# bitfury_h-card-v1_2.net
KiCad netlist of a schematic drawn in EAGLE
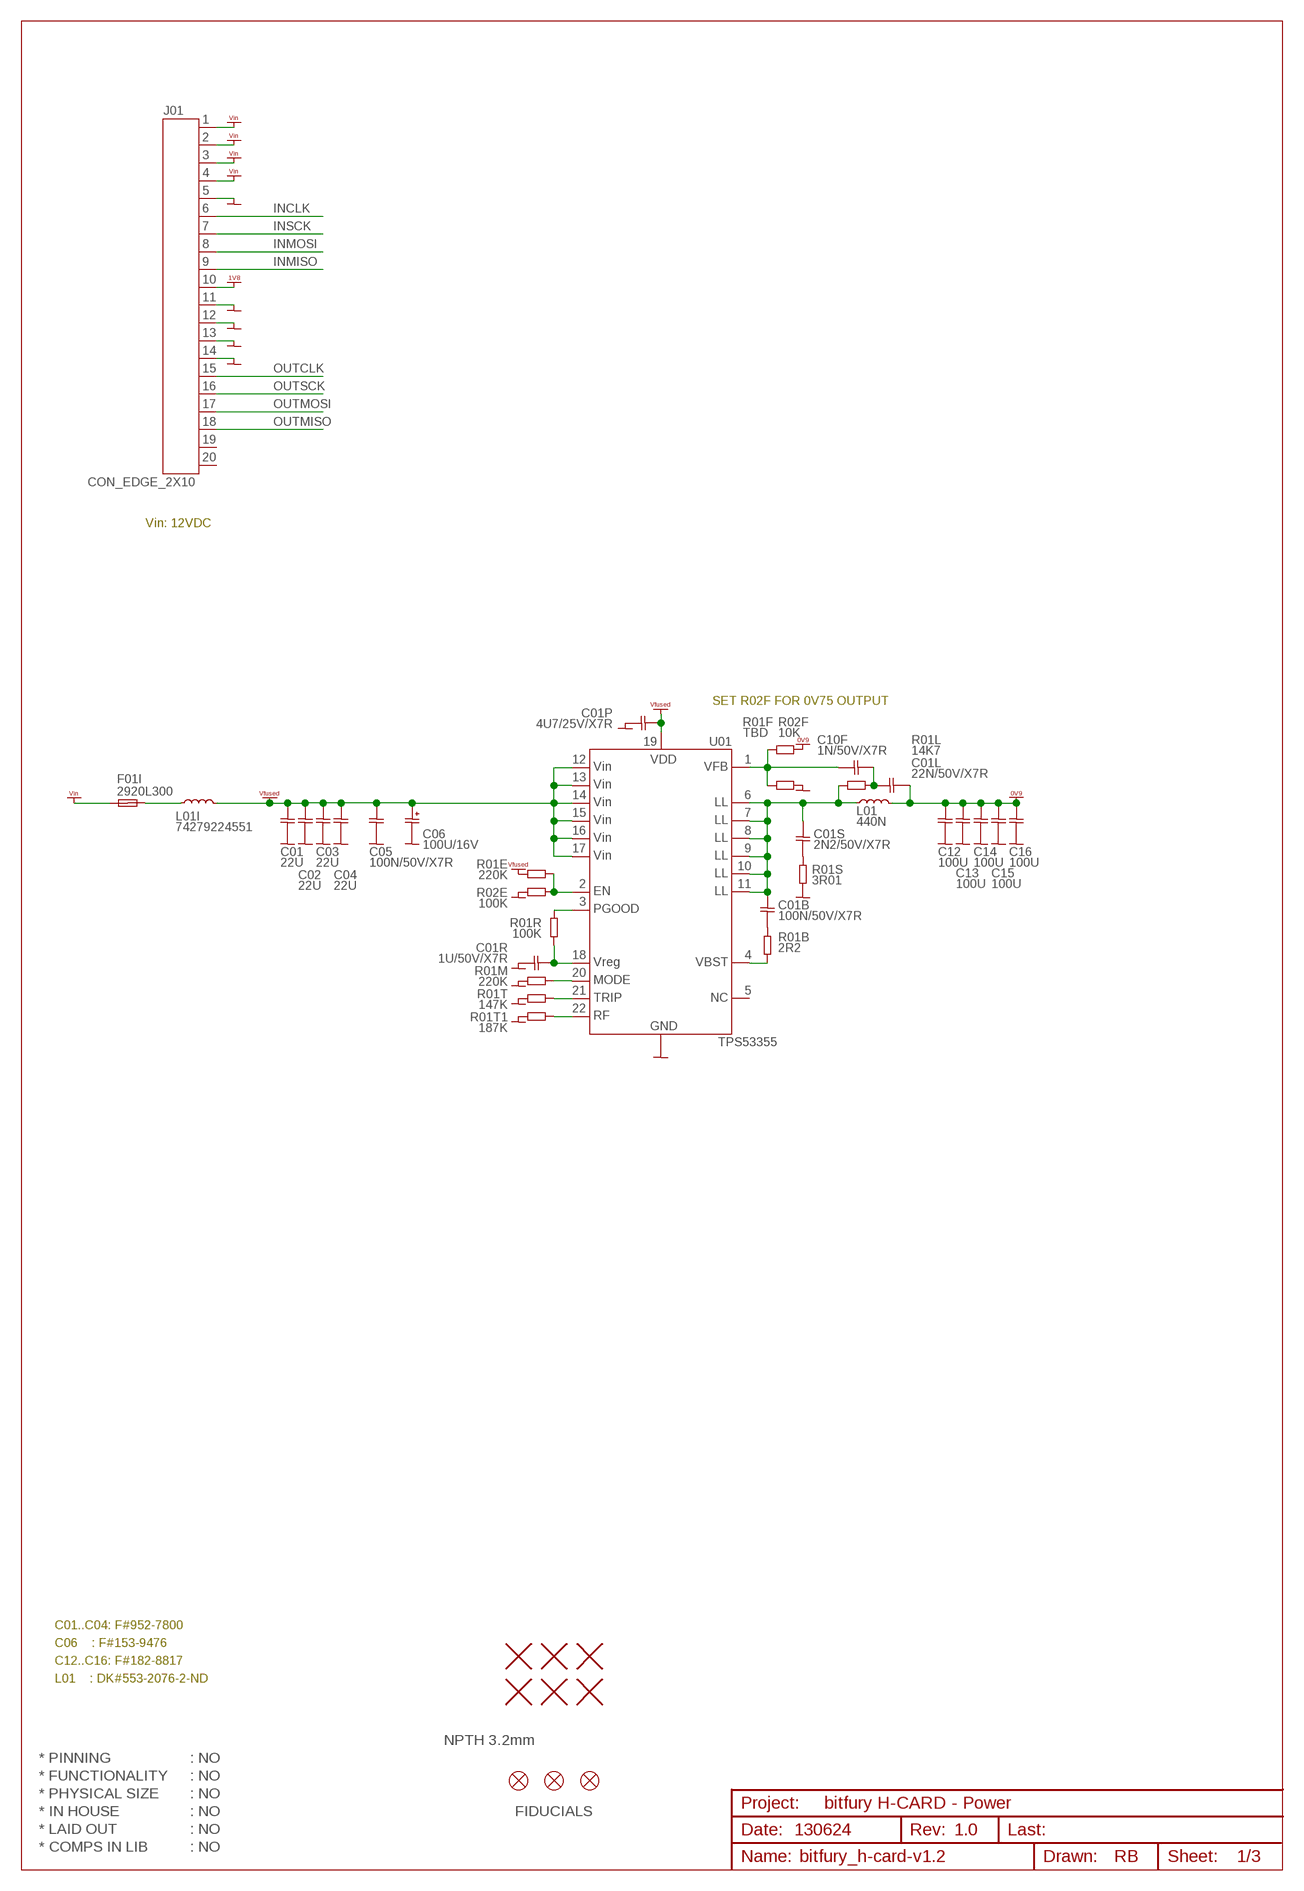
[diagram p0: schematic, sheet 1]
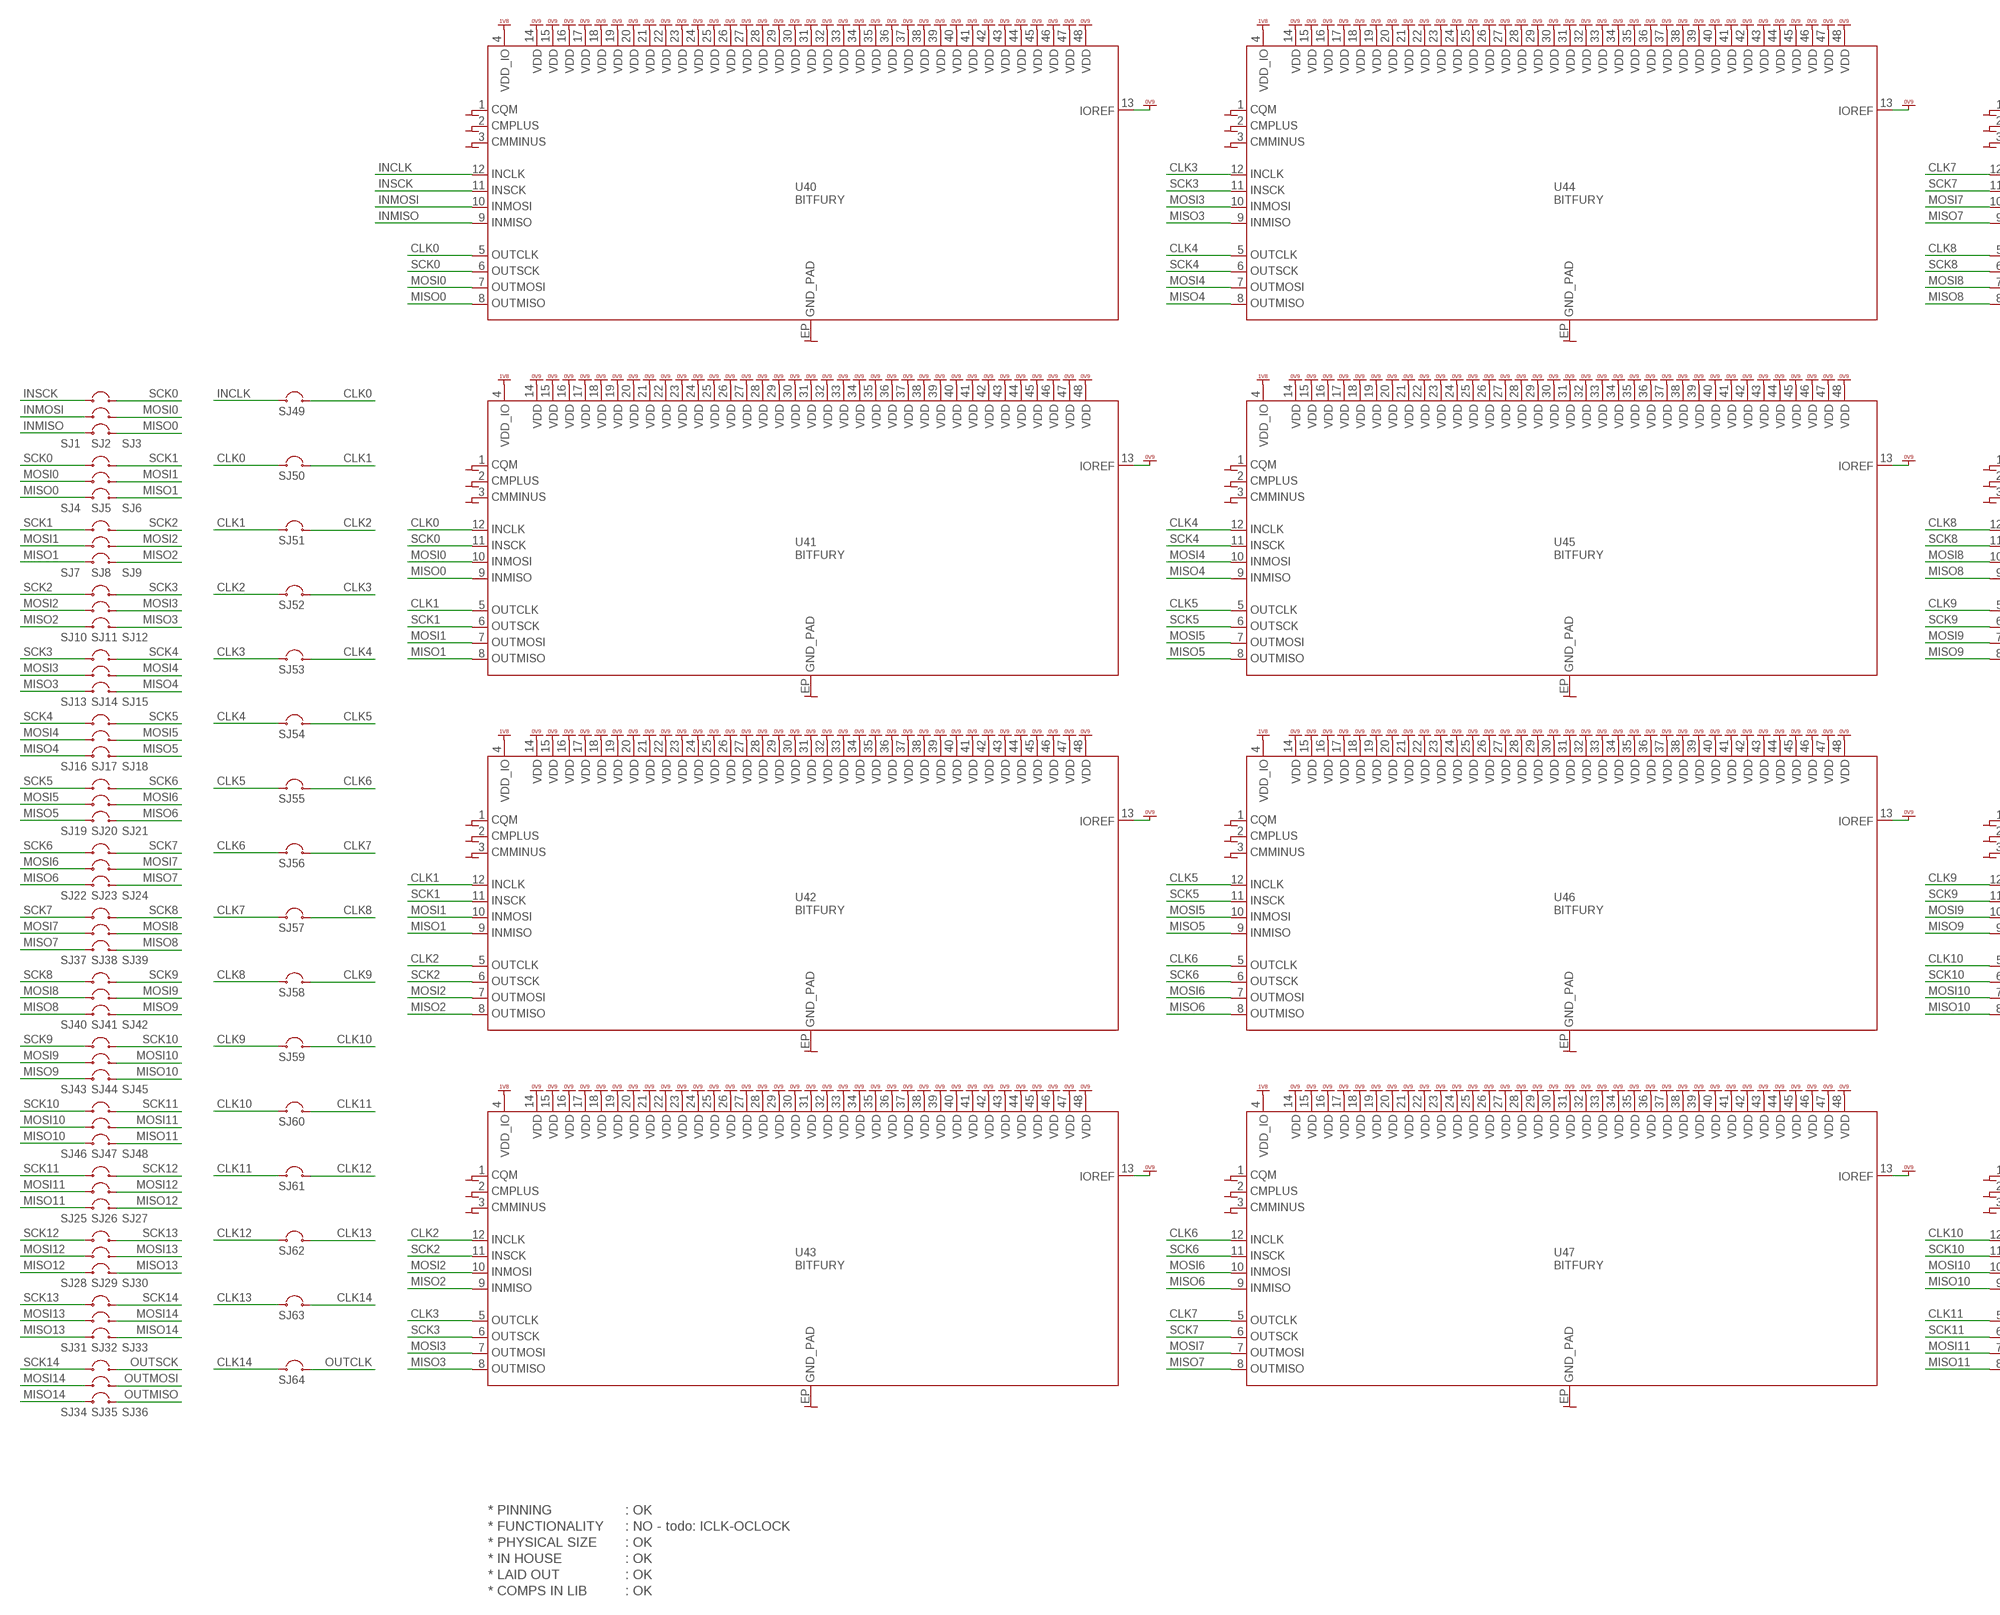
[diagram p1: schematic, sheet 2, part 1 of 2]
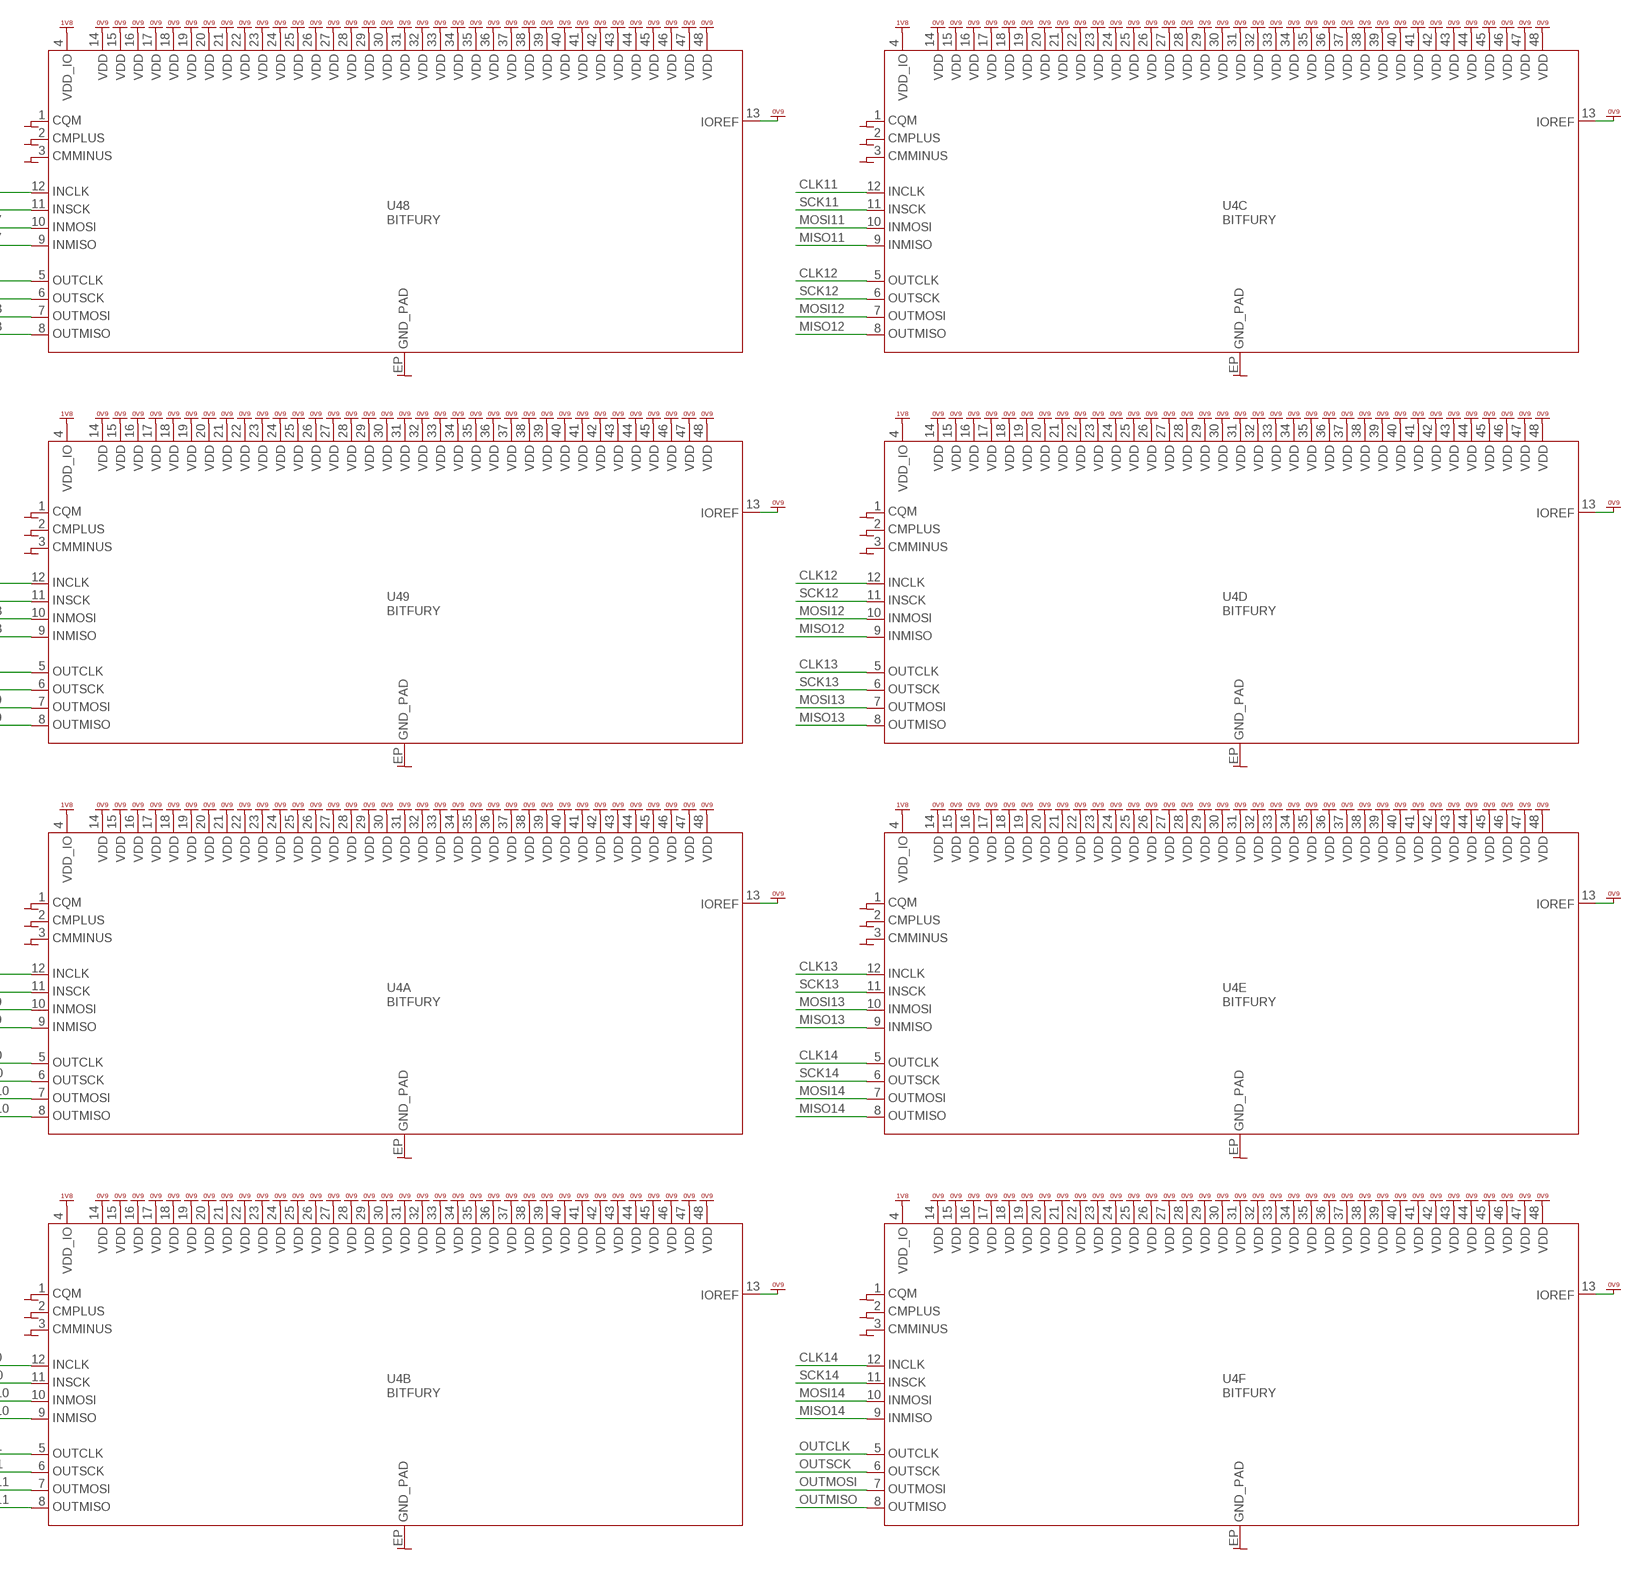
[diagram p2: schematic, sheet 2, part 2 of 2]
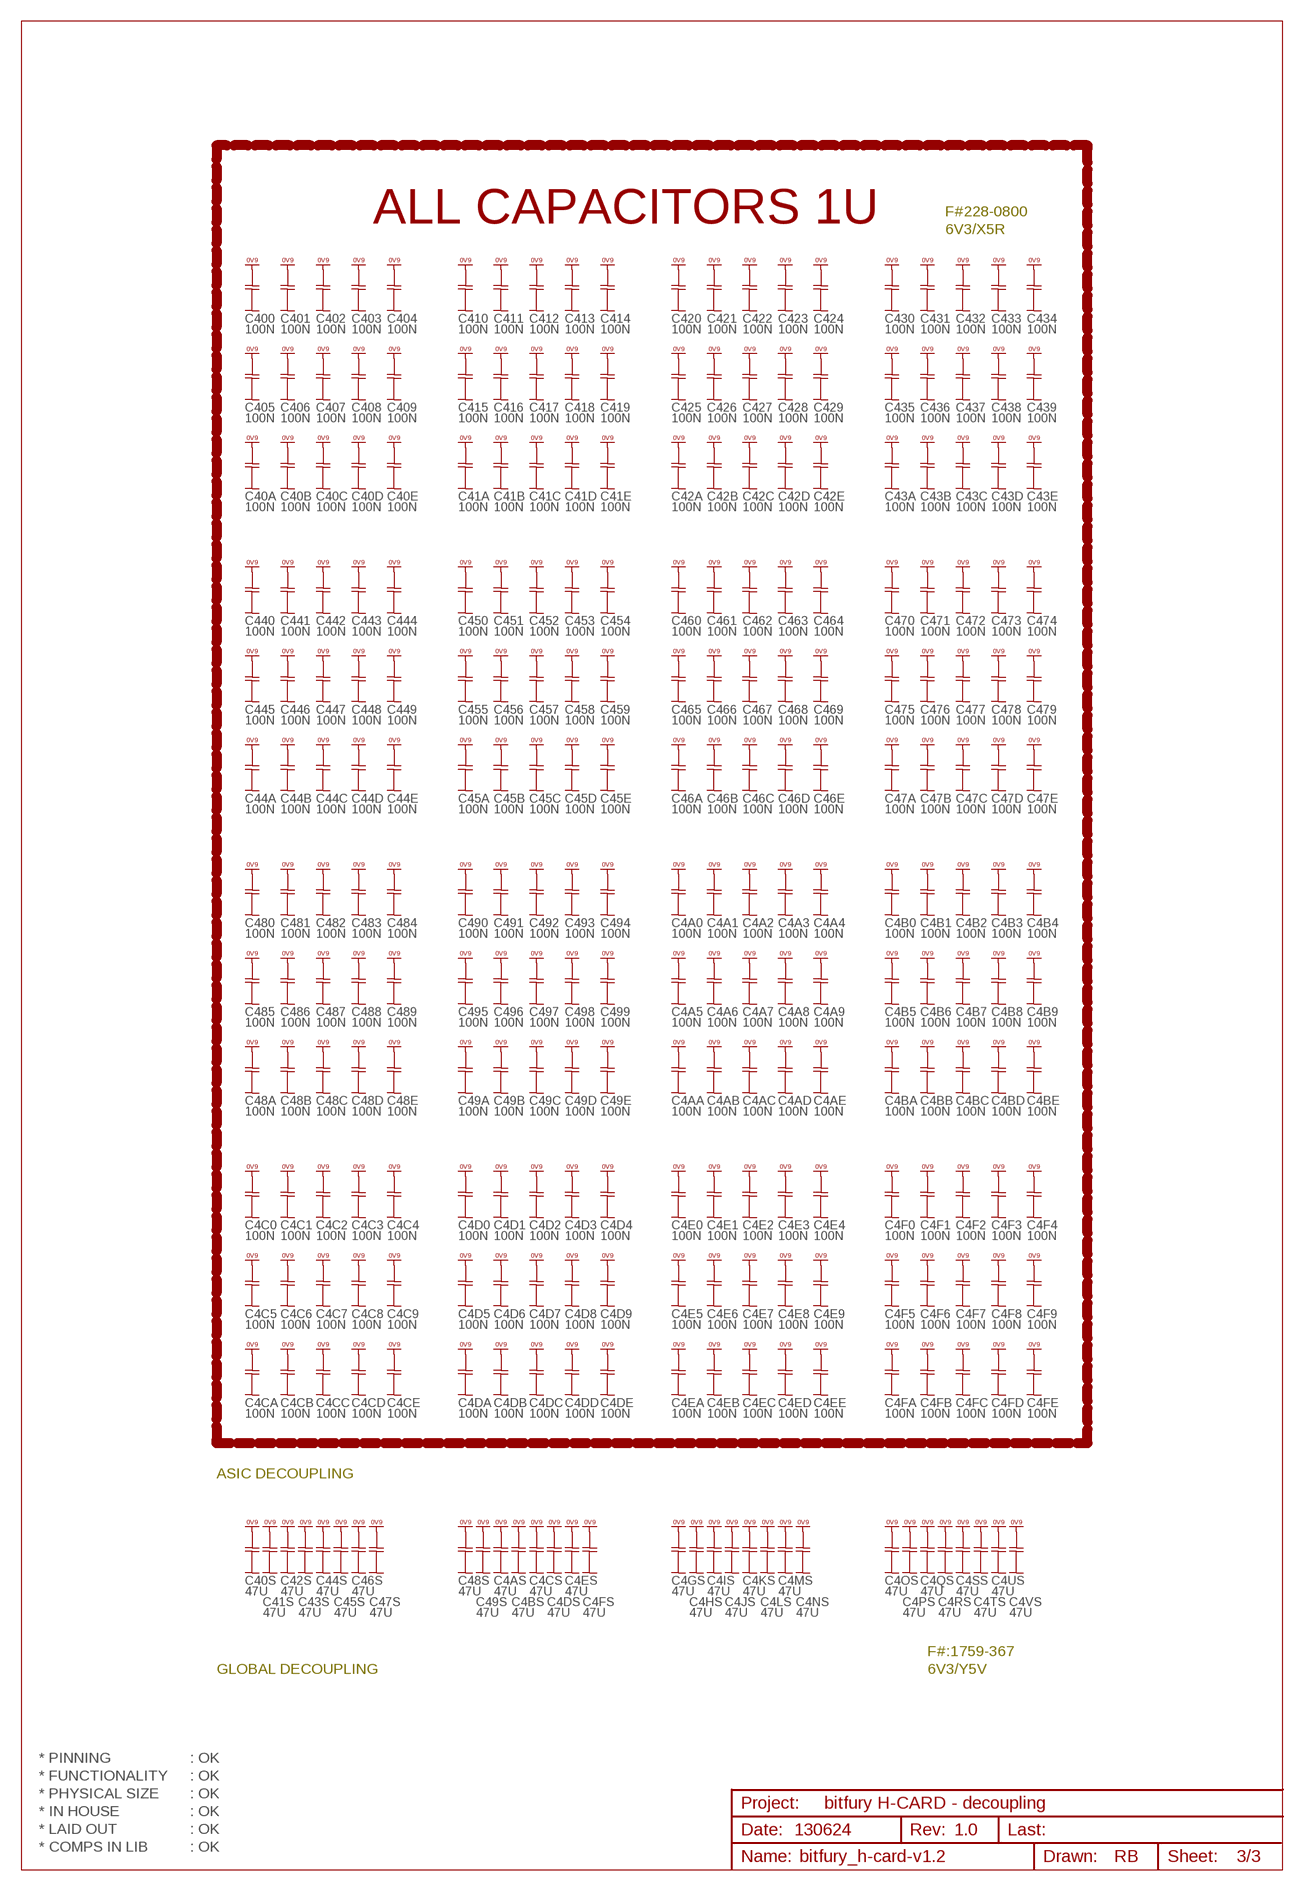
[diagram p3: schematic, sheet 3]

(export (version "E")
  (design (tool "Eeschema 10.0.6"))
  (components
    (comp (ref "C01")
      (value "22U")
      (footprint "eagle-import:CAP1210")
      (libsource (lib "eagle-import") (part "CAP1210"))
    )
    (comp (ref "C01B")
      (value "100N/50V/X7R")
      (footprint "eagle-import:CAP0603")
      (libsource (lib "eagle-import") (part "CAP0603"))
    )
    (comp (ref "C01L")
      (value "22N/50V/X7R")
      (footprint "eagle-import:CAP0603")
      (libsource (lib "eagle-import") (part "CAP0603"))
    )
    (comp (ref "C01P")
      (value "4U7/25V/X7R")
      (footprint "eagle-import:CAP0805")
      (libsource (lib "eagle-import") (part "CAP0805"))
    )
    (comp (ref "C01R")
      (value "1U/50V/X7R")
      (footprint "eagle-import:CAP0603")
      (libsource (lib "eagle-import") (part "CAP0603"))
    )
    (comp (ref "C01S")
      (value "2N2/50V/X7R")
      (footprint "eagle-import:CAP0603")
      (libsource (lib "eagle-import") (part "CAP0603"))
    )
    (comp (ref "C02")
      (value "22U")
      (footprint "eagle-import:CAP1210")
      (libsource (lib "eagle-import") (part "CAP1210"))
    )
    (comp (ref "C03")
      (value "22U")
      (footprint "eagle-import:CAP1210")
      (libsource (lib "eagle-import") (part "CAP1210"))
    )
    (comp (ref "C04")
      (value "22U")
      (footprint "eagle-import:CAP1210")
      (libsource (lib "eagle-import") (part "CAP1210"))
    )
    (comp (ref "C05")
      (value "100N/50V/X7R")
      (footprint "eagle-import:CAP0603")
      (libsource (lib "eagle-import") (part "CAP0603"))
    )
    (comp (ref "C06")
      (value "100U/16V")
      (footprint "eagle-import:ECAP_CASED")
      (libsource (lib "eagle-import") (part "ECAP_CASED"))
    )
    (comp (ref "C10F")
      (value "1N/50V/X7R")
      (footprint "eagle-import:CAP0603")
      (libsource (lib "eagle-import") (part "CAP0603"))
    )
    (comp (ref "C12")
      (value "100U")
      (footprint "eagle-import:CAP1210")
      (libsource (lib "eagle-import") (part "CAP1210"))
    )
    (comp (ref "C13")
      (value "100U")
      (footprint "eagle-import:CAP1210")
      (libsource (lib "eagle-import") (part "CAP1210"))
    )
    (comp (ref "C14")
      (value "100U")
      (footprint "eagle-import:CAP1210")
      (libsource (lib "eagle-import") (part "CAP1210"))
    )
    (comp (ref "C15")
      (value "100U")
      (footprint "eagle-import:CAP1210")
      (libsource (lib "eagle-import") (part "CAP1210"))
    )
    (comp (ref "C16")
      (value "100U")
      (footprint "eagle-import:CAP1210")
      (libsource (lib "eagle-import") (part "CAP1210"))
    )
    (comp (ref "F01I")
      (value "2920L300")
      (footprint "eagle-import:POLYFUSE2920")
      (libsource (lib "eagle-import") (part "POLYFUSE2920"))
    )
    (comp (ref "FI1")
      (value "FIDUCIAL1.5X3")
      (footprint "eagle-import:FIDUCIAL-1.5X3")
      (libsource (lib "eagle-import") (part "FIDUCIAL1.5X3"))
    )
    (comp (ref "FI2")
      (value "FIDUCIAL1.5X3")
      (footprint "eagle-import:FIDUCIAL-1.5X3")
      (libsource (lib "eagle-import") (part "FIDUCIAL1.5X3"))
    )
    (comp (ref "FI3")
      (value "FIDUCIAL1.5X3")
      (footprint "eagle-import:FIDUCIAL-1.5X3")
      (libsource (lib "eagle-import") (part "FIDUCIAL1.5X3"))
    )
    (comp (ref "H1")
      (value "HOLE_NPTH_3.2MM")
      (footprint "eagle-import:HOLE_NPTH_3.2MM")
      (libsource (lib "eagle-import") (part "HOLE_NPTH_3.2MM"))
    )
    (comp (ref "H2")
      (value "HOLE_NPTH_3.2MM")
      (footprint "eagle-import:HOLE_NPTH_3.2MM")
      (libsource (lib "eagle-import") (part "HOLE_NPTH_3.2MM"))
    )
    (comp (ref "H3")
      (value "HOLE_NPTH_3.2MM")
      (footprint "eagle-import:HOLE_NPTH_3.2MM")
      (libsource (lib "eagle-import") (part "HOLE_NPTH_3.2MM"))
    )
    (comp (ref "H4")
      (value "HOLE_NPTH_3.2MM")
      (footprint "eagle-import:HOLE_NPTH_3.2MM")
      (libsource (lib "eagle-import") (part "HOLE_NPTH_3.2MM"))
    )
    (comp (ref "H5")
      (value "HOLE_NPTH_3.2MM")
      (footprint "eagle-import:HOLE_NPTH_3.2MM")
      (libsource (lib "eagle-import") (part "HOLE_NPTH_3.2MM"))
    )
    (comp (ref "H6")
      (value "HOLE_NPTH_3.2MM")
      (footprint "eagle-import:HOLE_NPTH_3.2MM")
      (libsource (lib "eagle-import") (part "HOLE_NPTH_3.2MM"))
    )
    (comp (ref "J01")
      (value "CON_EDGE_2X10")
      (footprint "eagle-import:CON_EDGE_2X10")
      (libsource (lib "eagle-import") (part "CON_EDGE_2X10"))
    )
    (comp (ref "L01")
      (value "440N")
      (footprint "eagle-import:PA0513.441NLT")
      (libsource (lib "eagle-import") (part "PA0513.441NLT"))
    )
    (comp (ref "L01I")
      (value "74279224551")
      (footprint "eagle-import:L2220")
      (libsource (lib "eagle-import") (part "L2220"))
    )
    (comp (ref "R01B")
      (value "2R2")
      (footprint "eagle-import:RES0603")
      (libsource (lib "eagle-import") (part "RES0603"))
    )
    (comp (ref "R01E")
      (value "220K")
      (footprint "eagle-import:RES0603")
      (libsource (lib "eagle-import") (part "RES0603"))
    )
    (comp (ref "R01F")
      (value "TBD")
      (footprint "eagle-import:RES0603")
      (libsource (lib "eagle-import") (part "RES0603"))
    )
    (comp (ref "R01L")
      (value "14K7")
      (footprint "eagle-import:RES0603")
      (libsource (lib "eagle-import") (part "RES0603"))
    )
    (comp (ref "R01M")
      (value "220K")
      (footprint "eagle-import:RES0603")
      (libsource (lib "eagle-import") (part "RES0603"))
    )
    (comp (ref "R01R")
      (value "100K")
      (footprint "eagle-import:RES0603")
      (libsource (lib "eagle-import") (part "RES0603"))
    )
    (comp (ref "R01S")
      (value "3R01")
      (footprint "eagle-import:RES0805")
      (libsource (lib "eagle-import") (part "RES0805"))
    )
    (comp (ref "R01T")
      (value "147K")
      (footprint "eagle-import:RES0603")
      (libsource (lib "eagle-import") (part "RES0603"))
    )
    (comp (ref "R01T1")
      (value "187K")
      (footprint "eagle-import:RES0603")
      (libsource (lib "eagle-import") (part "RES0603"))
    )
    (comp (ref "R02E")
      (value "100K")
      (footprint "eagle-import:RES0603")
      (libsource (lib "eagle-import") (part "RES0603"))
    )
    (comp (ref "R02F")
      (value "10K")
      (footprint "eagle-import:RES0603")
      (libsource (lib "eagle-import") (part "RES0603"))
    )
    (comp (ref "U01")
      (value "TPS53355")
      (footprint "eagle-import:DQP22")
      (libsource (lib "eagle-import") (part "TPS53355"))
    )
    (comp (ref "C4A0")
      (value "100N")
      (footprint "eagle-import:CAP0402")
      (libsource (lib "eagle-import") (part "CAP0402"))
    )
    (comp (ref "C4A1")
      (value "100N")
      (footprint "eagle-import:CAP0402")
      (libsource (lib "eagle-import") (part "CAP0402"))
    )
    (comp (ref "C4A2")
      (value "100N")
      (footprint "eagle-import:CAP0402")
      (libsource (lib "eagle-import") (part "CAP0402"))
    )
    (comp (ref "C4A3")
      (value "100N")
      (footprint "eagle-import:CAP0402")
      (libsource (lib "eagle-import") (part "CAP0402"))
    )
    (comp (ref "C4A4")
      (value "100N")
      (footprint "eagle-import:CAP0402")
      (libsource (lib "eagle-import") (part "CAP0402"))
    )
    (comp (ref "C4A5")
      (value "100N")
      (footprint "eagle-import:CAP0402")
      (libsource (lib "eagle-import") (part "CAP0402"))
    )
    (comp (ref "C4A6")
      (value "100N")
      (footprint "eagle-import:CAP0402")
      (libsource (lib "eagle-import") (part "CAP0402"))
    )
    (comp (ref "C4A7")
      (value "100N")
      (footprint "eagle-import:CAP0402")
      (libsource (lib "eagle-import") (part "CAP0402"))
    )
    (comp (ref "C4A8")
      (value "100N")
      (footprint "eagle-import:CAP0402")
      (libsource (lib "eagle-import") (part "CAP0402"))
    )
    (comp (ref "C4A9")
      (value "100N")
      (footprint "eagle-import:CAP0402")
      (libsource (lib "eagle-import") (part "CAP0402"))
    )
    (comp (ref "C4AA")
      (value "100N")
      (footprint "eagle-import:CAP0402")
      (libsource (lib "eagle-import") (part "CAP0402"))
    )
    (comp (ref "C4AB")
      (value "100N")
      (footprint "eagle-import:CAP0402")
      (libsource (lib "eagle-import") (part "CAP0402"))
    )
    (comp (ref "C4AC")
      (value "100N")
      (footprint "eagle-import:CAP0402")
      (libsource (lib "eagle-import") (part "CAP0402"))
    )
    (comp (ref "C4AD")
      (value "100N")
      (footprint "eagle-import:CAP0402")
      (libsource (lib "eagle-import") (part "CAP0402"))
    )
    (comp (ref "C4AE")
      (value "100N")
      (footprint "eagle-import:CAP0402")
      (libsource (lib "eagle-import") (part "CAP0402"))
    )
    (comp (ref "C4AS")
      (value "47U")
      (footprint "eagle-import:CAP1210")
      (libsource (lib "eagle-import") (part "CAP1210"))
    )
    (comp (ref "C4B0")
      (value "100N")
      (footprint "eagle-import:CAP0402")
      (libsource (lib "eagle-import") (part "CAP0402"))
    )
    (comp (ref "C4B1")
      (value "100N")
      (footprint "eagle-import:CAP0402")
      (libsource (lib "eagle-import") (part "CAP0402"))
    )
    (comp (ref "C4B2")
      (value "100N")
      (footprint "eagle-import:CAP0402")
      (libsource (lib "eagle-import") (part "CAP0402"))
    )
    (comp (ref "C4B3")
      (value "100N")
      (footprint "eagle-import:CAP0402")
      (libsource (lib "eagle-import") (part "CAP0402"))
    )
    (comp (ref "C4B4")
      (value "100N")
      (footprint "eagle-import:CAP0402")
      (libsource (lib "eagle-import") (part "CAP0402"))
    )
    (comp (ref "C4B5")
      (value "100N")
      (footprint "eagle-import:CAP0402")
      (libsource (lib "eagle-import") (part "CAP0402"))
    )
    (comp (ref "C4B6")
      (value "100N")
      (footprint "eagle-import:CAP0402")
      (libsource (lib "eagle-import") (part "CAP0402"))
    )
    (comp (ref "C4B7")
      (value "100N")
      (footprint "eagle-import:CAP0402")
      (libsource (lib "eagle-import") (part "CAP0402"))
    )
    (comp (ref "C4B8")
      (value "100N")
      (footprint "eagle-import:CAP0402")
      (libsource (lib "eagle-import") (part "CAP0402"))
    )
    (comp (ref "C4B9")
      (value "100N")
      (footprint "eagle-import:CAP0402")
      (libsource (lib "eagle-import") (part "CAP0402"))
    )
    (comp (ref "C4BA")
      (value "100N")
      (footprint "eagle-import:CAP0402")
      (libsource (lib "eagle-import") (part "CAP0402"))
    )
    (comp (ref "C4BB")
      (value "100N")
      (footprint "eagle-import:CAP0402")
      (libsource (lib "eagle-import") (part "CAP0402"))
    )
    (comp (ref "C4BC")
      (value "100N")
      (footprint "eagle-import:CAP0402")
      (libsource (lib "eagle-import") (part "CAP0402"))
    )
    (comp (ref "C4BD")
      (value "100N")
      (footprint "eagle-import:CAP0402")
      (libsource (lib "eagle-import") (part "CAP0402"))
    )
    (comp (ref "C4BE")
      (value "100N")
      (footprint "eagle-import:CAP0402")
      (libsource (lib "eagle-import") (part "CAP0402"))
    )
    (comp (ref "C4BS")
      (value "47U")
      (footprint "eagle-import:CAP1210")
      (libsource (lib "eagle-import") (part "CAP1210"))
    )
    (comp (ref "C4C0")
      (value "100N")
      (footprint "eagle-import:CAP0402")
      (libsource (lib "eagle-import") (part "CAP0402"))
    )
    (comp (ref "C4C1")
      (value "100N")
      (footprint "eagle-import:CAP0402")
      (libsource (lib "eagle-import") (part "CAP0402"))
    )
    (comp (ref "C4C2")
      (value "100N")
      (footprint "eagle-import:CAP0402")
      (libsource (lib "eagle-import") (part "CAP0402"))
    )
    (comp (ref "C4C3")
      (value "100N")
      (footprint "eagle-import:CAP0402")
      (libsource (lib "eagle-import") (part "CAP0402"))
    )
    (comp (ref "C4C4")
      (value "100N")
      (footprint "eagle-import:CAP0402")
      (libsource (lib "eagle-import") (part "CAP0402"))
    )
    (comp (ref "C4C5")
      (value "100N")
      (footprint "eagle-import:CAP0402")
      (libsource (lib "eagle-import") (part "CAP0402"))
    )
    (comp (ref "C4C6")
      (value "100N")
      (footprint "eagle-import:CAP0402")
      (libsource (lib "eagle-import") (part "CAP0402"))
    )
    (comp (ref "C4C7")
      (value "100N")
      (footprint "eagle-import:CAP0402")
      (libsource (lib "eagle-import") (part "CAP0402"))
    )
    (comp (ref "C4C8")
      (value "100N")
      (footprint "eagle-import:CAP0402")
      (libsource (lib "eagle-import") (part "CAP0402"))
    )
    (comp (ref "C4C9")
      (value "100N")
      (footprint "eagle-import:CAP0402")
      (libsource (lib "eagle-import") (part "CAP0402"))
    )
    (comp (ref "C4CA")
      (value "100N")
      (footprint "eagle-import:CAP0402")
      (libsource (lib "eagle-import") (part "CAP0402"))
    )
    (comp (ref "C4CB")
      (value "100N")
      (footprint "eagle-import:CAP0402")
      (libsource (lib "eagle-import") (part "CAP0402"))
    )
    (comp (ref "C4CC")
      (value "100N")
      (footprint "eagle-import:CAP0402")
      (libsource (lib "eagle-import") (part "CAP0402"))
    )
    (comp (ref "C4CD")
      (value "100N")
      (footprint "eagle-import:CAP0402")
      (libsource (lib "eagle-import") (part "CAP0402"))
    )
    (comp (ref "C4CE")
      (value "100N")
      (footprint "eagle-import:CAP0402")
      (libsource (lib "eagle-import") (part "CAP0402"))
    )
    (comp (ref "C4CS")
      (value "47U")
      (footprint "eagle-import:CAP1210")
      (libsource (lib "eagle-import") (part "CAP1210"))
    )
    (comp (ref "C4D0")
      (value "100N")
      (footprint "eagle-import:CAP0402")
      (libsource (lib "eagle-import") (part "CAP0402"))
    )
    (comp (ref "C4D1")
      (value "100N")
      (footprint "eagle-import:CAP0402")
      (libsource (lib "eagle-import") (part "CAP0402"))
    )
    (comp (ref "C4D2")
      (value "100N")
      (footprint "eagle-import:CAP0402")
      (libsource (lib "eagle-import") (part "CAP0402"))
    )
    (comp (ref "C4D3")
      (value "100N")
      (footprint "eagle-import:CAP0402")
      (libsource (lib "eagle-import") (part "CAP0402"))
    )
    (comp (ref "C4D4")
      (value "100N")
      (footprint "eagle-import:CAP0402")
      (libsource (lib "eagle-import") (part "CAP0402"))
    )
    (comp (ref "C4D5")
      (value "100N")
      (footprint "eagle-import:CAP0402")
      (libsource (lib "eagle-import") (part "CAP0402"))
    )
    (comp (ref "C4D6")
      (value "100N")
      (footprint "eagle-import:CAP0402")
      (libsource (lib "eagle-import") (part "CAP0402"))
    )
    (comp (ref "C4D7")
      (value "100N")
      (footprint "eagle-import:CAP0402")
      (libsource (lib "eagle-import") (part "CAP0402"))
    )
    (comp (ref "C4D8")
      (value "100N")
      (footprint "eagle-import:CAP0402")
      (libsource (lib "eagle-import") (part "CAP0402"))
    )
    (comp (ref "C4D9")
      (value "100N")
      (footprint "eagle-import:CAP0402")
      (libsource (lib "eagle-import") (part "CAP0402"))
    )
    (comp (ref "C4DA")
      (value "100N")
      (footprint "eagle-import:CAP0402")
      (libsource (lib "eagle-import") (part "CAP0402"))
    )
    (comp (ref "C4DB")
      (value "100N")
      (footprint "eagle-import:CAP0402")
      (libsource (lib "eagle-import") (part "CAP0402"))
    )
    (comp (ref "C4DC")
      (value "100N")
      (footprint "eagle-import:CAP0402")
      (libsource (lib "eagle-import") (part "CAP0402"))
    )
    (comp (ref "C4DD")
      (value "100N")
      (footprint "eagle-import:CAP0402")
      (libsource (lib "eagle-import") (part "CAP0402"))
    )
    (comp (ref "C4DE")
      (value "100N")
      (footprint "eagle-import:CAP0402")
      (libsource (lib "eagle-import") (part "CAP0402"))
    )
    (comp (ref "C4DS")
      (value "47U")
      (footprint "eagle-import:CAP1210")
      (libsource (lib "eagle-import") (part "CAP1210"))
    )
    (comp (ref "C4E0")
      (value "100N")
      (footprint "eagle-import:CAP0402")
      (libsource (lib "eagle-import") (part "CAP0402"))
    )
    (comp (ref "C4E1")
      (value "100N")
      (footprint "eagle-import:CAP0402")
      (libsource (lib "eagle-import") (part "CAP0402"))
    )
    (comp (ref "C4E2")
      (value "100N")
      (footprint "eagle-import:CAP0402")
      (libsource (lib "eagle-import") (part "CAP0402"))
    )
    (comp (ref "C4E3")
      (value "100N")
      (footprint "eagle-import:CAP0402")
      (libsource (lib "eagle-import") (part "CAP0402"))
    )
    (comp (ref "C4E4")
      (value "100N")
      (footprint "eagle-import:CAP0402")
      (libsource (lib "eagle-import") (part "CAP0402"))
    )
    (comp (ref "C4E5")
      (value "100N")
      (footprint "eagle-import:CAP0402")
      (libsource (lib "eagle-import") (part "CAP0402"))
    )
    (comp (ref "C4E6")
      (value "100N")
      (footprint "eagle-import:CAP0402")
      (libsource (lib "eagle-import") (part "CAP0402"))
    )
    (comp (ref "C4E7")
      (value "100N")
      (footprint "eagle-import:CAP0402")
      (libsource (lib "eagle-import") (part "CAP0402"))
    )
    (comp (ref "C4E8")
      (value "100N")
      (footprint "eagle-import:CAP0402")
      (libsource (lib "eagle-import") (part "CAP0402"))
    )
    (comp (ref "C4E9")
      (value "100N")
      (footprint "eagle-import:CAP0402")
      (libsource (lib "eagle-import") (part "CAP0402"))
    )
    (comp (ref "C4EA")
      (value "100N")
      (footprint "eagle-import:CAP0402")
      (libsource (lib "eagle-import") (part "CAP0402"))
    )
    (comp (ref "C4EB")
      (value "100N")
      (footprint "eagle-import:CAP0402")
      (libsource (lib "eagle-import") (part "CAP0402"))
    )
    (comp (ref "C4EC")
      (value "100N")
      (footprint "eagle-import:CAP0402")
      (libsource (lib "eagle-import") (part "CAP0402"))
    )
    (comp (ref "C4ED")
      (value "100N")
      (footprint "eagle-import:CAP0402")
      (libsource (lib "eagle-import") (part "CAP0402"))
    )
    (comp (ref "C4EE")
      (value "100N")
      (footprint "eagle-import:CAP0402")
      (libsource (lib "eagle-import") (part "CAP0402"))
    )
    (comp (ref "C4ES")
      (value "47U")
      (footprint "eagle-import:CAP1210")
      (libsource (lib "eagle-import") (part "CAP1210"))
    )
    (comp (ref "C4F0")
      (value "100N")
      (footprint "eagle-import:CAP0402")
      (libsource (lib "eagle-import") (part "CAP0402"))
    )
    (comp (ref "C4F1")
      (value "100N")
      (footprint "eagle-import:CAP0402")
      (libsource (lib "eagle-import") (part "CAP0402"))
    )
    (comp (ref "C4F2")
      (value "100N")
      (footprint "eagle-import:CAP0402")
      (libsource (lib "eagle-import") (part "CAP0402"))
    )
    (comp (ref "C4F3")
      (value "100N")
      (footprint "eagle-import:CAP0402")
      (libsource (lib "eagle-import") (part "CAP0402"))
    )
    (comp (ref "C4F4")
      (value "100N")
      (footprint "eagle-import:CAP0402")
      (libsource (lib "eagle-import") (part "CAP0402"))
    )
    (comp (ref "C4F5")
      (value "100N")
      (footprint "eagle-import:CAP0402")
      (libsource (lib "eagle-import") (part "CAP0402"))
    )
    (comp (ref "C4F6")
      (value "100N")
      (footprint "eagle-import:CAP0402")
      (libsource (lib "eagle-import") (part "CAP0402"))
    )
    (comp (ref "C4F7")
      (value "100N")
      (footprint "eagle-import:CAP0402")
      (libsource (lib "eagle-import") (part "CAP0402"))
    )
    (comp (ref "C4F8")
      (value "100N")
      (footprint "eagle-import:CAP0402")
      (libsource (lib "eagle-import") (part "CAP0402"))
    )
    (comp (ref "C4F9")
      (value "100N")
      (footprint "eagle-import:CAP0402")
      (libsource (lib "eagle-import") (part "CAP0402"))
    )
    (comp (ref "C4FA")
      (value "100N")
      (footprint "eagle-import:CAP0402")
      (libsource (lib "eagle-import") (part "CAP0402"))
    )
    (comp (ref "C4FB")
      (value "100N")
      (footprint "eagle-import:CAP0402")
      (libsource (lib "eagle-import") (part "CAP0402"))
    )
    (comp (ref "C4FC")
      (value "100N")
      (footprint "eagle-import:CAP0402")
      (libsource (lib "eagle-import") (part "CAP0402"))
    )
    (comp (ref "C4FD")
      (value "100N")
      (footprint "eagle-import:CAP0402")
      (libsource (lib "eagle-import") (part "CAP0402"))
    )
    (comp (ref "C4FE")
      (value "100N")
      (footprint "eagle-import:CAP0402")
      (libsource (lib "eagle-import") (part "CAP0402"))
    )
    (comp (ref "C4FS")
      (value "47U")
      (footprint "eagle-import:CAP1210")
      (libsource (lib "eagle-import") (part "CAP1210"))
    )
    (comp (ref "C4GS")
      (value "47U")
      (footprint "eagle-import:CAP1210")
      (libsource (lib "eagle-import") (part "CAP1210"))
    )
    (comp (ref "C4HS")
      (value "47U")
      (footprint "eagle-import:CAP1210")
      (libsource (lib "eagle-import") (part "CAP1210"))
    )
    (comp (ref "C4IS")
      (value "47U")
      (footprint "eagle-import:CAP1210")
      (libsource (lib "eagle-import") (part "CAP1210"))
    )
    (comp (ref "C4JS")
      (value "47U")
      (footprint "eagle-import:CAP1210")
      (libsource (lib "eagle-import") (part "CAP1210"))
    )
    (comp (ref "C4KS")
      (value "47U")
      (footprint "eagle-import:CAP1210")
      (libsource (lib "eagle-import") (part "CAP1210"))
    )
    (comp (ref "C4LS")
      (value "47U")
      (footprint "eagle-import:CAP1210")
      (libsource (lib "eagle-import") (part "CAP1210"))
    )
    (comp (ref "C4MS")
      (value "47U")
      (footprint "eagle-import:CAP1210")
      (libsource (lib "eagle-import") (part "CAP1210"))
    )
    (comp (ref "C4NS")
      (value "47U")
      (footprint "eagle-import:CAP1210")
      (libsource (lib "eagle-import") (part "CAP1210"))
    )
    (comp (ref "C4OS")
      (value "47U")
      (footprint "eagle-import:CAP1210")
      (libsource (lib "eagle-import") (part "CAP1210"))
    )
    (comp (ref "C4PS")
      (value "47U")
      (footprint "eagle-import:CAP1210")
      (libsource (lib "eagle-import") (part "CAP1210"))
    )
    (comp (ref "C4QS")
      (value "47U")
      (footprint "eagle-import:CAP1210")
      (libsource (lib "eagle-import") (part "CAP1210"))
    )
    (comp (ref "C4RS")
      (value "47U")
      (footprint "eagle-import:CAP1210")
      (libsource (lib "eagle-import") (part "CAP1210"))
    )
    (comp (ref "C4SS")
      (value "47U")
      (footprint "eagle-import:CAP1210")
      (libsource (lib "eagle-import") (part "CAP1210"))
    )
    (comp (ref "C4TS")
      (value "47U")
      (footprint "eagle-import:CAP1210")
      (libsource (lib "eagle-import") (part "CAP1210"))
    )
    (comp (ref "C4US")
      (value "47U")
      (footprint "eagle-import:CAP1210")
      (libsource (lib "eagle-import") (part "CAP1210"))
    )
    (comp (ref "C4VS")
      (value "47U")
      (footprint "eagle-import:CAP1210")
      (libsource (lib "eagle-import") (part "CAP1210"))
    )
    (comp (ref "C40A")
      (value "100N")
      (footprint "eagle-import:CAP0402")
      (libsource (lib "eagle-import") (part "CAP0402"))
    )
    (comp (ref "C40B")
      (value "100N")
      (footprint "eagle-import:CAP0402")
      (libsource (lib "eagle-import") (part "CAP0402"))
    )
    (comp (ref "C40C")
      (value "100N")
      (footprint "eagle-import:CAP0402")
      (libsource (lib "eagle-import") (part "CAP0402"))
    )
    (comp (ref "C40D")
      (value "100N")
      (footprint "eagle-import:CAP0402")
      (libsource (lib "eagle-import") (part "CAP0402"))
    )
    (comp (ref "C40E")
      (value "100N")
      (footprint "eagle-import:CAP0402")
      (libsource (lib "eagle-import") (part "CAP0402"))
    )
    (comp (ref "C40S")
      (value "47U")
      (footprint "eagle-import:CAP1210")
      (libsource (lib "eagle-import") (part "CAP1210"))
    )
    (comp (ref "C41A")
      (value "100N")
      (footprint "eagle-import:CAP0402")
      (libsource (lib "eagle-import") (part "CAP0402"))
    )
    (comp (ref "C41B")
      (value "100N")
      (footprint "eagle-import:CAP0402")
      (libsource (lib "eagle-import") (part "CAP0402"))
    )
    (comp (ref "C41C")
      (value "100N")
      (footprint "eagle-import:CAP0402")
      (libsource (lib "eagle-import") (part "CAP0402"))
    )
    (comp (ref "C41D")
      (value "100N")
      (footprint "eagle-import:CAP0402")
      (libsource (lib "eagle-import") (part "CAP0402"))
    )
    (comp (ref "C41E")
      (value "100N")
      (footprint "eagle-import:CAP0402")
      (libsource (lib "eagle-import") (part "CAP0402"))
    )
    (comp (ref "C41S")
      (value "47U")
      (footprint "eagle-import:CAP1210")
      (libsource (lib "eagle-import") (part "CAP1210"))
    )
    (comp (ref "C42A")
      (value "100N")
      (footprint "eagle-import:CAP0402")
      (libsource (lib "eagle-import") (part "CAP0402"))
    )
    (comp (ref "C42B")
      (value "100N")
      (footprint "eagle-import:CAP0402")
      (libsource (lib "eagle-import") (part "CAP0402"))
    )
    (comp (ref "C42C")
      (value "100N")
      (footprint "eagle-import:CAP0402")
      (libsource (lib "eagle-import") (part "CAP0402"))
    )
    (comp (ref "C42D")
      (value "100N")
      (footprint "eagle-import:CAP0402")
      (libsource (lib "eagle-import") (part "CAP0402"))
    )
    (comp (ref "C42E")
      (value "100N")
      (footprint "eagle-import:CAP0402")
      (libsource (lib "eagle-import") (part "CAP0402"))
    )
    (comp (ref "C42S")
      (value "47U")
      (footprint "eagle-import:CAP1210")
      (libsource (lib "eagle-import") (part "CAP1210"))
    )
    (comp (ref "C43A")
      (value "100N")
      (footprint "eagle-import:CAP0402")
      (libsource (lib "eagle-import") (part "CAP0402"))
    )
    (comp (ref "C43B")
      (value "100N")
      (footprint "eagle-import:CAP0402")
      (libsource (lib "eagle-import") (part "CAP0402"))
    )
    (comp (ref "C43C")
      (value "100N")
      (footprint "eagle-import:CAP0402")
      (libsource (lib "eagle-import") (part "CAP0402"))
    )
    (comp (ref "C43D")
      (value "100N")
      (footprint "eagle-import:CAP0402")
      (libsource (lib "eagle-import") (part "CAP0402"))
    )
    (comp (ref "C43E")
      (value "100N")
      (footprint "eagle-import:CAP0402")
      (libsource (lib "eagle-import") (part "CAP0402"))
    )
    (comp (ref "C43S")
      (value "47U")
      (footprint "eagle-import:CAP1210")
      (libsource (lib "eagle-import") (part "CAP1210"))
    )
    (comp (ref "C44A")
      (value "100N")
      (footprint "eagle-import:CAP0402")
      (libsource (lib "eagle-import") (part "CAP0402"))
    )
    (comp (ref "C44B")
      (value "100N")
      (footprint "eagle-import:CAP0402")
      (libsource (lib "eagle-import") (part "CAP0402"))
    )
    (comp (ref "C44C")
      (value "100N")
      (footprint "eagle-import:CAP0402")
      (libsource (lib "eagle-import") (part "CAP0402"))
    )
    (comp (ref "C44D")
      (value "100N")
      (footprint "eagle-import:CAP0402")
      (libsource (lib "eagle-import") (part "CAP0402"))
    )
    (comp (ref "C44E")
      (value "100N")
      (footprint "eagle-import:CAP0402")
      (libsource (lib "eagle-import") (part "CAP0402"))
    )
    (comp (ref "C44S")
      (value "47U")
      (footprint "eagle-import:CAP1210")
      (libsource (lib "eagle-import") (part "CAP1210"))
    )
    (comp (ref "C45A")
      (value "100N")
      (footprint "eagle-import:CAP0402")
      (libsource (lib "eagle-import") (part "CAP0402"))
    )
    (comp (ref "C45B")
      (value "100N")
      (footprint "eagle-import:CAP0402")
      (libsource (lib "eagle-import") (part "CAP0402"))
    )
    (comp (ref "C45C")
      (value "100N")
      (footprint "eagle-import:CAP0402")
      (libsource (lib "eagle-import") (part "CAP0402"))
    )
    (comp (ref "C45D")
      (value "100N")
      (footprint "eagle-import:CAP0402")
      (libsource (lib "eagle-import") (part "CAP0402"))
    )
    (comp (ref "C45E")
      (value "100N")
      (footprint "eagle-import:CAP0402")
      (libsource (lib "eagle-import") (part "CAP0402"))
    )
    (comp (ref "C45S")
      (value "47U")
      (footprint "eagle-import:CAP1210")
      (libsource (lib "eagle-import") (part "CAP1210"))
    )
    (comp (ref "C46A")
      (value "100N")
      (footprint "eagle-import:CAP0402")
      (libsource (lib "eagle-import") (part "CAP0402"))
    )
    (comp (ref "C46B")
      (value "100N")
      (footprint "eagle-import:CAP0402")
      (libsource (lib "eagle-import") (part "CAP0402"))
    )
    (comp (ref "C46C")
      (value "100N")
      (footprint "eagle-import:CAP0402")
      (libsource (lib "eagle-import") (part "CAP0402"))
    )
    (comp (ref "C46D")
      (value "100N")
      (footprint "eagle-import:CAP0402")
      (libsource (lib "eagle-import") (part "CAP0402"))
    )
    (comp (ref "C46E")
      (value "100N")
      (footprint "eagle-import:CAP0402")
      (libsource (lib "eagle-import") (part "CAP0402"))
    )
    (comp (ref "C46S")
      (value "47U")
      (footprint "eagle-import:CAP1210")
      (libsource (lib "eagle-import") (part "CAP1210"))
    )
    (comp (ref "C47A")
      (value "100N")
      (footprint "eagle-import:CAP0402")
      (libsource (lib "eagle-import") (part "CAP0402"))
    )
    (comp (ref "C47B")
      (value "100N")
      (footprint "eagle-import:CAP0402")
      (libsource (lib "eagle-import") (part "CAP0402"))
    )
    (comp (ref "C47C")
      (value "100N")
      (footprint "eagle-import:CAP0402")
      (libsource (lib "eagle-import") (part "CAP0402"))
    )
    (comp (ref "C47D")
      (value "100N")
      (footprint "eagle-import:CAP0402")
      (libsource (lib "eagle-import") (part "CAP0402"))
    )
    (comp (ref "C47E")
      (value "100N")
      (footprint "eagle-import:CAP0402")
      (libsource (lib "eagle-import") (part "CAP0402"))
    )
    (comp (ref "C47S")
      (value "47U")
      (footprint "eagle-import:CAP1210")
      (libsource (lib "eagle-import") (part "CAP1210"))
    )
    (comp (ref "C48A")
      (value "100N")
      (footprint "eagle-import:CAP0402")
      (libsource (lib "eagle-import") (part "CAP0402"))
    )
    (comp (ref "C48B")
      (value "100N")
      (footprint "eagle-import:CAP0402")
      (libsource (lib "eagle-import") (part "CAP0402"))
    )
    (comp (ref "C48C")
      (value "100N")
      (footprint "eagle-import:CAP0402")
      (libsource (lib "eagle-import") (part "CAP0402"))
    )
    (comp (ref "C48D")
      (value "100N")
      (footprint "eagle-import:CAP0402")
      (libsource (lib "eagle-import") (part "CAP0402"))
    )
    (comp (ref "C48E")
      (value "100N")
      (footprint "eagle-import:CAP0402")
      (libsource (lib "eagle-import") (part "CAP0402"))
    )
    (comp (ref "C48S")
      (value "47U")
      (footprint "eagle-import:CAP1210")
      (libsource (lib "eagle-import") (part "CAP1210"))
    )
    (comp (ref "C49A")
      (value "100N")
      (footprint "eagle-import:CAP0402")
      (libsource (lib "eagle-import") (part "CAP0402"))
    )
    (comp (ref "C49B")
      (value "100N")
      (footprint "eagle-import:CAP0402")
      (libsource (lib "eagle-import") (part "CAP0402"))
    )
    (comp (ref "C49C")
      (value "100N")
      (footprint "eagle-import:CAP0402")
      (libsource (lib "eagle-import") (part "CAP0402"))
    )
    (comp (ref "C49D")
      (value "100N")
      (footprint "eagle-import:CAP0402")
      (libsource (lib "eagle-import") (part "CAP0402"))
    )
    (comp (ref "C49E")
      (value "100N")
      (footprint "eagle-import:CAP0402")
      (libsource (lib "eagle-import") (part "CAP0402"))
    )
    (comp (ref "C49S")
      (value "47U")
      (footprint "eagle-import:CAP1210")
      (libsource (lib "eagle-import") (part "CAP1210"))
    )
    (comp (ref "C400")
      (value "100N")
      (footprint "eagle-import:CAP0402")
      (libsource (lib "eagle-import") (part "CAP0402"))
    )
    (comp (ref "C401")
      (value "100N")
      (footprint "eagle-import:CAP0402")
      (libsource (lib "eagle-import") (part "CAP0402"))
    )
    (comp (ref "C402")
      (value "100N")
      (footprint "eagle-import:CAP0402")
      (libsource (lib "eagle-import") (part "CAP0402"))
    )
    (comp (ref "C403")
      (value "100N")
      (footprint "eagle-import:CAP0402")
      (libsource (lib "eagle-import") (part "CAP0402"))
    )
    (comp (ref "C404")
      (value "100N")
      (footprint "eagle-import:CAP0402")
      (libsource (lib "eagle-import") (part "CAP0402"))
    )
    (comp (ref "C405")
      (value "100N")
      (footprint "eagle-import:CAP0402")
      (libsource (lib "eagle-import") (part "CAP0402"))
    )
    (comp (ref "C406")
      (value "100N")
      (footprint "eagle-import:CAP0402")
      (libsource (lib "eagle-import") (part "CAP0402"))
    )
    (comp (ref "C407")
      (value "100N")
      (footprint "eagle-import:CAP0402")
      (libsource (lib "eagle-import") (part "CAP0402"))
    )
    (comp (ref "C408")
      (value "100N")
      (footprint "eagle-import:CAP0402")
      (libsource (lib "eagle-import") (part "CAP0402"))
    )
    (comp (ref "C409")
      (value "100N")
      (footprint "eagle-import:CAP0402")
      (libsource (lib "eagle-import") (part "CAP0402"))
    )
    (comp (ref "C410")
      (value "100N")
      (footprint "eagle-import:CAP0402")
      (libsource (lib "eagle-import") (part "CAP0402"))
    )
    (comp (ref "C411")
      (value "100N")
      (footprint "eagle-import:CAP0402")
      (libsource (lib "eagle-import") (part "CAP0402"))
    )
    (comp (ref "C412")
      (value "100N")
      (footprint "eagle-import:CAP0402")
      (libsource (lib "eagle-import") (part "CAP0402"))
    )
    (comp (ref "C413")
      (value "100N")
      (footprint "eagle-import:CAP0402")
      (libsource (lib "eagle-import") (part "CAP0402"))
    )
    (comp (ref "C414")
      (value "100N")
      (footprint "eagle-import:CAP0402")
      (libsource (lib "eagle-import") (part "CAP0402"))
    )
    (comp (ref "C415")
      (value "100N")
      (footprint "eagle-import:CAP0402")
      (libsource (lib "eagle-import") (part "CAP0402"))
    )
    (comp (ref "C416")
      (value "100N")
      (footprint "eagle-import:CAP0402")
      (libsource (lib "eagle-import") (part "CAP0402"))
    )
    (comp (ref "C417")
      (value "100N")
      (footprint "eagle-import:CAP0402")
      (libsource (lib "eagle-import") (part "CAP0402"))
    )
    (comp (ref "C418")
      (value "100N")
      (footprint "eagle-import:CAP0402")
      (libsource (lib "eagle-import") (part "CAP0402"))
    )
    (comp (ref "C419")
      (value "100N")
      (footprint "eagle-import:CAP0402")
      (libsource (lib "eagle-import") (part "CAP0402"))
    )
    (comp (ref "C420")
      (value "100N")
      (footprint "eagle-import:CAP0402")
      (libsource (lib "eagle-import") (part "CAP0402"))
    )
    (comp (ref "C421")
      (value "100N")
      (footprint "eagle-import:CAP0402")
      (libsource (lib "eagle-import") (part "CAP0402"))
    )
    (comp (ref "C422")
      (value "100N")
      (footprint "eagle-import:CAP0402")
      (libsource (lib "eagle-import") (part "CAP0402"))
    )
    (comp (ref "C423")
      (value "100N")
      (footprint "eagle-import:CAP0402")
      (libsource (lib "eagle-import") (part "CAP0402"))
    )
    (comp (ref "C424")
      (value "100N")
      (footprint "eagle-import:CAP0402")
      (libsource (lib "eagle-import") (part "CAP0402"))
    )
    (comp (ref "C425")
      (value "100N")
      (footprint "eagle-import:CAP0402")
      (libsource (lib "eagle-import") (part "CAP0402"))
    )
    (comp (ref "C426")
      (value "100N")
      (footprint "eagle-import:CAP0402")
      (libsource (lib "eagle-import") (part "CAP0402"))
    )
    (comp (ref "C427")
      (value "100N")
      (footprint "eagle-import:CAP0402")
      (libsource (lib "eagle-import") (part "CAP0402"))
    )
    (comp (ref "C428")
      (value "100N")
      (footprint "eagle-import:CAP0402")
      (libsource (lib "eagle-import") (part "CAP0402"))
    )
    (comp (ref "C429")
      (value "100N")
      (footprint "eagle-import:CAP0402")
      (libsource (lib "eagle-import") (part "CAP0402"))
    )
    (comp (ref "C430")
      (value "100N")
      (footprint "eagle-import:CAP0402")
      (libsource (lib "eagle-import") (part "CAP0402"))
    )
    (comp (ref "C431")
      (value "100N")
      (footprint "eagle-import:CAP0402")
      (libsource (lib "eagle-import") (part "CAP0402"))
    )
    (comp (ref "C432")
      (value "100N")
      (footprint "eagle-import:CAP0402")
      (libsource (lib "eagle-import") (part "CAP0402"))
    )
    (comp (ref "C433")
      (value "100N")
      (footprint "eagle-import:CAP0402")
      (libsource (lib "eagle-import") (part "CAP0402"))
    )
    (comp (ref "C434")
      (value "100N")
      (footprint "eagle-import:CAP0402")
      (libsource (lib "eagle-import") (part "CAP0402"))
    )
    (comp (ref "C435")
      (value "100N")
      (footprint "eagle-import:CAP0402")
      (libsource (lib "eagle-import") (part "CAP0402"))
    )
    (comp (ref "C436")
      (value "100N")
      (footprint "eagle-import:CAP0402")
      (libsource (lib "eagle-import") (part "CAP0402"))
    )
    (comp (ref "C437")
      (value "100N")
      (footprint "eagle-import:CAP0402")
      (libsource (lib "eagle-import") (part "CAP0402"))
    )
    (comp (ref "C438")
      (value "100N")
      (footprint "eagle-import:CAP0402")
      (libsource (lib "eagle-import") (part "CAP0402"))
    )
    (comp (ref "C439")
      (value "100N")
      (footprint "eagle-import:CAP0402")
      (libsource (lib "eagle-import") (part "CAP0402"))
    )
    (comp (ref "C440")
      (value "100N")
      (footprint "eagle-import:CAP0402")
      (libsource (lib "eagle-import") (part "CAP0402"))
    )
    (comp (ref "C441")
      (value "100N")
      (footprint "eagle-import:CAP0402")
      (libsource (lib "eagle-import") (part "CAP0402"))
    )
    (comp (ref "C442")
      (value "100N")
      (footprint "eagle-import:CAP0402")
      (libsource (lib "eagle-import") (part "CAP0402"))
    )
    (comp (ref "C443")
      (value "100N")
      (footprint "eagle-import:CAP0402")
      (libsource (lib "eagle-import") (part "CAP0402"))
    )
    (comp (ref "C444")
      (value "100N")
      (footprint "eagle-import:CAP0402")
      (libsource (lib "eagle-import") (part "CAP0402"))
    )
    (comp (ref "C445")
      (value "100N")
      (footprint "eagle-import:CAP0402")
      (libsource (lib "eagle-import") (part "CAP0402"))
    )
    (comp (ref "C446")
      (value "100N")
      (footprint "eagle-import:CAP0402")
      (libsource (lib "eagle-import") (part "CAP0402"))
    )
    (comp (ref "C447")
      (value "100N")
      (footprint "eagle-import:CAP0402")
      (libsource (lib "eagle-import") (part "CAP0402"))
    )
    (comp (ref "C448")
      (value "100N")
      (footprint "eagle-import:CAP0402")
      (libsource (lib "eagle-import") (part "CAP0402"))
    )
    (comp (ref "C449")
      (value "100N")
      (footprint "eagle-import:CAP0402")
      (libsource (lib "eagle-import") (part "CAP0402"))
    )
    (comp (ref "C450")
      (value "100N")
      (footprint "eagle-import:CAP0402")
      (libsource (lib "eagle-import") (part "CAP0402"))
    )
    (comp (ref "C451")
      (value "100N")
      (footprint "eagle-import:CAP0402")
      (libsource (lib "eagle-import") (part "CAP0402"))
    )
    (comp (ref "C452")
      (value "100N")
      (footprint "eagle-import:CAP0402")
      (libsource (lib "eagle-import") (part "CAP0402"))
    )
    (comp (ref "C453")
      (value "100N")
      (footprint "eagle-import:CAP0402")
      (libsource (lib "eagle-import") (part "CAP0402"))
    )
    (comp (ref "C454")
      (value "100N")
      (footprint "eagle-import:CAP0402")
      (libsource (lib "eagle-import") (part "CAP0402"))
    )
    (comp (ref "C455")
      (value "100N")
      (footprint "eagle-import:CAP0402")
      (libsource (lib "eagle-import") (part "CAP0402"))
    )
    (comp (ref "C456")
      (value "100N")
      (footprint "eagle-import:CAP0402")
      (libsource (lib "eagle-import") (part "CAP0402"))
    )
    (comp (ref "C457")
      (value "100N")
      (footprint "eagle-import:CAP0402")
      (libsource (lib "eagle-import") (part "CAP0402"))
    )
    (comp (ref "C458")
      (value "100N")
      (footprint "eagle-import:CAP0402")
      (libsource (lib "eagle-import") (part "CAP0402"))
    )
    (comp (ref "C459")
      (value "100N")
      (footprint "eagle-import:CAP0402")
      (libsource (lib "eagle-import") (part "CAP0402"))
    )
    (comp (ref "C460")
      (value "100N")
      (footprint "eagle-import:CAP0402")
      (libsource (lib "eagle-import") (part "CAP0402"))
    )
    (comp (ref "C461")
      (value "100N")
      (footprint "eagle-import:CAP0402")
      (libsource (lib "eagle-import") (part "CAP0402"))
    )
    (comp (ref "C462")
      (value "100N")
      (footprint "eagle-import:CAP0402")
      (libsource (lib "eagle-import") (part "CAP0402"))
    )
    (comp (ref "C463")
      (value "100N")
      (footprint "eagle-import:CAP0402")
      (libsource (lib "eagle-import") (part "CAP0402"))
    )
    (comp (ref "C464")
      (value "100N")
      (footprint "eagle-import:CAP0402")
      (libsource (lib "eagle-import") (part "CAP0402"))
    )
    (comp (ref "C465")
      (value "100N")
      (footprint "eagle-import:CAP0402")
      (libsource (lib "eagle-import") (part "CAP0402"))
    )
    (comp (ref "C466")
      (value "100N")
      (footprint "eagle-import:CAP0402")
      (libsource (lib "eagle-import") (part "CAP0402"))
    )
    (comp (ref "C467")
      (value "100N")
      (footprint "eagle-import:CAP0402")
      (libsource (lib "eagle-import") (part "CAP0402"))
    )
    (comp (ref "C468")
      (value "100N")
      (footprint "eagle-import:CAP0402")
      (libsource (lib "eagle-import") (part "CAP0402"))
    )
    (comp (ref "C469")
      (value "100N")
      (footprint "eagle-import:CAP0402")
      (libsource (lib "eagle-import") (part "CAP0402"))
    )
    (comp (ref "C470")
      (value "100N")
      (footprint "eagle-import:CAP0402")
      (libsource (lib "eagle-import") (part "CAP0402"))
    )
    (comp (ref "C471")
      (value "100N")
      (footprint "eagle-import:CAP0402")
      (libsource (lib "eagle-import") (part "CAP0402"))
    )
    (comp (ref "C472")
      (value "100N")
      (footprint "eagle-import:CAP0402")
      (libsource (lib "eagle-import") (part "CAP0402"))
    )
    (comp (ref "C473")
      (value "100N")
      (footprint "eagle-import:CAP0402")
      (libsource (lib "eagle-import") (part "CAP0402"))
    )
    (comp (ref "C474")
      (value "100N")
      (footprint "eagle-import:CAP0402")
      (libsource (lib "eagle-import") (part "CAP0402"))
    )
    (comp (ref "C475")
      (value "100N")
      (footprint "eagle-import:CAP0402")
      (libsource (lib "eagle-import") (part "CAP0402"))
    )
    (comp (ref "C476")
      (value "100N")
      (footprint "eagle-import:CAP0402")
      (libsource (lib "eagle-import") (part "CAP0402"))
    )
    (comp (ref "C477")
      (value "100N")
      (footprint "eagle-import:CAP0402")
      (libsource (lib "eagle-import") (part "CAP0402"))
    )
    (comp (ref "C478")
      (value "100N")
      (footprint "eagle-import:CAP0402")
      (libsource (lib "eagle-import") (part "CAP0402"))
    )
    (comp (ref "C479")
      (value "100N")
      (footprint "eagle-import:CAP0402")
      (libsource (lib "eagle-import") (part "CAP0402"))
    )
    (comp (ref "C480")
      (value "100N")
      (footprint "eagle-import:CAP0402")
      (libsource (lib "eagle-import") (part "CAP0402"))
    )
    (comp (ref "C481")
      (value "100N")
      (footprint "eagle-import:CAP0402")
      (libsource (lib "eagle-import") (part "CAP0402"))
    )
    (comp (ref "C482")
      (value "100N")
      (footprint "eagle-import:CAP0402")
      (libsource (lib "eagle-import") (part "CAP0402"))
    )
    (comp (ref "C483")
      (value "100N")
      (footprint "eagle-import:CAP0402")
      (libsource (lib "eagle-import") (part "CAP0402"))
    )
    (comp (ref "C484")
      (value "100N")
      (footprint "eagle-import:CAP0402")
      (libsource (lib "eagle-import") (part "CAP0402"))
    )
    (comp (ref "C485")
      (value "100N")
      (footprint "eagle-import:CAP0402")
      (libsource (lib "eagle-import") (part "CAP0402"))
    )
    (comp (ref "C486")
      (value "100N")
      (footprint "eagle-import:CAP0402")
      (libsource (lib "eagle-import") (part "CAP0402"))
    )
    (comp (ref "C487")
      (value "100N")
      (footprint "eagle-import:CAP0402")
      (libsource (lib "eagle-import") (part "CAP0402"))
    )
    (comp (ref "C488")
      (value "100N")
      (footprint "eagle-import:CAP0402")
      (libsource (lib "eagle-import") (part "CAP0402"))
    )
    (comp (ref "C489")
      (value "100N")
      (footprint "eagle-import:CAP0402")
      (libsource (lib "eagle-import") (part "CAP0402"))
    )
    (comp (ref "C490")
      (value "100N")
      (footprint "eagle-import:CAP0402")
      (libsource (lib "eagle-import") (part "CAP0402"))
    )
    (comp (ref "C491")
      (value "100N")
      (footprint "eagle-import:CAP0402")
      (libsource (lib "eagle-import") (part "CAP0402"))
    )
    (comp (ref "C492")
      (value "100N")
      (footprint "eagle-import:CAP0402")
      (libsource (lib "eagle-import") (part "CAP0402"))
    )
    (comp (ref "C493")
      (value "100N")
      (footprint "eagle-import:CAP0402")
      (libsource (lib "eagle-import") (part "CAP0402"))
    )
    (comp (ref "C494")
      (value "100N")
      (footprint "eagle-import:CAP0402")
      (libsource (lib "eagle-import") (part "CAP0402"))
    )
    (comp (ref "C495")
      (value "100N")
      (footprint "eagle-import:CAP0402")
      (libsource (lib "eagle-import") (part "CAP0402"))
    )
    (comp (ref "C496")
      (value "100N")
      (footprint "eagle-import:CAP0402")
      (libsource (lib "eagle-import") (part "CAP0402"))
    )
    (comp (ref "C497")
      (value "100N")
      (footprint "eagle-import:CAP0402")
      (libsource (lib "eagle-import") (part "CAP0402"))
    )
    (comp (ref "C498")
      (value "100N")
      (footprint "eagle-import:CAP0402")
      (libsource (lib "eagle-import") (part "CAP0402"))
    )
    (comp (ref "C499")
      (value "100N")
      (footprint "eagle-import:CAP0402")
      (libsource (lib "eagle-import") (part "CAP0402"))
    )
    (comp (ref "SJ1")
      (value "SJ2SJ2-S")
      (footprint "eagle-import:SJ2-S")
      (libsource (lib "eagle-import") (part "SJ2SJ2-S"))
    )
    (comp (ref "SJ2")
      (value "SJ2SJ2-S")
      (footprint "eagle-import:SJ2-S")
      (libsource (lib "eagle-import") (part "SJ2SJ2-S"))
    )
    (comp (ref "SJ3")
      (value "SJ2SJ2-S")
      (footprint "eagle-import:SJ2-S")
      (libsource (lib "eagle-import") (part "SJ2SJ2-S"))
    )
    (comp (ref "SJ4")
      (value "SJ2SJ2-S")
      (footprint "eagle-import:SJ2-S")
      (libsource (lib "eagle-import") (part "SJ2SJ2-S"))
    )
    (comp (ref "SJ5")
      (value "SJ2SJ2-S")
      (footprint "eagle-import:SJ2-S")
      (libsource (lib "eagle-import") (part "SJ2SJ2-S"))
    )
    (comp (ref "SJ6")
      (value "SJ2SJ2-S")
      (footprint "eagle-import:SJ2-S")
      (libsource (lib "eagle-import") (part "SJ2SJ2-S"))
    )
    (comp (ref "SJ7")
      (value "SJ2SJ2-S")
      (footprint "eagle-import:SJ2-S")
      (libsource (lib "eagle-import") (part "SJ2SJ2-S"))
    )
    (comp (ref "SJ8")
      (value "SJ2SJ2-S")
      (footprint "eagle-import:SJ2-S")
      (libsource (lib "eagle-import") (part "SJ2SJ2-S"))
    )
    (comp (ref "SJ9")
      (value "SJ2SJ2-S")
      (footprint "eagle-import:SJ2-S")
      (libsource (lib "eagle-import") (part "SJ2SJ2-S"))
    )
    (comp (ref "SJ10")
      (value "SJ2SJ2-S")
      (footprint "eagle-import:SJ2-S")
      (libsource (lib "eagle-import") (part "SJ2SJ2-S"))
    )
    (comp (ref "SJ11")
      (value "SJ2SJ2-S")
      (footprint "eagle-import:SJ2-S")
      (libsource (lib "eagle-import") (part "SJ2SJ2-S"))
    )
    (comp (ref "SJ12")
      (value "SJ2SJ2-S")
      (footprint "eagle-import:SJ2-S")
      (libsource (lib "eagle-import") (part "SJ2SJ2-S"))
    )
    (comp (ref "SJ13")
      (value "SJ2SJ2-S")
      (footprint "eagle-import:SJ2-S")
      (libsource (lib "eagle-import") (part "SJ2SJ2-S"))
    )
    (comp (ref "SJ14")
      (value "SJ2SJ2-S")
      (footprint "eagle-import:SJ2-S")
      (libsource (lib "eagle-import") (part "SJ2SJ2-S"))
    )
    (comp (ref "SJ15")
      (value "SJ2SJ2-S")
      (footprint "eagle-import:SJ2-S")
      (libsource (lib "eagle-import") (part "SJ2SJ2-S"))
    )
    (comp (ref "SJ16")
      (value "SJ2SJ2-S")
      (footprint "eagle-import:SJ2-S")
      (libsource (lib "eagle-import") (part "SJ2SJ2-S"))
    )
    (comp (ref "SJ17")
      (value "SJ2SJ2-S")
      (footprint "eagle-import:SJ2-S")
      (libsource (lib "eagle-import") (part "SJ2SJ2-S"))
    )
    (comp (ref "SJ18")
      (value "SJ2SJ2-S")
      (footprint "eagle-import:SJ2-S")
      (libsource (lib "eagle-import") (part "SJ2SJ2-S"))
    )
    (comp (ref "SJ19")
      (value "SJ2SJ2-S")
      (footprint "eagle-import:SJ2-S")
      (libsource (lib "eagle-import") (part "SJ2SJ2-S"))
    )
    (comp (ref "SJ20")
      (value "SJ2SJ2-S")
      (footprint "eagle-import:SJ2-S")
      (libsource (lib "eagle-import") (part "SJ2SJ2-S"))
    )
    (comp (ref "SJ21")
      (value "SJ2SJ2-S")
      (footprint "eagle-import:SJ2-S")
      (libsource (lib "eagle-import") (part "SJ2SJ2-S"))
    )
    (comp (ref "SJ22")
      (value "SJ2SJ2-S")
      (footprint "eagle-import:SJ2-S")
      (libsource (lib "eagle-import") (part "SJ2SJ2-S"))
    )
    (comp (ref "SJ23")
      (value "SJ2SJ2-S")
      (footprint "eagle-import:SJ2-S")
      (libsource (lib "eagle-import") (part "SJ2SJ2-S"))
    )
    (comp (ref "SJ24")
      (value "SJ2SJ2-S")
      (footprint "eagle-import:SJ2-S")
      (libsource (lib "eagle-import") (part "SJ2SJ2-S"))
    )
    (comp (ref "SJ25")
      (value "SJ2SJ2-S")
      (footprint "eagle-import:SJ2-S")
      (libsource (lib "eagle-import") (part "SJ2SJ2-S"))
    )
    (comp (ref "SJ26")
      (value "SJ2SJ2-S")
      (footprint "eagle-import:SJ2-S")
      (libsource (lib "eagle-import") (part "SJ2SJ2-S"))
    )
    (comp (ref "SJ27")
      (value "SJ2SJ2-S")
      (footprint "eagle-import:SJ2-S")
      (libsource (lib "eagle-import") (part "SJ2SJ2-S"))
    )
    (comp (ref "SJ28")
      (value "SJ2SJ2-S")
      (footprint "eagle-import:SJ2-S")
      (libsource (lib "eagle-import") (part "SJ2SJ2-S"))
    )
    (comp (ref "SJ29")
      (value "SJ2SJ2-S")
      (footprint "eagle-import:SJ2-S")
      (libsource (lib "eagle-import") (part "SJ2SJ2-S"))
    )
    (comp (ref "SJ30")
      (value "SJ2SJ2-S")
      (footprint "eagle-import:SJ2-S")
      (libsource (lib "eagle-import") (part "SJ2SJ2-S"))
    )
    (comp (ref "SJ31")
      (value "SJ2SJ2-S")
      (footprint "eagle-import:SJ2-S")
      (libsource (lib "eagle-import") (part "SJ2SJ2-S"))
    )
    (comp (ref "SJ32")
      (value "SJ2SJ2-S")
      (footprint "eagle-import:SJ2-S")
      (libsource (lib "eagle-import") (part "SJ2SJ2-S"))
    )
    (comp (ref "SJ33")
      (value "SJ2SJ2-S")
      (footprint "eagle-import:SJ2-S")
      (libsource (lib "eagle-import") (part "SJ2SJ2-S"))
    )
    (comp (ref "SJ34")
      (value "SJ2SJ2-S")
      (footprint "eagle-import:SJ2-S")
      (libsource (lib "eagle-import") (part "SJ2SJ2-S"))
    )
    (comp (ref "SJ35")
      (value "SJ2SJ2-S")
      (footprint "eagle-import:SJ2-S")
      (libsource (lib "eagle-import") (part "SJ2SJ2-S"))
    )
    (comp (ref "SJ36")
      (value "SJ2SJ2-S")
      (footprint "eagle-import:SJ2-S")
      (libsource (lib "eagle-import") (part "SJ2SJ2-S"))
    )
    (comp (ref "SJ37")
      (value "SJ2SJ2-S")
      (footprint "eagle-import:SJ2-S")
      (libsource (lib "eagle-import") (part "SJ2SJ2-S"))
    )
    (comp (ref "SJ38")
      (value "SJ2SJ2-S")
      (footprint "eagle-import:SJ2-S")
      (libsource (lib "eagle-import") (part "SJ2SJ2-S"))
    )
    (comp (ref "SJ39")
      (value "SJ2SJ2-S")
      (footprint "eagle-import:SJ2-S")
      (libsource (lib "eagle-import") (part "SJ2SJ2-S"))
    )
    (comp (ref "SJ40")
      (value "SJ2SJ2-S")
      (footprint "eagle-import:SJ2-S")
      (libsource (lib "eagle-import") (part "SJ2SJ2-S"))
    )
    (comp (ref "SJ41")
      (value "SJ2SJ2-S")
      (footprint "eagle-import:SJ2-S")
      (libsource (lib "eagle-import") (part "SJ2SJ2-S"))
    )
    (comp (ref "SJ42")
      (value "SJ2SJ2-S")
      (footprint "eagle-import:SJ2-S")
      (libsource (lib "eagle-import") (part "SJ2SJ2-S"))
    )
    (comp (ref "SJ43")
      (value "SJ2SJ2-S")
      (footprint "eagle-import:SJ2-S")
      (libsource (lib "eagle-import") (part "SJ2SJ2-S"))
    )
    (comp (ref "SJ44")
      (value "SJ2SJ2-S")
      (footprint "eagle-import:SJ2-S")
      (libsource (lib "eagle-import") (part "SJ2SJ2-S"))
    )
    (comp (ref "SJ45")
      (value "SJ2SJ2-S")
      (footprint "eagle-import:SJ2-S")
      (libsource (lib "eagle-import") (part "SJ2SJ2-S"))
    )
    (comp (ref "SJ46")
      (value "SJ2SJ2-S")
      (footprint "eagle-import:SJ2-S")
      (libsource (lib "eagle-import") (part "SJ2SJ2-S"))
    )
    (comp (ref "SJ47")
      (value "SJ2SJ2-S")
      (footprint "eagle-import:SJ2-S")
      (libsource (lib "eagle-import") (part "SJ2SJ2-S"))
    )
    (comp (ref "SJ48")
      (value "SJ2SJ2-S")
      (footprint "eagle-import:SJ2-S")
      (libsource (lib "eagle-import") (part "SJ2SJ2-S"))
    )
    (comp (ref "SJ49")
      (value "SJ2SJ2-S")
      (footprint "eagle-import:SJ2-S")
      (libsource (lib "eagle-import") (part "SJ2SJ2-S"))
    )
    (comp (ref "SJ50")
      (value "SJ2SJ2-S")
      (footprint "eagle-import:SJ2-S")
      (libsource (lib "eagle-import") (part "SJ2SJ2-S"))
    )
    (comp (ref "SJ51")
      (value "SJ2SJ2-S")
      (footprint "eagle-import:SJ2-S")
      (libsource (lib "eagle-import") (part "SJ2SJ2-S"))
    )
    (comp (ref "SJ52")
      (value "SJ2SJ2-S")
      (footprint "eagle-import:SJ2-S")
      (libsource (lib "eagle-import") (part "SJ2SJ2-S"))
    )
    (comp (ref "SJ53")
      (value "SJ2SJ2-S")
      (footprint "eagle-import:SJ2-S")
      (libsource (lib "eagle-import") (part "SJ2SJ2-S"))
    )
    (comp (ref "SJ54")
      (value "SJ2SJ2-S")
      (footprint "eagle-import:SJ2-S")
      (libsource (lib "eagle-import") (part "SJ2SJ2-S"))
    )
    (comp (ref "SJ55")
      (value "SJ2SJ2-S")
      (footprint "eagle-import:SJ2-S")
      (libsource (lib "eagle-import") (part "SJ2SJ2-S"))
    )
    (comp (ref "SJ56")
      (value "SJ2SJ2-S")
      (footprint "eagle-import:SJ2-S")
      (libsource (lib "eagle-import") (part "SJ2SJ2-S"))
    )
    (comp (ref "SJ57")
      (value "SJ2SJ2-S")
      (footprint "eagle-import:SJ2-S")
      (libsource (lib "eagle-import") (part "SJ2SJ2-S"))
    )
    (comp (ref "SJ58")
      (value "SJ2SJ2-S")
      (footprint "eagle-import:SJ2-S")
      (libsource (lib "eagle-import") (part "SJ2SJ2-S"))
    )
    (comp (ref "SJ59")
      (value "SJ2SJ2-S")
      (footprint "eagle-import:SJ2-S")
      (libsource (lib "eagle-import") (part "SJ2SJ2-S"))
    )
    (comp (ref "SJ60")
      (value "SJ2SJ2-S")
      (footprint "eagle-import:SJ2-S")
      (libsource (lib "eagle-import") (part "SJ2SJ2-S"))
    )
    (comp (ref "SJ61")
      (value "SJ2SJ2-S")
      (footprint "eagle-import:SJ2-S")
      (libsource (lib "eagle-import") (part "SJ2SJ2-S"))
    )
    (comp (ref "SJ62")
      (value "SJ2SJ2-S")
      (footprint "eagle-import:SJ2-S")
      (libsource (lib "eagle-import") (part "SJ2SJ2-S"))
    )
    (comp (ref "SJ63")
      (value "SJ2SJ2-S")
      (footprint "eagle-import:SJ2-S")
      (libsource (lib "eagle-import") (part "SJ2SJ2-S"))
    )
    (comp (ref "SJ64")
      (value "SJ2SJ2-S")
      (footprint "eagle-import:SJ2-S")
      (libsource (lib "eagle-import") (part "SJ2SJ2-S"))
    )
    (comp (ref "U4A")
      (value "BITFURY")
      (footprint "eagle-import:QNF48")
      (libsource (lib "eagle-import") (part "BITFURY"))
    )
    (comp (ref "U4B")
      (value "BITFURY")
      (footprint "eagle-import:QNF48")
      (libsource (lib "eagle-import") (part "BITFURY"))
    )
    (comp (ref "U4C")
      (value "BITFURY")
      (footprint "eagle-import:QNF48")
      (libsource (lib "eagle-import") (part "BITFURY"))
    )
    (comp (ref "U4D")
      (value "BITFURY")
      (footprint "eagle-import:QNF48")
      (libsource (lib "eagle-import") (part "BITFURY"))
    )
    (comp (ref "U4E")
      (value "BITFURY")
      (footprint "eagle-import:QNF48")
      (libsource (lib "eagle-import") (part "BITFURY"))
    )
    (comp (ref "U4F")
      (value "BITFURY")
      (footprint "eagle-import:QNF48")
      (libsource (lib "eagle-import") (part "BITFURY"))
    )
    (comp (ref "U40")
      (value "BITFURY")
      (footprint "eagle-import:QNF48")
      (libsource (lib "eagle-import") (part "BITFURY"))
    )
    (comp (ref "U41")
      (value "BITFURY")
      (footprint "eagle-import:QNF48")
      (libsource (lib "eagle-import") (part "BITFURY"))
    )
    (comp (ref "U42")
      (value "BITFURY")
      (footprint "eagle-import:QNF48")
      (libsource (lib "eagle-import") (part "BITFURY"))
    )
    (comp (ref "U43")
      (value "BITFURY")
      (footprint "eagle-import:QNF48")
      (libsource (lib "eagle-import") (part "BITFURY"))
    )
    (comp (ref "U44")
      (value "BITFURY")
      (footprint "eagle-import:QNF48")
      (libsource (lib "eagle-import") (part "BITFURY"))
    )
    (comp (ref "U45")
      (value "BITFURY")
      (footprint "eagle-import:QNF48")
      (libsource (lib "eagle-import") (part "BITFURY"))
    )
    (comp (ref "U46")
      (value "BITFURY")
      (footprint "eagle-import:QNF48")
      (libsource (lib "eagle-import") (part "BITFURY"))
    )
    (comp (ref "U47")
      (value "BITFURY")
      (footprint "eagle-import:QNF48")
      (libsource (lib "eagle-import") (part "BITFURY"))
    )
    (comp (ref "U48")
      (value "BITFURY")
      (footprint "eagle-import:QNF48")
      (libsource (lib "eagle-import") (part "BITFURY"))
    )
    (comp (ref "U49")
      (value "BITFURY")
      (footprint "eagle-import:QNF48")
      (libsource (lib "eagle-import") (part "BITFURY"))
    )
  )
  (nets
    (net (code "1") (name "CLK0") (class "Default")
      (node (ref "SJ49") (pin "2") (pinfunction "P$2_2") (pintype "passive"))
      (node (ref "SJ50") (pin "1") (pinfunction "P$1_1") (pintype "passive"))
      (node (ref "U40") (pin "5") (pinfunction "5.OUTCLK_5") (pintype "passive"))
      (node (ref "U41") (pin "12") (pinfunction "12.INCLK_12") (pintype "passive"))
    )
    (net (code "2") (name "CLK1") (class "Default")
      (node (ref "SJ50") (pin "2") (pinfunction "P$2_2") (pintype "passive"))
      (node (ref "SJ51") (pin "1") (pinfunction "P$1_1") (pintype "passive"))
      (node (ref "U41") (pin "5") (pinfunction "5.OUTCLK_5") (pintype "passive"))
      (node (ref "U42") (pin "12") (pinfunction "12.INCLK_12") (pintype "passive"))
    )
    (net (code "3") (name "CLK2") (class "Default")
      (node (ref "SJ51") (pin "2") (pinfunction "P$2_2") (pintype "passive"))
      (node (ref "SJ52") (pin "1") (pinfunction "P$1_1") (pintype "passive"))
      (node (ref "U42") (pin "5") (pinfunction "5.OUTCLK_5") (pintype "passive"))
      (node (ref "U43") (pin "12") (pinfunction "12.INCLK_12") (pintype "passive"))
    )
    (net (code "4") (name "CLK3") (class "Default")
      (node (ref "SJ52") (pin "2") (pinfunction "P$2_2") (pintype "passive"))
      (node (ref "SJ53") (pin "1") (pinfunction "P$1_1") (pintype "passive"))
      (node (ref "U43") (pin "5") (pinfunction "5.OUTCLK_5") (pintype "passive"))
      (node (ref "U44") (pin "12") (pinfunction "12.INCLK_12") (pintype "passive"))
    )
    (net (code "5") (name "CLK4") (class "Default")
      (node (ref "SJ53") (pin "2") (pinfunction "P$2_2") (pintype "passive"))
      (node (ref "SJ54") (pin "1") (pinfunction "P$1_1") (pintype "passive"))
      (node (ref "U44") (pin "5") (pinfunction "5.OUTCLK_5") (pintype "passive"))
      (node (ref "U45") (pin "12") (pinfunction "12.INCLK_12") (pintype "passive"))
    )
    (net (code "6") (name "CLK5") (class "Default")
      (node (ref "SJ54") (pin "2") (pinfunction "P$2_2") (pintype "passive"))
      (node (ref "SJ55") (pin "1") (pinfunction "P$1_1") (pintype "passive"))
      (node (ref "U45") (pin "5") (pinfunction "5.OUTCLK_5") (pintype "passive"))
      (node (ref "U46") (pin "12") (pinfunction "12.INCLK_12") (pintype "passive"))
    )
    (net (code "7") (name "CLK6") (class "Default")
      (node (ref "SJ55") (pin "2") (pinfunction "P$2_2") (pintype "passive"))
      (node (ref "SJ56") (pin "1") (pinfunction "P$1_1") (pintype "passive"))
      (node (ref "U46") (pin "5") (pinfunction "5.OUTCLK_5") (pintype "passive"))
      (node (ref "U47") (pin "12") (pinfunction "12.INCLK_12") (pintype "passive"))
    )
    (net (code "8") (name "CLK7") (class "Default")
      (node (ref "SJ56") (pin "2") (pinfunction "P$2_2") (pintype "passive"))
      (node (ref "SJ57") (pin "1") (pinfunction "P$1_1") (pintype "passive"))
      (node (ref "U47") (pin "5") (pinfunction "5.OUTCLK_5") (pintype "passive"))
      (node (ref "U48") (pin "12") (pinfunction "12.INCLK_12") (pintype "passive"))
    )
    (net (code "9") (name "CLK8") (class "Default")
      (node (ref "SJ57") (pin "2") (pinfunction "P$2_2") (pintype "passive"))
      (node (ref "SJ58") (pin "1") (pinfunction "P$1_1") (pintype "passive"))
      (node (ref "U48") (pin "5") (pinfunction "5.OUTCLK_5") (pintype "passive"))
      (node (ref "U49") (pin "12") (pinfunction "12.INCLK_12") (pintype "passive"))
    )
    (net (code "10") (name "CLK9") (class "Default")
      (node (ref "SJ58") (pin "2") (pinfunction "P$2_2") (pintype "passive"))
      (node (ref "SJ59") (pin "1") (pinfunction "P$1_1") (pintype "passive"))
      (node (ref "U49") (pin "5") (pinfunction "5.OUTCLK_5") (pintype "passive"))
      (node (ref "U4A") (pin "12") (pinfunction "12.INCLK_12") (pintype "passive"))
    )
    (net (code "11") (name "CLK10") (class "Default")
      (node (ref "SJ59") (pin "2") (pinfunction "P$2_2") (pintype "passive"))
      (node (ref "SJ60") (pin "1") (pinfunction "P$1_1") (pintype "passive"))
      (node (ref "U4A") (pin "5") (pinfunction "5.OUTCLK_5") (pintype "passive"))
      (node (ref "U4B") (pin "12") (pinfunction "12.INCLK_12") (pintype "passive"))
    )
    (net (code "12") (name "CLK11") (class "Default")
      (node (ref "SJ60") (pin "2") (pinfunction "P$2_2") (pintype "passive"))
      (node (ref "SJ61") (pin "1") (pinfunction "P$1_1") (pintype "passive"))
      (node (ref "U4B") (pin "5") (pinfunction "5.OUTCLK_5") (pintype "passive"))
      (node (ref "U4C") (pin "12") (pinfunction "12.INCLK_12") (pintype "passive"))
    )
    (net (code "13") (name "CLK12") (class "Default")
      (node (ref "SJ61") (pin "2") (pinfunction "P$2_2") (pintype "passive"))
      (node (ref "SJ62") (pin "1") (pinfunction "P$1_1") (pintype "passive"))
      (node (ref "U4C") (pin "5") (pinfunction "5.OUTCLK_5") (pintype "passive"))
      (node (ref "U4D") (pin "12") (pinfunction "12.INCLK_12") (pintype "passive"))
    )
    (net (code "14") (name "CLK13") (class "Default")
      (node (ref "SJ62") (pin "2") (pinfunction "P$2_2") (pintype "passive"))
      (node (ref "SJ63") (pin "1") (pinfunction "P$1_1") (pintype "passive"))
      (node (ref "U4D") (pin "5") (pinfunction "5.OUTCLK_5") (pintype "passive"))
      (node (ref "U4E") (pin "12") (pinfunction "12.INCLK_12") (pintype "passive"))
    )
    (net (code "15") (name "CLK14") (class "Default")
      (node (ref "SJ63") (pin "2") (pinfunction "P$2_2") (pintype "passive"))
      (node (ref "SJ64") (pin "1") (pinfunction "P$1_1") (pintype "passive"))
      (node (ref "U4E") (pin "5") (pinfunction "5.OUTCLK_5") (pintype "passive"))
      (node (ref "U4F") (pin "12") (pinfunction "12.INCLK_12") (pintype "passive"))
    )
    (net (code "16") (name "GND") (class "Default")
      (node (ref "C01") (pin "2") (pinfunction "2_2") (pintype "passive"))
      (node (ref "C01P") (pin "2") (pinfunction "2_2") (pintype "passive"))
      (node (ref "C01R") (pin "2") (pinfunction "2_2") (pintype "passive"))
      (node (ref "C02") (pin "2") (pinfunction "2_2") (pintype "passive"))
      (node (ref "C03") (pin "2") (pinfunction "2_2") (pintype "passive"))
      (node (ref "C04") (pin "2") (pinfunction "2_2") (pintype "passive"))
      (node (ref "C05") (pin "2") (pinfunction "2_2") (pintype "passive"))
      (node (ref "C06") (pin "-") (pinfunction "-_-") (pintype "passive"))
      (node (ref "C12") (pin "2") (pinfunction "2_2") (pintype "passive"))
      (node (ref "C13") (pin "2") (pinfunction "2_2") (pintype "passive"))
      (node (ref "C14") (pin "2") (pinfunction "2_2") (pintype "passive"))
      (node (ref "C15") (pin "2") (pinfunction "2_2") (pintype "passive"))
      (node (ref "C16") (pin "2") (pinfunction "2_2") (pintype "passive"))
      (node (ref "C400") (pin "2") (pinfunction "2_2") (pintype "passive"))
      (node (ref "C401") (pin "2") (pinfunction "2_2") (pintype "passive"))
      (node (ref "C402") (pin "2") (pinfunction "2_2") (pintype "passive"))
      (node (ref "C403") (pin "2") (pinfunction "2_2") (pintype "passive"))
      (node (ref "C404") (pin "2") (pinfunction "2_2") (pintype "passive"))
      (node (ref "C405") (pin "2") (pinfunction "2_2") (pintype "passive"))
      (node (ref "C406") (pin "2") (pinfunction "2_2") (pintype "passive"))
      (node (ref "C407") (pin "2") (pinfunction "2_2") (pintype "passive"))
      (node (ref "C408") (pin "2") (pinfunction "2_2") (pintype "passive"))
      (node (ref "C409") (pin "2") (pinfunction "2_2") (pintype "passive"))
      (node (ref "C40A") (pin "2") (pinfunction "2_2") (pintype "passive"))
      (node (ref "C40B") (pin "2") (pinfunction "2_2") (pintype "passive"))
      (node (ref "C40C") (pin "2") (pinfunction "2_2") (pintype "passive"))
      (node (ref "C40D") (pin "2") (pinfunction "2_2") (pintype "passive"))
      (node (ref "C40E") (pin "2") (pinfunction "2_2") (pintype "passive"))
      (node (ref "C40S") (pin "2") (pinfunction "2_2") (pintype "passive"))
      (node (ref "C410") (pin "2") (pinfunction "2_2") (pintype "passive"))
      (node (ref "C411") (pin "2") (pinfunction "2_2") (pintype "passive"))
      (node (ref "C412") (pin "2") (pinfunction "2_2") (pintype "passive"))
      (node (ref "C413") (pin "2") (pinfunction "2_2") (pintype "passive"))
      (node (ref "C414") (pin "2") (pinfunction "2_2") (pintype "passive"))
      (node (ref "C415") (pin "2") (pinfunction "2_2") (pintype "passive"))
      (node (ref "C416") (pin "2") (pinfunction "2_2") (pintype "passive"))
      (node (ref "C417") (pin "2") (pinfunction "2_2") (pintype "passive"))
      (node (ref "C418") (pin "2") (pinfunction "2_2") (pintype "passive"))
      (node (ref "C419") (pin "2") (pinfunction "2_2") (pintype "passive"))
      (node (ref "C41A") (pin "2") (pinfunction "2_2") (pintype "passive"))
      (node (ref "C41B") (pin "2") (pinfunction "2_2") (pintype "passive"))
      (node (ref "C41C") (pin "2") (pinfunction "2_2") (pintype "passive"))
      (node (ref "C41D") (pin "2") (pinfunction "2_2") (pintype "passive"))
      (node (ref "C41E") (pin "2") (pinfunction "2_2") (pintype "passive"))
      (node (ref "C41S") (pin "2") (pinfunction "2_2") (pintype "passive"))
      (node (ref "C420") (pin "2") (pinfunction "2_2") (pintype "passive"))
      (node (ref "C421") (pin "2") (pinfunction "2_2") (pintype "passive"))
      (node (ref "C422") (pin "2") (pinfunction "2_2") (pintype "passive"))
      (node (ref "C423") (pin "2") (pinfunction "2_2") (pintype "passive"))
      (node (ref "C424") (pin "2") (pinfunction "2_2") (pintype "passive"))
      (node (ref "C425") (pin "2") (pinfunction "2_2") (pintype "passive"))
      (node (ref "C426") (pin "2") (pinfunction "2_2") (pintype "passive"))
      (node (ref "C427") (pin "2") (pinfunction "2_2") (pintype "passive"))
      (node (ref "C428") (pin "2") (pinfunction "2_2") (pintype "passive"))
      (node (ref "C429") (pin "2") (pinfunction "2_2") (pintype "passive"))
      (node (ref "C42A") (pin "2") (pinfunction "2_2") (pintype "passive"))
      (node (ref "C42B") (pin "2") (pinfunction "2_2") (pintype "passive"))
      (node (ref "C42C") (pin "2") (pinfunction "2_2") (pintype "passive"))
      (node (ref "C42D") (pin "2") (pinfunction "2_2") (pintype "passive"))
      (node (ref "C42E") (pin "2") (pinfunction "2_2") (pintype "passive"))
      (node (ref "C42S") (pin "2") (pinfunction "2_2") (pintype "passive"))
      (node (ref "C430") (pin "2") (pinfunction "2_2") (pintype "passive"))
      (node (ref "C431") (pin "2") (pinfunction "2_2") (pintype "passive"))
      (node (ref "C432") (pin "2") (pinfunction "2_2") (pintype "passive"))
      (node (ref "C433") (pin "2") (pinfunction "2_2") (pintype "passive"))
      (node (ref "C434") (pin "2") (pinfunction "2_2") (pintype "passive"))
      (node (ref "C435") (pin "2") (pinfunction "2_2") (pintype "passive"))
      (node (ref "C436") (pin "2") (pinfunction "2_2") (pintype "passive"))
      (node (ref "C437") (pin "2") (pinfunction "2_2") (pintype "passive"))
      (node (ref "C438") (pin "2") (pinfunction "2_2") (pintype "passive"))
      (node (ref "C439") (pin "2") (pinfunction "2_2") (pintype "passive"))
      (node (ref "C43A") (pin "2") (pinfunction "2_2") (pintype "passive"))
      (node (ref "C43B") (pin "2") (pinfunction "2_2") (pintype "passive"))
      (node (ref "C43C") (pin "2") (pinfunction "2_2") (pintype "passive"))
      (node (ref "C43D") (pin "2") (pinfunction "2_2") (pintype "passive"))
      (node (ref "C43E") (pin "2") (pinfunction "2_2") (pintype "passive"))
      (node (ref "C43S") (pin "2") (pinfunction "2_2") (pintype "passive"))
      (node (ref "C440") (pin "2") (pinfunction "2_2") (pintype "passive"))
      (node (ref "C441") (pin "2") (pinfunction "2_2") (pintype "passive"))
      (node (ref "C442") (pin "2") (pinfunction "2_2") (pintype "passive"))
      (node (ref "C443") (pin "2") (pinfunction "2_2") (pintype "passive"))
      (node (ref "C444") (pin "2") (pinfunction "2_2") (pintype "passive"))
      (node (ref "C445") (pin "2") (pinfunction "2_2") (pintype "passive"))
      (node (ref "C446") (pin "2") (pinfunction "2_2") (pintype "passive"))
      (node (ref "C447") (pin "2") (pinfunction "2_2") (pintype "passive"))
      (node (ref "C448") (pin "2") (pinfunction "2_2") (pintype "passive"))
      (node (ref "C449") (pin "2") (pinfunction "2_2") (pintype "passive"))
      (node (ref "C44A") (pin "2") (pinfunction "2_2") (pintype "passive"))
      (node (ref "C44B") (pin "2") (pinfunction "2_2") (pintype "passive"))
      (node (ref "C44C") (pin "2") (pinfunction "2_2") (pintype "passive"))
      (node (ref "C44D") (pin "2") (pinfunction "2_2") (pintype "passive"))
      (node (ref "C44E") (pin "2") (pinfunction "2_2") (pintype "passive"))
      (node (ref "C44S") (pin "2") (pinfunction "2_2") (pintype "passive"))
      (node (ref "C450") (pin "2") (pinfunction "2_2") (pintype "passive"))
      (node (ref "C451") (pin "2") (pinfunction "2_2") (pintype "passive"))
      (node (ref "C452") (pin "2") (pinfunction "2_2") (pintype "passive"))
      (node (ref "C453") (pin "2") (pinfunction "2_2") (pintype "passive"))
      (node (ref "C454") (pin "2") (pinfunction "2_2") (pintype "passive"))
      (node (ref "C455") (pin "2") (pinfunction "2_2") (pintype "passive"))
      (node (ref "C456") (pin "2") (pinfunction "2_2") (pintype "passive"))
      (node (ref "C457") (pin "2") (pinfunction "2_2") (pintype "passive"))
      (node (ref "C458") (pin "2") (pinfunction "2_2") (pintype "passive"))
      (node (ref "C459") (pin "2") (pinfunction "2_2") (pintype "passive"))
      (node (ref "C45A") (pin "2") (pinfunction "2_2") (pintype "passive"))
      (node (ref "C45B") (pin "2") (pinfunction "2_2") (pintype "passive"))
      (node (ref "C45C") (pin "2") (pinfunction "2_2") (pintype "passive"))
      (node (ref "C45D") (pin "2") (pinfunction "2_2") (pintype "passive"))
      (node (ref "C45E") (pin "2") (pinfunction "2_2") (pintype "passive"))
      (node (ref "C45S") (pin "2") (pinfunction "2_2") (pintype "passive"))
      (node (ref "C460") (pin "2") (pinfunction "2_2") (pintype "passive"))
      (node (ref "C461") (pin "2") (pinfunction "2_2") (pintype "passive"))
      (node (ref "C462") (pin "2") (pinfunction "2_2") (pintype "passive"))
      (node (ref "C463") (pin "2") (pinfunction "2_2") (pintype "passive"))
      (node (ref "C464") (pin "2") (pinfunction "2_2") (pintype "passive"))
      (node (ref "C465") (pin "2") (pinfunction "2_2") (pintype "passive"))
      (node (ref "C466") (pin "2") (pinfunction "2_2") (pintype "passive"))
      (node (ref "C467") (pin "2") (pinfunction "2_2") (pintype "passive"))
      (node (ref "C468") (pin "2") (pinfunction "2_2") (pintype "passive"))
      (node (ref "C469") (pin "2") (pinfunction "2_2") (pintype "passive"))
      (node (ref "C46A") (pin "2") (pinfunction "2_2") (pintype "passive"))
      (node (ref "C46B") (pin "2") (pinfunction "2_2") (pintype "passive"))
      (node (ref "C46C") (pin "2") (pinfunction "2_2") (pintype "passive"))
      (node (ref "C46D") (pin "2") (pinfunction "2_2") (pintype "passive"))
      (node (ref "C46E") (pin "2") (pinfunction "2_2") (pintype "passive"))
      (node (ref "C46S") (pin "2") (pinfunction "2_2") (pintype "passive"))
      (node (ref "C470") (pin "2") (pinfunction "2_2") (pintype "passive"))
      (node (ref "C471") (pin "2") (pinfunction "2_2") (pintype "passive"))
      (node (ref "C472") (pin "2") (pinfunction "2_2") (pintype "passive"))
      (node (ref "C473") (pin "2") (pinfunction "2_2") (pintype "passive"))
      (node (ref "C474") (pin "2") (pinfunction "2_2") (pintype "passive"))
      (node (ref "C475") (pin "2") (pinfunction "2_2") (pintype "passive"))
      (node (ref "C476") (pin "2") (pinfunction "2_2") (pintype "passive"))
      (node (ref "C477") (pin "2") (pinfunction "2_2") (pintype "passive"))
      (node (ref "C478") (pin "2") (pinfunction "2_2") (pintype "passive"))
      (node (ref "C479") (pin "2") (pinfunction "2_2") (pintype "passive"))
      (node (ref "C47A") (pin "2") (pinfunction "2_2") (pintype "passive"))
      (node (ref "C47B") (pin "2") (pinfunction "2_2") (pintype "passive"))
      (node (ref "C47C") (pin "2") (pinfunction "2_2") (pintype "passive"))
      (node (ref "C47D") (pin "2") (pinfunction "2_2") (pintype "passive"))
      (node (ref "C47E") (pin "2") (pinfunction "2_2") (pintype "passive"))
      (node (ref "C47S") (pin "2") (pinfunction "2_2") (pintype "passive"))
      (node (ref "C480") (pin "2") (pinfunction "2_2") (pintype "passive"))
      (node (ref "C481") (pin "2") (pinfunction "2_2") (pintype "passive"))
      (node (ref "C482") (pin "2") (pinfunction "2_2") (pintype "passive"))
      (node (ref "C483") (pin "2") (pinfunction "2_2") (pintype "passive"))
      (node (ref "C484") (pin "2") (pinfunction "2_2") (pintype "passive"))
      (node (ref "C485") (pin "2") (pinfunction "2_2") (pintype "passive"))
      (node (ref "C486") (pin "2") (pinfunction "2_2") (pintype "passive"))
      (node (ref "C487") (pin "2") (pinfunction "2_2") (pintype "passive"))
      (node (ref "C488") (pin "2") (pinfunction "2_2") (pintype "passive"))
      (node (ref "C489") (pin "2") (pinfunction "2_2") (pintype "passive"))
      (node (ref "C48A") (pin "2") (pinfunction "2_2") (pintype "passive"))
      (node (ref "C48B") (pin "2") (pinfunction "2_2") (pintype "passive"))
      (node (ref "C48C") (pin "2") (pinfunction "2_2") (pintype "passive"))
      (node (ref "C48D") (pin "2") (pinfunction "2_2") (pintype "passive"))
      (node (ref "C48E") (pin "2") (pinfunction "2_2") (pintype "passive"))
      (node (ref "C48S") (pin "2") (pinfunction "2_2") (pintype "passive"))
      (node (ref "C490") (pin "2") (pinfunction "2_2") (pintype "passive"))
      (node (ref "C491") (pin "2") (pinfunction "2_2") (pintype "passive"))
      (node (ref "C492") (pin "2") (pinfunction "2_2") (pintype "passive"))
      (node (ref "C493") (pin "2") (pinfunction "2_2") (pintype "passive"))
      (node (ref "C494") (pin "2") (pinfunction "2_2") (pintype "passive"))
      (node (ref "C495") (pin "2") (pinfunction "2_2") (pintype "passive"))
      (node (ref "C496") (pin "2") (pinfunction "2_2") (pintype "passive"))
      (node (ref "C497") (pin "2") (pinfunction "2_2") (pintype "passive"))
      (node (ref "C498") (pin "2") (pinfunction "2_2") (pintype "passive"))
      (node (ref "C499") (pin "2") (pinfunction "2_2") (pintype "passive"))
      (node (ref "C49A") (pin "2") (pinfunction "2_2") (pintype "passive"))
      (node (ref "C49B") (pin "2") (pinfunction "2_2") (pintype "passive"))
      (node (ref "C49C") (pin "2") (pinfunction "2_2") (pintype "passive"))
      (node (ref "C49D") (pin "2") (pinfunction "2_2") (pintype "passive"))
      (node (ref "C49E") (pin "2") (pinfunction "2_2") (pintype "passive"))
      (node (ref "C49S") (pin "2") (pinfunction "2_2") (pintype "passive"))
      (node (ref "C4A0") (pin "2") (pinfunction "2_2") (pintype "passive"))
      (node (ref "C4A1") (pin "2") (pinfunction "2_2") (pintype "passive"))
      (node (ref "C4A2") (pin "2") (pinfunction "2_2") (pintype "passive"))
      (node (ref "C4A3") (pin "2") (pinfunction "2_2") (pintype "passive"))
      (node (ref "C4A4") (pin "2") (pinfunction "2_2") (pintype "passive"))
      (node (ref "C4A5") (pin "2") (pinfunction "2_2") (pintype "passive"))
      (node (ref "C4A6") (pin "2") (pinfunction "2_2") (pintype "passive"))
      (node (ref "C4A7") (pin "2") (pinfunction "2_2") (pintype "passive"))
      (node (ref "C4A8") (pin "2") (pinfunction "2_2") (pintype "passive"))
      (node (ref "C4A9") (pin "2") (pinfunction "2_2") (pintype "passive"))
      (node (ref "C4AA") (pin "2") (pinfunction "2_2") (pintype "passive"))
      (node (ref "C4AB") (pin "2") (pinfunction "2_2") (pintype "passive"))
      (node (ref "C4AC") (pin "2") (pinfunction "2_2") (pintype "passive"))
      (node (ref "C4AD") (pin "2") (pinfunction "2_2") (pintype "passive"))
      (node (ref "C4AE") (pin "2") (pinfunction "2_2") (pintype "passive"))
      (node (ref "C4AS") (pin "2") (pinfunction "2_2") (pintype "passive"))
      (node (ref "C4B0") (pin "2") (pinfunction "2_2") (pintype "passive"))
      (node (ref "C4B1") (pin "2") (pinfunction "2_2") (pintype "passive"))
      (node (ref "C4B2") (pin "2") (pinfunction "2_2") (pintype "passive"))
      (node (ref "C4B3") (pin "2") (pinfunction "2_2") (pintype "passive"))
      (node (ref "C4B4") (pin "2") (pinfunction "2_2") (pintype "passive"))
      (node (ref "C4B5") (pin "2") (pinfunction "2_2") (pintype "passive"))
      (node (ref "C4B6") (pin "2") (pinfunction "2_2") (pintype "passive"))
      (node (ref "C4B7") (pin "2") (pinfunction "2_2") (pintype "passive"))
      (node (ref "C4B8") (pin "2") (pinfunction "2_2") (pintype "passive"))
      (node (ref "C4B9") (pin "2") (pinfunction "2_2") (pintype "passive"))
      (node (ref "C4BA") (pin "2") (pinfunction "2_2") (pintype "passive"))
      (node (ref "C4BB") (pin "2") (pinfunction "2_2") (pintype "passive"))
      (node (ref "C4BC") (pin "2") (pinfunction "2_2") (pintype "passive"))
      (node (ref "C4BD") (pin "2") (pinfunction "2_2") (pintype "passive"))
      (node (ref "C4BE") (pin "2") (pinfunction "2_2") (pintype "passive"))
      (node (ref "C4BS") (pin "2") (pinfunction "2_2") (pintype "passive"))
      (node (ref "C4C0") (pin "2") (pinfunction "2_2") (pintype "passive"))
      (node (ref "C4C1") (pin "2") (pinfunction "2_2") (pintype "passive"))
      (node (ref "C4C2") (pin "2") (pinfunction "2_2") (pintype "passive"))
      (node (ref "C4C3") (pin "2") (pinfunction "2_2") (pintype "passive"))
      (node (ref "C4C4") (pin "2") (pinfunction "2_2") (pintype "passive"))
      (node (ref "C4C5") (pin "2") (pinfunction "2_2") (pintype "passive"))
      (node (ref "C4C6") (pin "2") (pinfunction "2_2") (pintype "passive"))
      (node (ref "C4C7") (pin "2") (pinfunction "2_2") (pintype "passive"))
      (node (ref "C4C8") (pin "2") (pinfunction "2_2") (pintype "passive"))
      (node (ref "C4C9") (pin "2") (pinfunction "2_2") (pintype "passive"))
      (node (ref "C4CA") (pin "2") (pinfunction "2_2") (pintype "passive"))
      (node (ref "C4CB") (pin "2") (pinfunction "2_2") (pintype "passive"))
      (node (ref "C4CC") (pin "2") (pinfunction "2_2") (pintype "passive"))
      (node (ref "C4CD") (pin "2") (pinfunction "2_2") (pintype "passive"))
      (node (ref "C4CE") (pin "2") (pinfunction "2_2") (pintype "passive"))
      (node (ref "C4CS") (pin "2") (pinfunction "2_2") (pintype "passive"))
      (node (ref "C4D0") (pin "2") (pinfunction "2_2") (pintype "passive"))
      (node (ref "C4D1") (pin "2") (pinfunction "2_2") (pintype "passive"))
      (node (ref "C4D2") (pin "2") (pinfunction "2_2") (pintype "passive"))
      (node (ref "C4D3") (pin "2") (pinfunction "2_2") (pintype "passive"))
      (node (ref "C4D4") (pin "2") (pinfunction "2_2") (pintype "passive"))
      (node (ref "C4D5") (pin "2") (pinfunction "2_2") (pintype "passive"))
      (node (ref "C4D6") (pin "2") (pinfunction "2_2") (pintype "passive"))
      (node (ref "C4D7") (pin "2") (pinfunction "2_2") (pintype "passive"))
      (node (ref "C4D8") (pin "2") (pinfunction "2_2") (pintype "passive"))
      (node (ref "C4D9") (pin "2") (pinfunction "2_2") (pintype "passive"))
      (node (ref "C4DA") (pin "2") (pinfunction "2_2") (pintype "passive"))
      (node (ref "C4DB") (pin "2") (pinfunction "2_2") (pintype "passive"))
      (node (ref "C4DC") (pin "2") (pinfunction "2_2") (pintype "passive"))
      (node (ref "C4DD") (pin "2") (pinfunction "2_2") (pintype "passive"))
      (node (ref "C4DE") (pin "2") (pinfunction "2_2") (pintype "passive"))
      (node (ref "C4DS") (pin "2") (pinfunction "2_2") (pintype "passive"))
      (node (ref "C4E0") (pin "2") (pinfunction "2_2") (pintype "passive"))
      (node (ref "C4E1") (pin "2") (pinfunction "2_2") (pintype "passive"))
      (node (ref "C4E2") (pin "2") (pinfunction "2_2") (pintype "passive"))
      (node (ref "C4E3") (pin "2") (pinfunction "2_2") (pintype "passive"))
      (node (ref "C4E4") (pin "2") (pinfunction "2_2") (pintype "passive"))
      (node (ref "C4E5") (pin "2") (pinfunction "2_2") (pintype "passive"))
      (node (ref "C4E6") (pin "2") (pinfunction "2_2") (pintype "passive"))
      (node (ref "C4E7") (pin "2") (pinfunction "2_2") (pintype "passive"))
      (node (ref "C4E8") (pin "2") (pinfunction "2_2") (pintype "passive"))
      (node (ref "C4E9") (pin "2") (pinfunction "2_2") (pintype "passive"))
      (node (ref "C4EA") (pin "2") (pinfunction "2_2") (pintype "passive"))
      (node (ref "C4EB") (pin "2") (pinfunction "2_2") (pintype "passive"))
      (node (ref "C4EC") (pin "2") (pinfunction "2_2") (pintype "passive"))
      (node (ref "C4ED") (pin "2") (pinfunction "2_2") (pintype "passive"))
      (node (ref "C4EE") (pin "2") (pinfunction "2_2") (pintype "passive"))
      (node (ref "C4ES") (pin "2") (pinfunction "2_2") (pintype "passive"))
      (node (ref "C4F0") (pin "2") (pinfunction "2_2") (pintype "passive"))
      (node (ref "C4F1") (pin "2") (pinfunction "2_2") (pintype "passive"))
      (node (ref "C4F2") (pin "2") (pinfunction "2_2") (pintype "passive"))
      (node (ref "C4F3") (pin "2") (pinfunction "2_2") (pintype "passive"))
      (node (ref "C4F4") (pin "2") (pinfunction "2_2") (pintype "passive"))
      (node (ref "C4F5") (pin "2") (pinfunction "2_2") (pintype "passive"))
      (node (ref "C4F6") (pin "2") (pinfunction "2_2") (pintype "passive"))
      (node (ref "C4F7") (pin "2") (pinfunction "2_2") (pintype "passive"))
      (node (ref "C4F8") (pin "2") (pinfunction "2_2") (pintype "passive"))
      (node (ref "C4F9") (pin "2") (pinfunction "2_2") (pintype "passive"))
      (node (ref "C4FA") (pin "2") (pinfunction "2_2") (pintype "passive"))
      (node (ref "C4FB") (pin "2") (pinfunction "2_2") (pintype "passive"))
      (node (ref "C4FC") (pin "2") (pinfunction "2_2") (pintype "passive"))
      (node (ref "C4FD") (pin "2") (pinfunction "2_2") (pintype "passive"))
      (node (ref "C4FE") (pin "2") (pinfunction "2_2") (pintype "passive"))
      (node (ref "C4FS") (pin "2") (pinfunction "2_2") (pintype "passive"))
      (node (ref "C4GS") (pin "2") (pinfunction "2_2") (pintype "passive"))
      (node (ref "C4HS") (pin "2") (pinfunction "2_2") (pintype "passive"))
      (node (ref "C4IS") (pin "2") (pinfunction "2_2") (pintype "passive"))
      (node (ref "C4JS") (pin "2") (pinfunction "2_2") (pintype "passive"))
      (node (ref "C4KS") (pin "2") (pinfunction "2_2") (pintype "passive"))
      (node (ref "C4LS") (pin "2") (pinfunction "2_2") (pintype "passive"))
      (node (ref "C4MS") (pin "2") (pinfunction "2_2") (pintype "passive"))
      (node (ref "C4NS") (pin "2") (pinfunction "2_2") (pintype "passive"))
      (node (ref "C4OS") (pin "2") (pinfunction "2_2") (pintype "passive"))
      (node (ref "C4PS") (pin "2") (pinfunction "2_2") (pintype "passive"))
      (node (ref "C4QS") (pin "2") (pinfunction "2_2") (pintype "passive"))
      (node (ref "C4RS") (pin "2") (pinfunction "2_2") (pintype "passive"))
      (node (ref "C4SS") (pin "2") (pinfunction "2_2") (pintype "passive"))
      (node (ref "C4TS") (pin "2") (pinfunction "2_2") (pintype "passive"))
      (node (ref "C4US") (pin "2") (pinfunction "2_2") (pintype "passive"))
      (node (ref "C4VS") (pin "2") (pinfunction "2_2") (pintype "passive"))
      (node (ref "J01") (pin "A5") (pinfunction "5_A5") (pintype "passive"))
      (node (ref "J01") (pin "B1") (pinfunction "11_B1") (pintype "passive"))
      (node (ref "J01") (pin "B2") (pinfunction "12_B2") (pintype "passive"))
      (node (ref "J01") (pin "B3") (pinfunction "13_B3") (pintype "passive"))
      (node (ref "J01") (pin "B4") (pinfunction "14_B4") (pintype "passive"))
      (node (ref "R01M") (pin "2") (pinfunction "2_2") (pintype "passive"))
      (node (ref "R01S") (pin "2") (pinfunction "2_2") (pintype "passive"))
      (node (ref "R01T") (pin "2") (pinfunction "2_2") (pintype "passive"))
      (node (ref "R01T1") (pin "2") (pinfunction "2_2") (pintype "passive"))
      (node (ref "R02E") (pin "2") (pinfunction "2_2") (pintype "passive"))
      (node (ref "R02F") (pin "2") (pinfunction "2_2") (pintype "passive"))
      (node (ref "U01") (pin "HS") (pinfunction "PP.GND_HS") (pintype "passive"))
      (node (ref "U01") (pin "V1") (pinfunction "PP.GND_V1") (pintype "passive"))
      (node (ref "U01") (pin "V10") (pinfunction "PP.GND_V10") (pintype "passive"))
      (node (ref "U01") (pin "V11") (pinfunction "PP.GND_V11") (pintype "passive"))
      (node (ref "U01") (pin "V13") (pinfunction "PP.GND_V13") (pintype "passive"))
      (node (ref "U01") (pin "V15") (pinfunction "PP.GND_V15") (pintype "passive"))
      (node (ref "U01") (pin "V16") (pinfunction "PP.GND_V16") (pintype "passive"))
      (node (ref "U01") (pin "V17") (pinfunction "PP.GND_V17") (pintype "passive"))
      (node (ref "U01") (pin "V18") (pinfunction "PP.GND_V18") (pintype "passive"))
      (node (ref "U01") (pin "V19") (pinfunction "PP.GND_V19") (pintype "passive"))
      (node (ref "U01") (pin "V2") (pinfunction "PP.GND_V2") (pintype "passive"))
      (node (ref "U01") (pin "V20") (pinfunction "PP.GND_V20") (pintype "passive"))
      (node (ref "U01") (pin "V23") (pinfunction "PP.GND_V23") (pintype "passive"))
      (node (ref "U01") (pin "V24") (pinfunction "PP.GND_V24") (pintype "passive"))
      (node (ref "U01") (pin "V25") (pinfunction "PP.GND_V25") (pintype "passive"))
      (node (ref "U01") (pin "V26") (pinfunction "PP.GND_V26") (pintype "passive"))
      (node (ref "U01") (pin "V27") (pinfunction "PP.GND_V27") (pintype "passive"))
      (node (ref "U01") (pin "V4") (pinfunction "PP.GND_V4") (pintype "passive"))
      (node (ref "U01") (pin "V6") (pinfunction "PP.GND_V6") (pintype "passive"))
      (node (ref "U01") (pin "V7") (pinfunction "PP.GND_V7") (pintype "passive"))
      (node (ref "U01") (pin "V8") (pinfunction "PP.GND_V8") (pintype "passive"))
      (node (ref "U01") (pin "V9") (pinfunction "PP.GND_V9") (pintype "passive"))
      (node (ref "U40") (pin "1") (pinfunction "1.QCM_1") (pintype "passive"))
      (node (ref "U40") (pin "2") (pinfunction "2.CMPLUS_2") (pintype "passive"))
      (node (ref "U40") (pin "3") (pinfunction "3.CMMINUS_3") (pintype "passive"))
      (node (ref "U40") (pin "EP") (pinfunction "EP.VSS_EP_EP") (pintype "passive"))
      (node (ref "U40") (pin "V1") (pinfunction "EP.VSS_EP_V1") (pintype "passive"))
      (node (ref "U40") (pin "V10") (pinfunction "EP.VSS_EP_V10") (pintype "passive"))
      (node (ref "U40") (pin "V11") (pinfunction "EP.VSS_EP_V11") (pintype "passive"))
      (node (ref "U40") (pin "V12") (pinfunction "EP.VSS_EP_V12") (pintype "passive"))
      (node (ref "U40") (pin "V13") (pinfunction "EP.VSS_EP_V13") (pintype "passive"))
      (node (ref "U40") (pin "V14") (pinfunction "EP.VSS_EP_V14") (pintype "passive"))
      (node (ref "U40") (pin "V15") (pinfunction "EP.VSS_EP_V15") (pintype "passive"))
      (node (ref "U40") (pin "V16") (pinfunction "EP.VSS_EP_V16") (pintype "passive"))
      (node (ref "U40") (pin "V17") (pinfunction "EP.VSS_EP_V17") (pintype "passive"))
      (node (ref "U40") (pin "V18") (pinfunction "EP.VSS_EP_V18") (pintype "passive"))
      (node (ref "U40") (pin "V19") (pinfunction "EP.VSS_EP_V19") (pintype "passive"))
      (node (ref "U40") (pin "V2") (pinfunction "EP.VSS_EP_V2") (pintype "passive"))
      (node (ref "U40") (pin "V20") (pinfunction "EP.VSS_EP_V20") (pintype "passive"))
      (node (ref "U40") (pin "V21") (pinfunction "EP.VSS_EP_V21") (pintype "passive"))
      (node (ref "U40") (pin "V22") (pinfunction "EP.VSS_EP_V22") (pintype "passive"))
      (node (ref "U40") (pin "V23") (pinfunction "EP.VSS_EP_V23") (pintype "passive"))
      (node (ref "U40") (pin "V24") (pinfunction "EP.VSS_EP_V24") (pintype "passive"))
      (node (ref "U40") (pin "V25") (pinfunction "EP.VSS_EP_V25") (pintype "passive"))
      (node (ref "U40") (pin "V3") (pinfunction "EP.VSS_EP_V3") (pintype "passive"))
      (node (ref "U40") (pin "V4") (pinfunction "EP.VSS_EP_V4") (pintype "passive"))
      (node (ref "U40") (pin "V5") (pinfunction "EP.VSS_EP_V5") (pintype "passive"))
      (node (ref "U40") (pin "V6") (pinfunction "EP.VSS_EP_V6") (pintype "passive"))
      (node (ref "U40") (pin "V7") (pinfunction "EP.VSS_EP_V7") (pintype "passive"))
      (node (ref "U40") (pin "V8") (pinfunction "EP.VSS_EP_V8") (pintype "passive"))
      (node (ref "U40") (pin "V9") (pinfunction "EP.VSS_EP_V9") (pintype "passive"))
      (node (ref "U41") (pin "1") (pinfunction "1.QCM_1") (pintype "passive"))
      (node (ref "U41") (pin "2") (pinfunction "2.CMPLUS_2") (pintype "passive"))
      (node (ref "U41") (pin "3") (pinfunction "3.CMMINUS_3") (pintype "passive"))
      (node (ref "U41") (pin "EP") (pinfunction "EP.VSS_EP_EP") (pintype "passive"))
      (node (ref "U41") (pin "V1") (pinfunction "EP.VSS_EP_V1") (pintype "passive"))
      (node (ref "U41") (pin "V10") (pinfunction "EP.VSS_EP_V10") (pintype "passive"))
      (node (ref "U41") (pin "V11") (pinfunction "EP.VSS_EP_V11") (pintype "passive"))
      (node (ref "U41") (pin "V12") (pinfunction "EP.VSS_EP_V12") (pintype "passive"))
      (node (ref "U41") (pin "V13") (pinfunction "EP.VSS_EP_V13") (pintype "passive"))
      (node (ref "U41") (pin "V14") (pinfunction "EP.VSS_EP_V14") (pintype "passive"))
      (node (ref "U41") (pin "V15") (pinfunction "EP.VSS_EP_V15") (pintype "passive"))
      (node (ref "U41") (pin "V16") (pinfunction "EP.VSS_EP_V16") (pintype "passive"))
      (node (ref "U41") (pin "V17") (pinfunction "EP.VSS_EP_V17") (pintype "passive"))
      (node (ref "U41") (pin "V18") (pinfunction "EP.VSS_EP_V18") (pintype "passive"))
      (node (ref "U41") (pin "V19") (pinfunction "EP.VSS_EP_V19") (pintype "passive"))
      (node (ref "U41") (pin "V2") (pinfunction "EP.VSS_EP_V2") (pintype "passive"))
      (node (ref "U41") (pin "V20") (pinfunction "EP.VSS_EP_V20") (pintype "passive"))
      (node (ref "U41") (pin "V21") (pinfunction "EP.VSS_EP_V21") (pintype "passive"))
      (node (ref "U41") (pin "V22") (pinfunction "EP.VSS_EP_V22") (pintype "passive"))
      (node (ref "U41") (pin "V23") (pinfunction "EP.VSS_EP_V23") (pintype "passive"))
      (node (ref "U41") (pin "V24") (pinfunction "EP.VSS_EP_V24") (pintype "passive"))
      (node (ref "U41") (pin "V25") (pinfunction "EP.VSS_EP_V25") (pintype "passive"))
      (node (ref "U41") (pin "V3") (pinfunction "EP.VSS_EP_V3") (pintype "passive"))
      (node (ref "U41") (pin "V4") (pinfunction "EP.VSS_EP_V4") (pintype "passive"))
      (node (ref "U41") (pin "V5") (pinfunction "EP.VSS_EP_V5") (pintype "passive"))
      (node (ref "U41") (pin "V6") (pinfunction "EP.VSS_EP_V6") (pintype "passive"))
      (node (ref "U41") (pin "V7") (pinfunction "EP.VSS_EP_V7") (pintype "passive"))
      (node (ref "U41") (pin "V8") (pinfunction "EP.VSS_EP_V8") (pintype "passive"))
      (node (ref "U41") (pin "V9") (pinfunction "EP.VSS_EP_V9") (pintype "passive"))
      (node (ref "U42") (pin "1") (pinfunction "1.QCM_1") (pintype "passive"))
      (node (ref "U42") (pin "2") (pinfunction "2.CMPLUS_2") (pintype "passive"))
      (node (ref "U42") (pin "3") (pinfunction "3.CMMINUS_3") (pintype "passive"))
      (node (ref "U42") (pin "EP") (pinfunction "EP.VSS_EP_EP") (pintype "passive"))
      (node (ref "U42") (pin "V1") (pinfunction "EP.VSS_EP_V1") (pintype "passive"))
      (node (ref "U42") (pin "V10") (pinfunction "EP.VSS_EP_V10") (pintype "passive"))
      (node (ref "U42") (pin "V11") (pinfunction "EP.VSS_EP_V11") (pintype "passive"))
      (node (ref "U42") (pin "V12") (pinfunction "EP.VSS_EP_V12") (pintype "passive"))
      (node (ref "U42") (pin "V13") (pinfunction "EP.VSS_EP_V13") (pintype "passive"))
      (node (ref "U42") (pin "V14") (pinfunction "EP.VSS_EP_V14") (pintype "passive"))
      (node (ref "U42") (pin "V15") (pinfunction "EP.VSS_EP_V15") (pintype "passive"))
      (node (ref "U42") (pin "V16") (pinfunction "EP.VSS_EP_V16") (pintype "passive"))
      (node (ref "U42") (pin "V17") (pinfunction "EP.VSS_EP_V17") (pintype "passive"))
      (node (ref "U42") (pin "V18") (pinfunction "EP.VSS_EP_V18") (pintype "passive"))
      (node (ref "U42") (pin "V19") (pinfunction "EP.VSS_EP_V19") (pintype "passive"))
      (node (ref "U42") (pin "V2") (pinfunction "EP.VSS_EP_V2") (pintype "passive"))
      (node (ref "U42") (pin "V20") (pinfunction "EP.VSS_EP_V20") (pintype "passive"))
      (node (ref "U42") (pin "V21") (pinfunction "EP.VSS_EP_V21") (pintype "passive"))
      (node (ref "U42") (pin "V22") (pinfunction "EP.VSS_EP_V22") (pintype "passive"))
      (node (ref "U42") (pin "V23") (pinfunction "EP.VSS_EP_V23") (pintype "passive"))
      (node (ref "U42") (pin "V24") (pinfunction "EP.VSS_EP_V24") (pintype "passive"))
      (node (ref "U42") (pin "V25") (pinfunction "EP.VSS_EP_V25") (pintype "passive"))
      (node (ref "U42") (pin "V3") (pinfunction "EP.VSS_EP_V3") (pintype "passive"))
      (node (ref "U42") (pin "V4") (pinfunction "EP.VSS_EP_V4") (pintype "passive"))
      (node (ref "U42") (pin "V5") (pinfunction "EP.VSS_EP_V5") (pintype "passive"))
      (node (ref "U42") (pin "V6") (pinfunction "EP.VSS_EP_V6") (pintype "passive"))
      (node (ref "U42") (pin "V7") (pinfunction "EP.VSS_EP_V7") (pintype "passive"))
      (node (ref "U42") (pin "V8") (pinfunction "EP.VSS_EP_V8") (pintype "passive"))
      (node (ref "U42") (pin "V9") (pinfunction "EP.VSS_EP_V9") (pintype "passive"))
      (node (ref "U43") (pin "1") (pinfunction "1.QCM_1") (pintype "passive"))
      (node (ref "U43") (pin "2") (pinfunction "2.CMPLUS_2") (pintype "passive"))
      (node (ref "U43") (pin "3") (pinfunction "3.CMMINUS_3") (pintype "passive"))
      (node (ref "U43") (pin "EP") (pinfunction "EP.VSS_EP_EP") (pintype "passive"))
      (node (ref "U43") (pin "V1") (pinfunction "EP.VSS_EP_V1") (pintype "passive"))
      (node (ref "U43") (pin "V10") (pinfunction "EP.VSS_EP_V10") (pintype "passive"))
      (node (ref "U43") (pin "V11") (pinfunction "EP.VSS_EP_V11") (pintype "passive"))
      (node (ref "U43") (pin "V12") (pinfunction "EP.VSS_EP_V12") (pintype "passive"))
      (node (ref "U43") (pin "V13") (pinfunction "EP.VSS_EP_V13") (pintype "passive"))
      (node (ref "U43") (pin "V14") (pinfunction "EP.VSS_EP_V14") (pintype "passive"))
      (node (ref "U43") (pin "V15") (pinfunction "EP.VSS_EP_V15") (pintype "passive"))
      (node (ref "U43") (pin "V16") (pinfunction "EP.VSS_EP_V16") (pintype "passive"))
      (node (ref "U43") (pin "V17") (pinfunction "EP.VSS_EP_V17") (pintype "passive"))
      (node (ref "U43") (pin "V18") (pinfunction "EP.VSS_EP_V18") (pintype "passive"))
      (node (ref "U43") (pin "V19") (pinfunction "EP.VSS_EP_V19") (pintype "passive"))
      (node (ref "U43") (pin "V2") (pinfunction "EP.VSS_EP_V2") (pintype "passive"))
      (node (ref "U43") (pin "V20") (pinfunction "EP.VSS_EP_V20") (pintype "passive"))
      (node (ref "U43") (pin "V21") (pinfunction "EP.VSS_EP_V21") (pintype "passive"))
      (node (ref "U43") (pin "V22") (pinfunction "EP.VSS_EP_V22") (pintype "passive"))
      (node (ref "U43") (pin "V23") (pinfunction "EP.VSS_EP_V23") (pintype "passive"))
      (node (ref "U43") (pin "V24") (pinfunction "EP.VSS_EP_V24") (pintype "passive"))
      (node (ref "U43") (pin "V25") (pinfunction "EP.VSS_EP_V25") (pintype "passive"))
      (node (ref "U43") (pin "V3") (pinfunction "EP.VSS_EP_V3") (pintype "passive"))
      (node (ref "U43") (pin "V4") (pinfunction "EP.VSS_EP_V4") (pintype "passive"))
      (node (ref "U43") (pin "V5") (pinfunction "EP.VSS_EP_V5") (pintype "passive"))
      (node (ref "U43") (pin "V6") (pinfunction "EP.VSS_EP_V6") (pintype "passive"))
      (node (ref "U43") (pin "V7") (pinfunction "EP.VSS_EP_V7") (pintype "passive"))
      (node (ref "U43") (pin "V8") (pinfunction "EP.VSS_EP_V8") (pintype "passive"))
      (node (ref "U43") (pin "V9") (pinfunction "EP.VSS_EP_V9") (pintype "passive"))
      (node (ref "U44") (pin "1") (pinfunction "1.QCM_1") (pintype "passive"))
      (node (ref "U44") (pin "2") (pinfunction "2.CMPLUS_2") (pintype "passive"))
      (node (ref "U44") (pin "3") (pinfunction "3.CMMINUS_3") (pintype "passive"))
      (node (ref "U44") (pin "EP") (pinfunction "EP.VSS_EP_EP") (pintype "passive"))
      (node (ref "U44") (pin "V1") (pinfunction "EP.VSS_EP_V1") (pintype "passive"))
      (node (ref "U44") (pin "V10") (pinfunction "EP.VSS_EP_V10") (pintype "passive"))
      (node (ref "U44") (pin "V11") (pinfunction "EP.VSS_EP_V11") (pintype "passive"))
      (node (ref "U44") (pin "V12") (pinfunction "EP.VSS_EP_V12") (pintype "passive"))
      (node (ref "U44") (pin "V13") (pinfunction "EP.VSS_EP_V13") (pintype "passive"))
      (node (ref "U44") (pin "V14") (pinfunction "EP.VSS_EP_V14") (pintype "passive"))
      (node (ref "U44") (pin "V15") (pinfunction "EP.VSS_EP_V15") (pintype "passive"))
      (node (ref "U44") (pin "V16") (pinfunction "EP.VSS_EP_V16") (pintype "passive"))
      (node (ref "U44") (pin "V17") (pinfunction "EP.VSS_EP_V17") (pintype "passive"))
      (node (ref "U44") (pin "V18") (pinfunction "EP.VSS_EP_V18") (pintype "passive"))
      (node (ref "U44") (pin "V19") (pinfunction "EP.VSS_EP_V19") (pintype "passive"))
      (node (ref "U44") (pin "V2") (pinfunction "EP.VSS_EP_V2") (pintype "passive"))
      (node (ref "U44") (pin "V20") (pinfunction "EP.VSS_EP_V20") (pintype "passive"))
      (node (ref "U44") (pin "V21") (pinfunction "EP.VSS_EP_V21") (pintype "passive"))
      (node (ref "U44") (pin "V22") (pinfunction "EP.VSS_EP_V22") (pintype "passive"))
      (node (ref "U44") (pin "V23") (pinfunction "EP.VSS_EP_V23") (pintype "passive"))
      (node (ref "U44") (pin "V24") (pinfunction "EP.VSS_EP_V24") (pintype "passive"))
      (node (ref "U44") (pin "V25") (pinfunction "EP.VSS_EP_V25") (pintype "passive"))
      (node (ref "U44") (pin "V3") (pinfunction "EP.VSS_EP_V3") (pintype "passive"))
      (node (ref "U44") (pin "V4") (pinfunction "EP.VSS_EP_V4") (pintype "passive"))
      (node (ref "U44") (pin "V5") (pinfunction "EP.VSS_EP_V5") (pintype "passive"))
      (node (ref "U44") (pin "V6") (pinfunction "EP.VSS_EP_V6") (pintype "passive"))
      (node (ref "U44") (pin "V7") (pinfunction "EP.VSS_EP_V7") (pintype "passive"))
      (node (ref "U44") (pin "V8") (pinfunction "EP.VSS_EP_V8") (pintype "passive"))
      (node (ref "U44") (pin "V9") (pinfunction "EP.VSS_EP_V9") (pintype "passive"))
      (node (ref "U45") (pin "1") (pinfunction "1.QCM_1") (pintype "passive"))
      (node (ref "U45") (pin "2") (pinfunction "2.CMPLUS_2") (pintype "passive"))
      (node (ref "U45") (pin "3") (pinfunction "3.CMMINUS_3") (pintype "passive"))
      (node (ref "U45") (pin "EP") (pinfunction "EP.VSS_EP_EP") (pintype "passive"))
      (node (ref "U45") (pin "V1") (pinfunction "EP.VSS_EP_V1") (pintype "passive"))
      (node (ref "U45") (pin "V10") (pinfunction "EP.VSS_EP_V10") (pintype "passive"))
      (node (ref "U45") (pin "V11") (pinfunction "EP.VSS_EP_V11") (pintype "passive"))
      (node (ref "U45") (pin "V12") (pinfunction "EP.VSS_EP_V12") (pintype "passive"))
      (node (ref "U45") (pin "V13") (pinfunction "EP.VSS_EP_V13") (pintype "passive"))
      (node (ref "U45") (pin "V14") (pinfunction "EP.VSS_EP_V14") (pintype "passive"))
      (node (ref "U45") (pin "V15") (pinfunction "EP.VSS_EP_V15") (pintype "passive"))
      (node (ref "U45") (pin "V16") (pinfunction "EP.VSS_EP_V16") (pintype "passive"))
      (node (ref "U45") (pin "V17") (pinfunction "EP.VSS_EP_V17") (pintype "passive"))
      (node (ref "U45") (pin "V18") (pinfunction "EP.VSS_EP_V18") (pintype "passive"))
      (node (ref "U45") (pin "V19") (pinfunction "EP.VSS_EP_V19") (pintype "passive"))
      (node (ref "U45") (pin "V2") (pinfunction "EP.VSS_EP_V2") (pintype "passive"))
      (node (ref "U45") (pin "V20") (pinfunction "EP.VSS_EP_V20") (pintype "passive"))
      (node (ref "U45") (pin "V21") (pinfunction "EP.VSS_EP_V21") (pintype "passive"))
      (node (ref "U45") (pin "V22") (pinfunction "EP.VSS_EP_V22") (pintype "passive"))
      (node (ref "U45") (pin "V23") (pinfunction "EP.VSS_EP_V23") (pintype "passive"))
      (node (ref "U45") (pin "V24") (pinfunction "EP.VSS_EP_V24") (pintype "passive"))
      (node (ref "U45") (pin "V25") (pinfunction "EP.VSS_EP_V25") (pintype "passive"))
      (node (ref "U45") (pin "V3") (pinfunction "EP.VSS_EP_V3") (pintype "passive"))
      (node (ref "U45") (pin "V4") (pinfunction "EP.VSS_EP_V4") (pintype "passive"))
      (node (ref "U45") (pin "V5") (pinfunction "EP.VSS_EP_V5") (pintype "passive"))
      (node (ref "U45") (pin "V6") (pinfunction "EP.VSS_EP_V6") (pintype "passive"))
      (node (ref "U45") (pin "V7") (pinfunction "EP.VSS_EP_V7") (pintype "passive"))
      (node (ref "U45") (pin "V8") (pinfunction "EP.VSS_EP_V8") (pintype "passive"))
      (node (ref "U45") (pin "V9") (pinfunction "EP.VSS_EP_V9") (pintype "passive"))
      (node (ref "U46") (pin "1") (pinfunction "1.QCM_1") (pintype "passive"))
      (node (ref "U46") (pin "2") (pinfunction "2.CMPLUS_2") (pintype "passive"))
      (node (ref "U46") (pin "3") (pinfunction "3.CMMINUS_3") (pintype "passive"))
      (node (ref "U46") (pin "EP") (pinfunction "EP.VSS_EP_EP") (pintype "passive"))
      (node (ref "U46") (pin "V1") (pinfunction "EP.VSS_EP_V1") (pintype "passive"))
      (node (ref "U46") (pin "V10") (pinfunction "EP.VSS_EP_V10") (pintype "passive"))
      (node (ref "U46") (pin "V11") (pinfunction "EP.VSS_EP_V11") (pintype "passive"))
      (node (ref "U46") (pin "V12") (pinfunction "EP.VSS_EP_V12") (pintype "passive"))
      (node (ref "U46") (pin "V13") (pinfunction "EP.VSS_EP_V13") (pintype "passive"))
      (node (ref "U46") (pin "V14") (pinfunction "EP.VSS_EP_V14") (pintype "passive"))
      (node (ref "U46") (pin "V15") (pinfunction "EP.VSS_EP_V15") (pintype "passive"))
      (node (ref "U46") (pin "V16") (pinfunction "EP.VSS_EP_V16") (pintype "passive"))
      (node (ref "U46") (pin "V17") (pinfunction "EP.VSS_EP_V17") (pintype "passive"))
      (node (ref "U46") (pin "V18") (pinfunction "EP.VSS_EP_V18") (pintype "passive"))
      (node (ref "U46") (pin "V19") (pinfunction "EP.VSS_EP_V19") (pintype "passive"))
      (node (ref "U46") (pin "V2") (pinfunction "EP.VSS_EP_V2") (pintype "passive"))
      (node (ref "U46") (pin "V20") (pinfunction "EP.VSS_EP_V20") (pintype "passive"))
      (node (ref "U46") (pin "V21") (pinfunction "EP.VSS_EP_V21") (pintype "passive"))
      (node (ref "U46") (pin "V22") (pinfunction "EP.VSS_EP_V22") (pintype "passive"))
      (node (ref "U46") (pin "V23") (pinfunction "EP.VSS_EP_V23") (pintype "passive"))
      (node (ref "U46") (pin "V24") (pinfunction "EP.VSS_EP_V24") (pintype "passive"))
      (node (ref "U46") (pin "V25") (pinfunction "EP.VSS_EP_V25") (pintype "passive"))
      (node (ref "U46") (pin "V3") (pinfunction "EP.VSS_EP_V3") (pintype "passive"))
      (node (ref "U46") (pin "V4") (pinfunction "EP.VSS_EP_V4") (pintype "passive"))
      (node (ref "U46") (pin "V5") (pinfunction "EP.VSS_EP_V5") (pintype "passive"))
      (node (ref "U46") (pin "V6") (pinfunction "EP.VSS_EP_V6") (pintype "passive"))
      (node (ref "U46") (pin "V7") (pinfunction "EP.VSS_EP_V7") (pintype "passive"))
      (node (ref "U46") (pin "V8") (pinfunction "EP.VSS_EP_V8") (pintype "passive"))
      (node (ref "U46") (pin "V9") (pinfunction "EP.VSS_EP_V9") (pintype "passive"))
      (node (ref "U47") (pin "1") (pinfunction "1.QCM_1") (pintype "passive"))
      (node (ref "U47") (pin "2") (pinfunction "2.CMPLUS_2") (pintype "passive"))
      (node (ref "U47") (pin "3") (pinfunction "3.CMMINUS_3") (pintype "passive"))
      (node (ref "U47") (pin "EP") (pinfunction "EP.VSS_EP_EP") (pintype "passive"))
      (node (ref "U47") (pin "V1") (pinfunction "EP.VSS_EP_V1") (pintype "passive"))
      (node (ref "U47") (pin "V10") (pinfunction "EP.VSS_EP_V10") (pintype "passive"))
      (node (ref "U47") (pin "V11") (pinfunction "EP.VSS_EP_V11") (pintype "passive"))
      (node (ref "U47") (pin "V12") (pinfunction "EP.VSS_EP_V12") (pintype "passive"))
      (node (ref "U47") (pin "V13") (pinfunction "EP.VSS_EP_V13") (pintype "passive"))
      (node (ref "U47") (pin "V14") (pinfunction "EP.VSS_EP_V14") (pintype "passive"))
      (node (ref "U47") (pin "V15") (pinfunction "EP.VSS_EP_V15") (pintype "passive"))
      (node (ref "U47") (pin "V16") (pinfunction "EP.VSS_EP_V16") (pintype "passive"))
      (node (ref "U47") (pin "V17") (pinfunction "EP.VSS_EP_V17") (pintype "passive"))
      (node (ref "U47") (pin "V18") (pinfunction "EP.VSS_EP_V18") (pintype "passive"))
      (node (ref "U47") (pin "V19") (pinfunction "EP.VSS_EP_V19") (pintype "passive"))
      (node (ref "U47") (pin "V2") (pinfunction "EP.VSS_EP_V2") (pintype "passive"))
      (node (ref "U47") (pin "V20") (pinfunction "EP.VSS_EP_V20") (pintype "passive"))
      (node (ref "U47") (pin "V21") (pinfunction "EP.VSS_EP_V21") (pintype "passive"))
      (node (ref "U47") (pin "V22") (pinfunction "EP.VSS_EP_V22") (pintype "passive"))
      (node (ref "U47") (pin "V23") (pinfunction "EP.VSS_EP_V23") (pintype "passive"))
      (node (ref "U47") (pin "V24") (pinfunction "EP.VSS_EP_V24") (pintype "passive"))
      (node (ref "U47") (pin "V25") (pinfunction "EP.VSS_EP_V25") (pintype "passive"))
      (node (ref "U47") (pin "V3") (pinfunction "EP.VSS_EP_V3") (pintype "passive"))
      (node (ref "U47") (pin "V4") (pinfunction "EP.VSS_EP_V4") (pintype "passive"))
      (node (ref "U47") (pin "V5") (pinfunction "EP.VSS_EP_V5") (pintype "passive"))
      (node (ref "U47") (pin "V6") (pinfunction "EP.VSS_EP_V6") (pintype "passive"))
      (node (ref "U47") (pin "V7") (pinfunction "EP.VSS_EP_V7") (pintype "passive"))
      (node (ref "U47") (pin "V8") (pinfunction "EP.VSS_EP_V8") (pintype "passive"))
      (node (ref "U47") (pin "V9") (pinfunction "EP.VSS_EP_V9") (pintype "passive"))
      (node (ref "U48") (pin "1") (pinfunction "1.QCM_1") (pintype "passive"))
      (node (ref "U48") (pin "2") (pinfunction "2.CMPLUS_2") (pintype "passive"))
      (node (ref "U48") (pin "3") (pinfunction "3.CMMINUS_3") (pintype "passive"))
      (node (ref "U48") (pin "EP") (pinfunction "EP.VSS_EP_EP") (pintype "passive"))
      (node (ref "U48") (pin "V1") (pinfunction "EP.VSS_EP_V1") (pintype "passive"))
      (node (ref "U48") (pin "V10") (pinfunction "EP.VSS_EP_V10") (pintype "passive"))
      (node (ref "U48") (pin "V11") (pinfunction "EP.VSS_EP_V11") (pintype "passive"))
      (node (ref "U48") (pin "V12") (pinfunction "EP.VSS_EP_V12") (pintype "passive"))
      (node (ref "U48") (pin "V13") (pinfunction "EP.VSS_EP_V13") (pintype "passive"))
      (node (ref "U48") (pin "V14") (pinfunction "EP.VSS_EP_V14") (pintype "passive"))
      (node (ref "U48") (pin "V15") (pinfunction "EP.VSS_EP_V15") (pintype "passive"))
      (node (ref "U48") (pin "V16") (pinfunction "EP.VSS_EP_V16") (pintype "passive"))
      (node (ref "U48") (pin "V17") (pinfunction "EP.VSS_EP_V17") (pintype "passive"))
      (node (ref "U48") (pin "V18") (pinfunction "EP.VSS_EP_V18") (pintype "passive"))
      (node (ref "U48") (pin "V19") (pinfunction "EP.VSS_EP_V19") (pintype "passive"))
      (node (ref "U48") (pin "V2") (pinfunction "EP.VSS_EP_V2") (pintype "passive"))
      (node (ref "U48") (pin "V20") (pinfunction "EP.VSS_EP_V20") (pintype "passive"))
      (node (ref "U48") (pin "V21") (pinfunction "EP.VSS_EP_V21") (pintype "passive"))
      (node (ref "U48") (pin "V22") (pinfunction "EP.VSS_EP_V22") (pintype "passive"))
      (node (ref "U48") (pin "V23") (pinfunction "EP.VSS_EP_V23") (pintype "passive"))
      (node (ref "U48") (pin "V24") (pinfunction "EP.VSS_EP_V24") (pintype "passive"))
      (node (ref "U48") (pin "V25") (pinfunction "EP.VSS_EP_V25") (pintype "passive"))
      (node (ref "U48") (pin "V3") (pinfunction "EP.VSS_EP_V3") (pintype "passive"))
      (node (ref "U48") (pin "V4") (pinfunction "EP.VSS_EP_V4") (pintype "passive"))
      (node (ref "U48") (pin "V5") (pinfunction "EP.VSS_EP_V5") (pintype "passive"))
      (node (ref "U48") (pin "V6") (pinfunction "EP.VSS_EP_V6") (pintype "passive"))
      (node (ref "U48") (pin "V7") (pinfunction "EP.VSS_EP_V7") (pintype "passive"))
      (node (ref "U48") (pin "V8") (pinfunction "EP.VSS_EP_V8") (pintype "passive"))
      (node (ref "U48") (pin "V9") (pinfunction "EP.VSS_EP_V9") (pintype "passive"))
      (node (ref "U49") (pin "1") (pinfunction "1.QCM_1") (pintype "passive"))
      (node (ref "U49") (pin "2") (pinfunction "2.CMPLUS_2") (pintype "passive"))
      (node (ref "U49") (pin "3") (pinfunction "3.CMMINUS_3") (pintype "passive"))
      (node (ref "U49") (pin "EP") (pinfunction "EP.VSS_EP_EP") (pintype "passive"))
      (node (ref "U49") (pin "V1") (pinfunction "EP.VSS_EP_V1") (pintype "passive"))
      (node (ref "U49") (pin "V10") (pinfunction "EP.VSS_EP_V10") (pintype "passive"))
      (node (ref "U49") (pin "V11") (pinfunction "EP.VSS_EP_V11") (pintype "passive"))
      (node (ref "U49") (pin "V12") (pinfunction "EP.VSS_EP_V12") (pintype "passive"))
      (node (ref "U49") (pin "V13") (pinfunction "EP.VSS_EP_V13") (pintype "passive"))
      (node (ref "U49") (pin "V14") (pinfunction "EP.VSS_EP_V14") (pintype "passive"))
      (node (ref "U49") (pin "V15") (pinfunction "EP.VSS_EP_V15") (pintype "passive"))
      (node (ref "U49") (pin "V16") (pinfunction "EP.VSS_EP_V16") (pintype "passive"))
      (node (ref "U49") (pin "V17") (pinfunction "EP.VSS_EP_V17") (pintype "passive"))
      (node (ref "U49") (pin "V18") (pinfunction "EP.VSS_EP_V18") (pintype "passive"))
      (node (ref "U49") (pin "V19") (pinfunction "EP.VSS_EP_V19") (pintype "passive"))
      (node (ref "U49") (pin "V2") (pinfunction "EP.VSS_EP_V2") (pintype "passive"))
      (node (ref "U49") (pin "V20") (pinfunction "EP.VSS_EP_V20") (pintype "passive"))
      (node (ref "U49") (pin "V21") (pinfunction "EP.VSS_EP_V21") (pintype "passive"))
      (node (ref "U49") (pin "V22") (pinfunction "EP.VSS_EP_V22") (pintype "passive"))
      (node (ref "U49") (pin "V23") (pinfunction "EP.VSS_EP_V23") (pintype "passive"))
      (node (ref "U49") (pin "V24") (pinfunction "EP.VSS_EP_V24") (pintype "passive"))
      (node (ref "U49") (pin "V25") (pinfunction "EP.VSS_EP_V25") (pintype "passive"))
      (node (ref "U49") (pin "V3") (pinfunction "EP.VSS_EP_V3") (pintype "passive"))
      (node (ref "U49") (pin "V4") (pinfunction "EP.VSS_EP_V4") (pintype "passive"))
      (node (ref "U49") (pin "V5") (pinfunction "EP.VSS_EP_V5") (pintype "passive"))
      (node (ref "U49") (pin "V6") (pinfunction "EP.VSS_EP_V6") (pintype "passive"))
      (node (ref "U49") (pin "V7") (pinfunction "EP.VSS_EP_V7") (pintype "passive"))
      (node (ref "U49") (pin "V8") (pinfunction "EP.VSS_EP_V8") (pintype "passive"))
      (node (ref "U49") (pin "V9") (pinfunction "EP.VSS_EP_V9") (pintype "passive"))
      (node (ref "U4A") (pin "1") (pinfunction "1.QCM_1") (pintype "passive"))
      (node (ref "U4A") (pin "2") (pinfunction "2.CMPLUS_2") (pintype "passive"))
      (node (ref "U4A") (pin "3") (pinfunction "3.CMMINUS_3") (pintype "passive"))
      (node (ref "U4A") (pin "EP") (pinfunction "EP.VSS_EP_EP") (pintype "passive"))
      (node (ref "U4A") (pin "V1") (pinfunction "EP.VSS_EP_V1") (pintype "passive"))
      (node (ref "U4A") (pin "V10") (pinfunction "EP.VSS_EP_V10") (pintype "passive"))
      (node (ref "U4A") (pin "V11") (pinfunction "EP.VSS_EP_V11") (pintype "passive"))
      (node (ref "U4A") (pin "V12") (pinfunction "EP.VSS_EP_V12") (pintype "passive"))
      (node (ref "U4A") (pin "V13") (pinfunction "EP.VSS_EP_V13") (pintype "passive"))
      (node (ref "U4A") (pin "V14") (pinfunction "EP.VSS_EP_V14") (pintype "passive"))
      (node (ref "U4A") (pin "V15") (pinfunction "EP.VSS_EP_V15") (pintype "passive"))
      (node (ref "U4A") (pin "V16") (pinfunction "EP.VSS_EP_V16") (pintype "passive"))
      (node (ref "U4A") (pin "V17") (pinfunction "EP.VSS_EP_V17") (pintype "passive"))
      (node (ref "U4A") (pin "V18") (pinfunction "EP.VSS_EP_V18") (pintype "passive"))
      (node (ref "U4A") (pin "V19") (pinfunction "EP.VSS_EP_V19") (pintype "passive"))
      (node (ref "U4A") (pin "V2") (pinfunction "EP.VSS_EP_V2") (pintype "passive"))
      (node (ref "U4A") (pin "V20") (pinfunction "EP.VSS_EP_V20") (pintype "passive"))
      (node (ref "U4A") (pin "V21") (pinfunction "EP.VSS_EP_V21") (pintype "passive"))
      (node (ref "U4A") (pin "V22") (pinfunction "EP.VSS_EP_V22") (pintype "passive"))
      (node (ref "U4A") (pin "V23") (pinfunction "EP.VSS_EP_V23") (pintype "passive"))
      (node (ref "U4A") (pin "V24") (pinfunction "EP.VSS_EP_V24") (pintype "passive"))
      (node (ref "U4A") (pin "V25") (pinfunction "EP.VSS_EP_V25") (pintype "passive"))
      (node (ref "U4A") (pin "V3") (pinfunction "EP.VSS_EP_V3") (pintype "passive"))
      (node (ref "U4A") (pin "V4") (pinfunction "EP.VSS_EP_V4") (pintype "passive"))
      (node (ref "U4A") (pin "V5") (pinfunction "EP.VSS_EP_V5") (pintype "passive"))
      (node (ref "U4A") (pin "V6") (pinfunction "EP.VSS_EP_V6") (pintype "passive"))
      (node (ref "U4A") (pin "V7") (pinfunction "EP.VSS_EP_V7") (pintype "passive"))
      (node (ref "U4A") (pin "V8") (pinfunction "EP.VSS_EP_V8") (pintype "passive"))
      (node (ref "U4A") (pin "V9") (pinfunction "EP.VSS_EP_V9") (pintype "passive"))
      (node (ref "U4B") (pin "1") (pinfunction "1.QCM_1") (pintype "passive"))
      (node (ref "U4B") (pin "2") (pinfunction "2.CMPLUS_2") (pintype "passive"))
      (node (ref "U4B") (pin "3") (pinfunction "3.CMMINUS_3") (pintype "passive"))
      (node (ref "U4B") (pin "EP") (pinfunction "EP.VSS_EP_EP") (pintype "passive"))
      (node (ref "U4B") (pin "V1") (pinfunction "EP.VSS_EP_V1") (pintype "passive"))
      (node (ref "U4B") (pin "V10") (pinfunction "EP.VSS_EP_V10") (pintype "passive"))
      (node (ref "U4B") (pin "V11") (pinfunction "EP.VSS_EP_V11") (pintype "passive"))
      (node (ref "U4B") (pin "V12") (pinfunction "EP.VSS_EP_V12") (pintype "passive"))
      (node (ref "U4B") (pin "V13") (pinfunction "EP.VSS_EP_V13") (pintype "passive"))
      (node (ref "U4B") (pin "V14") (pinfunction "EP.VSS_EP_V14") (pintype "passive"))
      (node (ref "U4B") (pin "V15") (pinfunction "EP.VSS_EP_V15") (pintype "passive"))
      (node (ref "U4B") (pin "V16") (pinfunction "EP.VSS_EP_V16") (pintype "passive"))
      (node (ref "U4B") (pin "V17") (pinfunction "EP.VSS_EP_V17") (pintype "passive"))
      (node (ref "U4B") (pin "V18") (pinfunction "EP.VSS_EP_V18") (pintype "passive"))
      (node (ref "U4B") (pin "V19") (pinfunction "EP.VSS_EP_V19") (pintype "passive"))
      (node (ref "U4B") (pin "V2") (pinfunction "EP.VSS_EP_V2") (pintype "passive"))
      (node (ref "U4B") (pin "V20") (pinfunction "EP.VSS_EP_V20") (pintype "passive"))
      (node (ref "U4B") (pin "V21") (pinfunction "EP.VSS_EP_V21") (pintype "passive"))
      (node (ref "U4B") (pin "V22") (pinfunction "EP.VSS_EP_V22") (pintype "passive"))
      (node (ref "U4B") (pin "V23") (pinfunction "EP.VSS_EP_V23") (pintype "passive"))
      (node (ref "U4B") (pin "V24") (pinfunction "EP.VSS_EP_V24") (pintype "passive"))
      (node (ref "U4B") (pin "V25") (pinfunction "EP.VSS_EP_V25") (pintype "passive"))
      (node (ref "U4B") (pin "V3") (pinfunction "EP.VSS_EP_V3") (pintype "passive"))
      (node (ref "U4B") (pin "V4") (pinfunction "EP.VSS_EP_V4") (pintype "passive"))
      (node (ref "U4B") (pin "V5") (pinfunction "EP.VSS_EP_V5") (pintype "passive"))
      (node (ref "U4B") (pin "V6") (pinfunction "EP.VSS_EP_V6") (pintype "passive"))
      (node (ref "U4B") (pin "V7") (pinfunction "EP.VSS_EP_V7") (pintype "passive"))
      (node (ref "U4B") (pin "V8") (pinfunction "EP.VSS_EP_V8") (pintype "passive"))
      (node (ref "U4B") (pin "V9") (pinfunction "EP.VSS_EP_V9") (pintype "passive"))
      (node (ref "U4C") (pin "1") (pinfunction "1.QCM_1") (pintype "passive"))
      (node (ref "U4C") (pin "2") (pinfunction "2.CMPLUS_2") (pintype "passive"))
      (node (ref "U4C") (pin "3") (pinfunction "3.CMMINUS_3") (pintype "passive"))
      (node (ref "U4C") (pin "EP") (pinfunction "EP.VSS_EP_EP") (pintype "passive"))
      (node (ref "U4C") (pin "V1") (pinfunction "EP.VSS_EP_V1") (pintype "passive"))
      (node (ref "U4C") (pin "V10") (pinfunction "EP.VSS_EP_V10") (pintype "passive"))
      (node (ref "U4C") (pin "V11") (pinfunction "EP.VSS_EP_V11") (pintype "passive"))
      (node (ref "U4C") (pin "V12") (pinfunction "EP.VSS_EP_V12") (pintype "passive"))
      (node (ref "U4C") (pin "V13") (pinfunction "EP.VSS_EP_V13") (pintype "passive"))
      (node (ref "U4C") (pin "V14") (pinfunction "EP.VSS_EP_V14") (pintype "passive"))
      (node (ref "U4C") (pin "V15") (pinfunction "EP.VSS_EP_V15") (pintype "passive"))
      (node (ref "U4C") (pin "V16") (pinfunction "EP.VSS_EP_V16") (pintype "passive"))
      (node (ref "U4C") (pin "V17") (pinfunction "EP.VSS_EP_V17") (pintype "passive"))
      (node (ref "U4C") (pin "V18") (pinfunction "EP.VSS_EP_V18") (pintype "passive"))
      (node (ref "U4C") (pin "V19") (pinfunction "EP.VSS_EP_V19") (pintype "passive"))
      (node (ref "U4C") (pin "V2") (pinfunction "EP.VSS_EP_V2") (pintype "passive"))
      (node (ref "U4C") (pin "V20") (pinfunction "EP.VSS_EP_V20") (pintype "passive"))
      (node (ref "U4C") (pin "V21") (pinfunction "EP.VSS_EP_V21") (pintype "passive"))
      (node (ref "U4C") (pin "V22") (pinfunction "EP.VSS_EP_V22") (pintype "passive"))
      (node (ref "U4C") (pin "V23") (pinfunction "EP.VSS_EP_V23") (pintype "passive"))
      (node (ref "U4C") (pin "V24") (pinfunction "EP.VSS_EP_V24") (pintype "passive"))
      (node (ref "U4C") (pin "V25") (pinfunction "EP.VSS_EP_V25") (pintype "passive"))
      (node (ref "U4C") (pin "V3") (pinfunction "EP.VSS_EP_V3") (pintype "passive"))
      (node (ref "U4C") (pin "V4") (pinfunction "EP.VSS_EP_V4") (pintype "passive"))
      (node (ref "U4C") (pin "V5") (pinfunction "EP.VSS_EP_V5") (pintype "passive"))
      (node (ref "U4C") (pin "V6") (pinfunction "EP.VSS_EP_V6") (pintype "passive"))
      (node (ref "U4C") (pin "V7") (pinfunction "EP.VSS_EP_V7") (pintype "passive"))
      (node (ref "U4C") (pin "V8") (pinfunction "EP.VSS_EP_V8") (pintype "passive"))
      (node (ref "U4C") (pin "V9") (pinfunction "EP.VSS_EP_V9") (pintype "passive"))
      (node (ref "U4D") (pin "1") (pinfunction "1.QCM_1") (pintype "passive"))
      (node (ref "U4D") (pin "2") (pinfunction "2.CMPLUS_2") (pintype "passive"))
      (node (ref "U4D") (pin "3") (pinfunction "3.CMMINUS_3") (pintype "passive"))
      (node (ref "U4D") (pin "EP") (pinfunction "EP.VSS_EP_EP") (pintype "passive"))
      (node (ref "U4D") (pin "V1") (pinfunction "EP.VSS_EP_V1") (pintype "passive"))
      (node (ref "U4D") (pin "V10") (pinfunction "EP.VSS_EP_V10") (pintype "passive"))
      (node (ref "U4D") (pin "V11") (pinfunction "EP.VSS_EP_V11") (pintype "passive"))
      (node (ref "U4D") (pin "V12") (pinfunction "EP.VSS_EP_V12") (pintype "passive"))
      (node (ref "U4D") (pin "V13") (pinfunction "EP.VSS_EP_V13") (pintype "passive"))
      (node (ref "U4D") (pin "V14") (pinfunction "EP.VSS_EP_V14") (pintype "passive"))
      (node (ref "U4D") (pin "V15") (pinfunction "EP.VSS_EP_V15") (pintype "passive"))
      (node (ref "U4D") (pin "V16") (pinfunction "EP.VSS_EP_V16") (pintype "passive"))
      (node (ref "U4D") (pin "V17") (pinfunction "EP.VSS_EP_V17") (pintype "passive"))
      (node (ref "U4D") (pin "V18") (pinfunction "EP.VSS_EP_V18") (pintype "passive"))
      (node (ref "U4D") (pin "V19") (pinfunction "EP.VSS_EP_V19") (pintype "passive"))
      (node (ref "U4D") (pin "V2") (pinfunction "EP.VSS_EP_V2") (pintype "passive"))
      (node (ref "U4D") (pin "V20") (pinfunction "EP.VSS_EP_V20") (pintype "passive"))
      (node (ref "U4D") (pin "V21") (pinfunction "EP.VSS_EP_V21") (pintype "passive"))
      (node (ref "U4D") (pin "V22") (pinfunction "EP.VSS_EP_V22") (pintype "passive"))
      (node (ref "U4D") (pin "V23") (pinfunction "EP.VSS_EP_V23") (pintype "passive"))
      (node (ref "U4D") (pin "V24") (pinfunction "EP.VSS_EP_V24") (pintype "passive"))
      (node (ref "U4D") (pin "V25") (pinfunction "EP.VSS_EP_V25") (pintype "passive"))
      (node (ref "U4D") (pin "V3") (pinfunction "EP.VSS_EP_V3") (pintype "passive"))
      (node (ref "U4D") (pin "V4") (pinfunction "EP.VSS_EP_V4") (pintype "passive"))
      (node (ref "U4D") (pin "V5") (pinfunction "EP.VSS_EP_V5") (pintype "passive"))
      (node (ref "U4D") (pin "V6") (pinfunction "EP.VSS_EP_V6") (pintype "passive"))
      (node (ref "U4D") (pin "V7") (pinfunction "EP.VSS_EP_V7") (pintype "passive"))
      (node (ref "U4D") (pin "V8") (pinfunction "EP.VSS_EP_V8") (pintype "passive"))
      (node (ref "U4D") (pin "V9") (pinfunction "EP.VSS_EP_V9") (pintype "passive"))
      (node (ref "U4E") (pin "1") (pinfunction "1.QCM_1") (pintype "passive"))
      (node (ref "U4E") (pin "2") (pinfunction "2.CMPLUS_2") (pintype "passive"))
      (node (ref "U4E") (pin "3") (pinfunction "3.CMMINUS_3") (pintype "passive"))
      (node (ref "U4E") (pin "EP") (pinfunction "EP.VSS_EP_EP") (pintype "passive"))
      (node (ref "U4E") (pin "V1") (pinfunction "EP.VSS_EP_V1") (pintype "passive"))
      (node (ref "U4E") (pin "V10") (pinfunction "EP.VSS_EP_V10") (pintype "passive"))
      (node (ref "U4E") (pin "V11") (pinfunction "EP.VSS_EP_V11") (pintype "passive"))
      (node (ref "U4E") (pin "V12") (pinfunction "EP.VSS_EP_V12") (pintype "passive"))
      (node (ref "U4E") (pin "V13") (pinfunction "EP.VSS_EP_V13") (pintype "passive"))
      (node (ref "U4E") (pin "V14") (pinfunction "EP.VSS_EP_V14") (pintype "passive"))
      (node (ref "U4E") (pin "V15") (pinfunction "EP.VSS_EP_V15") (pintype "passive"))
      (node (ref "U4E") (pin "V16") (pinfunction "EP.VSS_EP_V16") (pintype "passive"))
      (node (ref "U4E") (pin "V17") (pinfunction "EP.VSS_EP_V17") (pintype "passive"))
      (node (ref "U4E") (pin "V18") (pinfunction "EP.VSS_EP_V18") (pintype "passive"))
      (node (ref "U4E") (pin "V19") (pinfunction "EP.VSS_EP_V19") (pintype "passive"))
      (node (ref "U4E") (pin "V2") (pinfunction "EP.VSS_EP_V2") (pintype "passive"))
      (node (ref "U4E") (pin "V20") (pinfunction "EP.VSS_EP_V20") (pintype "passive"))
      (node (ref "U4E") (pin "V21") (pinfunction "EP.VSS_EP_V21") (pintype "passive"))
      (node (ref "U4E") (pin "V22") (pinfunction "EP.VSS_EP_V22") (pintype "passive"))
      (node (ref "U4E") (pin "V23") (pinfunction "EP.VSS_EP_V23") (pintype "passive"))
      (node (ref "U4E") (pin "V24") (pinfunction "EP.VSS_EP_V24") (pintype "passive"))
      (node (ref "U4E") (pin "V25") (pinfunction "EP.VSS_EP_V25") (pintype "passive"))
      (node (ref "U4E") (pin "V3") (pinfunction "EP.VSS_EP_V3") (pintype "passive"))
      (node (ref "U4E") (pin "V4") (pinfunction "EP.VSS_EP_V4") (pintype "passive"))
      (node (ref "U4E") (pin "V5") (pinfunction "EP.VSS_EP_V5") (pintype "passive"))
      (node (ref "U4E") (pin "V6") (pinfunction "EP.VSS_EP_V6") (pintype "passive"))
      (node (ref "U4E") (pin "V7") (pinfunction "EP.VSS_EP_V7") (pintype "passive"))
      (node (ref "U4E") (pin "V8") (pinfunction "EP.VSS_EP_V8") (pintype "passive"))
      (node (ref "U4E") (pin "V9") (pinfunction "EP.VSS_EP_V9") (pintype "passive"))
      (node (ref "U4F") (pin "1") (pinfunction "1.QCM_1") (pintype "passive"))
      (node (ref "U4F") (pin "2") (pinfunction "2.CMPLUS_2") (pintype "passive"))
      (node (ref "U4F") (pin "3") (pinfunction "3.CMMINUS_3") (pintype "passive"))
      (node (ref "U4F") (pin "EP") (pinfunction "EP.VSS_EP_EP") (pintype "passive"))
      (node (ref "U4F") (pin "V1") (pinfunction "EP.VSS_EP_V1") (pintype "passive"))
      (node (ref "U4F") (pin "V10") (pinfunction "EP.VSS_EP_V10") (pintype "passive"))
      (node (ref "U4F") (pin "V11") (pinfunction "EP.VSS_EP_V11") (pintype "passive"))
      (node (ref "U4F") (pin "V12") (pinfunction "EP.VSS_EP_V12") (pintype "passive"))
      (node (ref "U4F") (pin "V13") (pinfunction "EP.VSS_EP_V13") (pintype "passive"))
      (node (ref "U4F") (pin "V14") (pinfunction "EP.VSS_EP_V14") (pintype "passive"))
      (node (ref "U4F") (pin "V15") (pinfunction "EP.VSS_EP_V15") (pintype "passive"))
      (node (ref "U4F") (pin "V16") (pinfunction "EP.VSS_EP_V16") (pintype "passive"))
      (node (ref "U4F") (pin "V17") (pinfunction "EP.VSS_EP_V17") (pintype "passive"))
      (node (ref "U4F") (pin "V18") (pinfunction "EP.VSS_EP_V18") (pintype "passive"))
      (node (ref "U4F") (pin "V19") (pinfunction "EP.VSS_EP_V19") (pintype "passive"))
      (node (ref "U4F") (pin "V2") (pinfunction "EP.VSS_EP_V2") (pintype "passive"))
      (node (ref "U4F") (pin "V20") (pinfunction "EP.VSS_EP_V20") (pintype "passive"))
      (node (ref "U4F") (pin "V21") (pinfunction "EP.VSS_EP_V21") (pintype "passive"))
      (node (ref "U4F") (pin "V22") (pinfunction "EP.VSS_EP_V22") (pintype "passive"))
      (node (ref "U4F") (pin "V23") (pinfunction "EP.VSS_EP_V23") (pintype "passive"))
      (node (ref "U4F") (pin "V24") (pinfunction "EP.VSS_EP_V24") (pintype "passive"))
      (node (ref "U4F") (pin "V25") (pinfunction "EP.VSS_EP_V25") (pintype "passive"))
      (node (ref "U4F") (pin "V3") (pinfunction "EP.VSS_EP_V3") (pintype "passive"))
      (node (ref "U4F") (pin "V4") (pinfunction "EP.VSS_EP_V4") (pintype "passive"))
      (node (ref "U4F") (pin "V5") (pinfunction "EP.VSS_EP_V5") (pintype "passive"))
      (node (ref "U4F") (pin "V6") (pinfunction "EP.VSS_EP_V6") (pintype "passive"))
      (node (ref "U4F") (pin "V7") (pinfunction "EP.VSS_EP_V7") (pintype "passive"))
      (node (ref "U4F") (pin "V8") (pinfunction "EP.VSS_EP_V8") (pintype "passive"))
      (node (ref "U4F") (pin "V9") (pinfunction "EP.VSS_EP_V9") (pintype "passive"))
    )
    (net (code "17") (name "INCLK") (class "Default")
      (node (ref "J01") (pin "A6") (pinfunction "6_A6") (pintype "passive"))
      (node (ref "SJ49") (pin "1") (pinfunction "P$1_1") (pintype "passive"))
      (node (ref "U40") (pin "12") (pinfunction "12.INCLK_12") (pintype "passive"))
    )
    (net (code "18") (name "INMISO") (class "Default")
      (node (ref "J01") (pin "A9") (pinfunction "9_A9") (pintype "passive"))
      (node (ref "SJ3") (pin "1") (pinfunction "P$1_1") (pintype "passive"))
      (node (ref "U40") (pin "9") (pinfunction "9.INMISO_9") (pintype "passive"))
    )
    (net (code "19") (name "INMOSI") (class "Default")
      (node (ref "J01") (pin "A8") (pinfunction "8_A8") (pintype "passive"))
      (node (ref "SJ2") (pin "1") (pinfunction "P$1_1") (pintype "passive"))
      (node (ref "U40") (pin "10") (pinfunction "10.INMOSI_10") (pintype "passive"))
    )
    (net (code "20") (name "INSCK") (class "Default")
      (node (ref "J01") (pin "A7") (pinfunction "7_A7") (pintype "passive"))
      (node (ref "SJ1") (pin "1") (pinfunction "P$1_1") (pintype "passive"))
      (node (ref "U40") (pin "11") (pinfunction "11.INSCK_11") (pintype "passive"))
    )
    (net (code "21") (name "MISO0") (class "Default")
      (node (ref "SJ3") (pin "2") (pinfunction "P$2_2") (pintype "passive"))
      (node (ref "SJ6") (pin "1") (pinfunction "P$1_1") (pintype "passive"))
      (node (ref "U40") (pin "8") (pinfunction "8.OUTMISO_8") (pintype "passive"))
      (node (ref "U41") (pin "9") (pinfunction "9.INMISO_9") (pintype "passive"))
    )
    (net (code "22") (name "MISO1") (class "Default")
      (node (ref "SJ6") (pin "2") (pinfunction "P$2_2") (pintype "passive"))
      (node (ref "SJ9") (pin "1") (pinfunction "P$1_1") (pintype "passive"))
      (node (ref "U41") (pin "8") (pinfunction "8.OUTMISO_8") (pintype "passive"))
      (node (ref "U42") (pin "9") (pinfunction "9.INMISO_9") (pintype "passive"))
    )
    (net (code "23") (name "MISO2") (class "Default")
      (node (ref "SJ12") (pin "1") (pinfunction "P$1_1") (pintype "passive"))
      (node (ref "SJ9") (pin "2") (pinfunction "P$2_2") (pintype "passive"))
      (node (ref "U42") (pin "8") (pinfunction "8.OUTMISO_8") (pintype "passive"))
      (node (ref "U43") (pin "9") (pinfunction "9.INMISO_9") (pintype "passive"))
    )
    (net (code "24") (name "MISO3") (class "Default")
      (node (ref "SJ12") (pin "2") (pinfunction "P$2_2") (pintype "passive"))
      (node (ref "SJ15") (pin "1") (pinfunction "P$1_1") (pintype "passive"))
      (node (ref "U43") (pin "8") (pinfunction "8.OUTMISO_8") (pintype "passive"))
      (node (ref "U44") (pin "9") (pinfunction "9.INMISO_9") (pintype "passive"))
    )
    (net (code "25") (name "MISO4") (class "Default")
      (node (ref "SJ15") (pin "2") (pinfunction "P$2_2") (pintype "passive"))
      (node (ref "SJ18") (pin "1") (pinfunction "P$1_1") (pintype "passive"))
      (node (ref "U44") (pin "8") (pinfunction "8.OUTMISO_8") (pintype "passive"))
      (node (ref "U45") (pin "9") (pinfunction "9.INMISO_9") (pintype "passive"))
    )
    (net (code "26") (name "MISO5") (class "Default")
      (node (ref "SJ18") (pin "2") (pinfunction "P$2_2") (pintype "passive"))
      (node (ref "SJ21") (pin "1") (pinfunction "P$1_1") (pintype "passive"))
      (node (ref "U45") (pin "8") (pinfunction "8.OUTMISO_8") (pintype "passive"))
      (node (ref "U46") (pin "9") (pinfunction "9.INMISO_9") (pintype "passive"))
    )
    (net (code "27") (name "MISO6") (class "Default")
      (node (ref "SJ21") (pin "2") (pinfunction "P$2_2") (pintype "passive"))
      (node (ref "SJ24") (pin "1") (pinfunction "P$1_1") (pintype "passive"))
      (node (ref "U46") (pin "8") (pinfunction "8.OUTMISO_8") (pintype "passive"))
      (node (ref "U47") (pin "9") (pinfunction "9.INMISO_9") (pintype "passive"))
    )
    (net (code "28") (name "MISO7") (class "Default")
      (node (ref "SJ24") (pin "2") (pinfunction "P$2_2") (pintype "passive"))
      (node (ref "SJ39") (pin "1") (pinfunction "P$1_1") (pintype "passive"))
      (node (ref "U47") (pin "8") (pinfunction "8.OUTMISO_8") (pintype "passive"))
      (node (ref "U48") (pin "9") (pinfunction "9.INMISO_9") (pintype "passive"))
    )
    (net (code "29") (name "MISO8") (class "Default")
      (node (ref "SJ39") (pin "2") (pinfunction "P$2_2") (pintype "passive"))
      (node (ref "SJ42") (pin "1") (pinfunction "P$1_1") (pintype "passive"))
      (node (ref "U48") (pin "8") (pinfunction "8.OUTMISO_8") (pintype "passive"))
      (node (ref "U49") (pin "9") (pinfunction "9.INMISO_9") (pintype "passive"))
    )
    (net (code "30") (name "MISO9") (class "Default")
      (node (ref "SJ42") (pin "2") (pinfunction "P$2_2") (pintype "passive"))
      (node (ref "SJ45") (pin "1") (pinfunction "P$1_1") (pintype "passive"))
      (node (ref "U49") (pin "8") (pinfunction "8.OUTMISO_8") (pintype "passive"))
      (node (ref "U4A") (pin "9") (pinfunction "9.INMISO_9") (pintype "passive"))
    )
    (net (code "31") (name "MISO10") (class "Default")
      (node (ref "SJ45") (pin "2") (pinfunction "P$2_2") (pintype "passive"))
      (node (ref "SJ48") (pin "1") (pinfunction "P$1_1") (pintype "passive"))
      (node (ref "U4A") (pin "8") (pinfunction "8.OUTMISO_8") (pintype "passive"))
      (node (ref "U4B") (pin "9") (pinfunction "9.INMISO_9") (pintype "passive"))
    )
    (net (code "32") (name "MISO11") (class "Default")
      (node (ref "SJ27") (pin "1") (pinfunction "P$1_1") (pintype "passive"))
      (node (ref "SJ48") (pin "2") (pinfunction "P$2_2") (pintype "passive"))
      (node (ref "U4B") (pin "8") (pinfunction "8.OUTMISO_8") (pintype "passive"))
      (node (ref "U4C") (pin "9") (pinfunction "9.INMISO_9") (pintype "passive"))
    )
    (net (code "33") (name "MISO12") (class "Default")
      (node (ref "SJ27") (pin "2") (pinfunction "P$2_2") (pintype "passive"))
      (node (ref "SJ30") (pin "1") (pinfunction "P$1_1") (pintype "passive"))
      (node (ref "U4C") (pin "8") (pinfunction "8.OUTMISO_8") (pintype "passive"))
      (node (ref "U4D") (pin "9") (pinfunction "9.INMISO_9") (pintype "passive"))
    )
    (net (code "34") (name "MISO13") (class "Default")
      (node (ref "SJ30") (pin "2") (pinfunction "P$2_2") (pintype "passive"))
      (node (ref "SJ33") (pin "1") (pinfunction "P$1_1") (pintype "passive"))
      (node (ref "U4D") (pin "8") (pinfunction "8.OUTMISO_8") (pintype "passive"))
      (node (ref "U4E") (pin "9") (pinfunction "9.INMISO_9") (pintype "passive"))
    )
    (net (code "35") (name "MISO14") (class "Default")
      (node (ref "SJ33") (pin "2") (pinfunction "P$2_2") (pintype "passive"))
      (node (ref "SJ36") (pin "1") (pinfunction "P$1_1") (pintype "passive"))
      (node (ref "U4E") (pin "8") (pinfunction "8.OUTMISO_8") (pintype "passive"))
      (node (ref "U4F") (pin "9") (pinfunction "9.INMISO_9") (pintype "passive"))
    )
    (net (code "36") (name "MOSI0") (class "Default")
      (node (ref "SJ2") (pin "2") (pinfunction "P$2_2") (pintype "passive"))
      (node (ref "SJ5") (pin "1") (pinfunction "P$1_1") (pintype "passive"))
      (node (ref "U40") (pin "7") (pinfunction "7.OUTMOSI_7") (pintype "passive"))
      (node (ref "U41") (pin "10") (pinfunction "10.INMOSI_10") (pintype "passive"))
    )
    (net (code "37") (name "MOSI1") (class "Default")
      (node (ref "SJ5") (pin "2") (pinfunction "P$2_2") (pintype "passive"))
      (node (ref "SJ8") (pin "1") (pinfunction "P$1_1") (pintype "passive"))
      (node (ref "U41") (pin "7") (pinfunction "7.OUTMOSI_7") (pintype "passive"))
      (node (ref "U42") (pin "10") (pinfunction "10.INMOSI_10") (pintype "passive"))
    )
    (net (code "38") (name "MOSI2") (class "Default")
      (node (ref "SJ11") (pin "1") (pinfunction "P$1_1") (pintype "passive"))
      (node (ref "SJ8") (pin "2") (pinfunction "P$2_2") (pintype "passive"))
      (node (ref "U42") (pin "7") (pinfunction "7.OUTMOSI_7") (pintype "passive"))
      (node (ref "U43") (pin "10") (pinfunction "10.INMOSI_10") (pintype "passive"))
    )
    (net (code "39") (name "MOSI3") (class "Default")
      (node (ref "SJ11") (pin "2") (pinfunction "P$2_2") (pintype "passive"))
      (node (ref "SJ14") (pin "1") (pinfunction "P$1_1") (pintype "passive"))
      (node (ref "U43") (pin "7") (pinfunction "7.OUTMOSI_7") (pintype "passive"))
      (node (ref "U44") (pin "10") (pinfunction "10.INMOSI_10") (pintype "passive"))
    )
    (net (code "40") (name "MOSI4") (class "Default")
      (node (ref "SJ14") (pin "2") (pinfunction "P$2_2") (pintype "passive"))
      (node (ref "SJ17") (pin "1") (pinfunction "P$1_1") (pintype "passive"))
      (node (ref "U44") (pin "7") (pinfunction "7.OUTMOSI_7") (pintype "passive"))
      (node (ref "U45") (pin "10") (pinfunction "10.INMOSI_10") (pintype "passive"))
    )
    (net (code "41") (name "MOSI5") (class "Default")
      (node (ref "SJ17") (pin "2") (pinfunction "P$2_2") (pintype "passive"))
      (node (ref "SJ20") (pin "1") (pinfunction "P$1_1") (pintype "passive"))
      (node (ref "U45") (pin "7") (pinfunction "7.OUTMOSI_7") (pintype "passive"))
      (node (ref "U46") (pin "10") (pinfunction "10.INMOSI_10") (pintype "passive"))
    )
    (net (code "42") (name "MOSI6") (class "Default")
      (node (ref "SJ20") (pin "2") (pinfunction "P$2_2") (pintype "passive"))
      (node (ref "SJ23") (pin "1") (pinfunction "P$1_1") (pintype "passive"))
      (node (ref "U46") (pin "7") (pinfunction "7.OUTMOSI_7") (pintype "passive"))
      (node (ref "U47") (pin "10") (pinfunction "10.INMOSI_10") (pintype "passive"))
    )
    (net (code "43") (name "MOSI7") (class "Default")
      (node (ref "SJ23") (pin "2") (pinfunction "P$2_2") (pintype "passive"))
      (node (ref "SJ38") (pin "1") (pinfunction "P$1_1") (pintype "passive"))
      (node (ref "U47") (pin "7") (pinfunction "7.OUTMOSI_7") (pintype "passive"))
      (node (ref "U48") (pin "10") (pinfunction "10.INMOSI_10") (pintype "passive"))
    )
    (net (code "44") (name "MOSI8") (class "Default")
      (node (ref "SJ38") (pin "2") (pinfunction "P$2_2") (pintype "passive"))
      (node (ref "SJ41") (pin "1") (pinfunction "P$1_1") (pintype "passive"))
      (node (ref "U48") (pin "7") (pinfunction "7.OUTMOSI_7") (pintype "passive"))
      (node (ref "U49") (pin "10") (pinfunction "10.INMOSI_10") (pintype "passive"))
    )
    (net (code "45") (name "MOSI9") (class "Default")
      (node (ref "SJ41") (pin "2") (pinfunction "P$2_2") (pintype "passive"))
      (node (ref "SJ44") (pin "1") (pinfunction "P$1_1") (pintype "passive"))
      (node (ref "U49") (pin "7") (pinfunction "7.OUTMOSI_7") (pintype "passive"))
      (node (ref "U4A") (pin "10") (pinfunction "10.INMOSI_10") (pintype "passive"))
    )
    (net (code "46") (name "MOSI10") (class "Default")
      (node (ref "SJ44") (pin "2") (pinfunction "P$2_2") (pintype "passive"))
      (node (ref "SJ47") (pin "1") (pinfunction "P$1_1") (pintype "passive"))
      (node (ref "U4A") (pin "7") (pinfunction "7.OUTMOSI_7") (pintype "passive"))
      (node (ref "U4B") (pin "10") (pinfunction "10.INMOSI_10") (pintype "passive"))
    )
    (net (code "47") (name "MOSI11") (class "Default")
      (node (ref "SJ26") (pin "1") (pinfunction "P$1_1") (pintype "passive"))
      (node (ref "SJ47") (pin "2") (pinfunction "P$2_2") (pintype "passive"))
      (node (ref "U4B") (pin "7") (pinfunction "7.OUTMOSI_7") (pintype "passive"))
      (node (ref "U4C") (pin "10") (pinfunction "10.INMOSI_10") (pintype "passive"))
    )
    (net (code "48") (name "MOSI12") (class "Default")
      (node (ref "SJ26") (pin "2") (pinfunction "P$2_2") (pintype "passive"))
      (node (ref "SJ29") (pin "1") (pinfunction "P$1_1") (pintype "passive"))
      (node (ref "U4C") (pin "7") (pinfunction "7.OUTMOSI_7") (pintype "passive"))
      (node (ref "U4D") (pin "10") (pinfunction "10.INMOSI_10") (pintype "passive"))
    )
    (net (code "49") (name "MOSI13") (class "Default")
      (node (ref "SJ29") (pin "2") (pinfunction "P$2_2") (pintype "passive"))
      (node (ref "SJ32") (pin "1") (pinfunction "P$1_1") (pintype "passive"))
      (node (ref "U4D") (pin "7") (pinfunction "7.OUTMOSI_7") (pintype "passive"))
      (node (ref "U4E") (pin "10") (pinfunction "10.INMOSI_10") (pintype "passive"))
    )
    (net (code "50") (name "MOSI14") (class "Default")
      (node (ref "SJ32") (pin "2") (pinfunction "P$2_2") (pintype "passive"))
      (node (ref "SJ35") (pin "1") (pinfunction "P$1_1") (pintype "passive"))
      (node (ref "U4E") (pin "7") (pinfunction "7.OUTMOSI_7") (pintype "passive"))
      (node (ref "U4F") (pin "10") (pinfunction "10.INMOSI_10") (pintype "passive"))
    )
    (net (code "51") (name "Net-(C01B-Pad2)") (class "Default")
      (node (ref "C01B") (pin "2") (pinfunction "2_2") (pintype "passive"))
      (node (ref "R01B") (pin "1") (pinfunction "1_1") (pintype "passive"))
    )
    (net (code "52") (name "Net-(C01L-Pad1)") (class "Default")
      (node (ref "C01L") (pin "1") (pinfunction "1_1") (pintype "passive"))
      (node (ref "C10F") (pin "2") (pinfunction "2_2") (pintype "passive"))
      (node (ref "R01L") (pin "2") (pinfunction "2_2") (pintype "passive"))
    )
    (net (code "53") (name "Net-(C01S-Pad2)") (class "Default")
      (node (ref "C01S") (pin "2") (pinfunction "2_2") (pintype "passive"))
      (node (ref "R01S") (pin "1") (pinfunction "1_1") (pintype "passive"))
    )
    (net (code "54") (name "Net-(F01I-P$2)") (class "Default")
      (node (ref "F01I") (pin "2") (pinfunction "P$2_2") (pintype "passive"))
      (node (ref "L01I") (pin "1") (pinfunction "1_1") (pintype "passive"))
    )
    (net (code "55") (name "Net-(U01-1.VFB)") (class "Default")
      (node (ref "C10F") (pin "1") (pinfunction "1_1") (pintype "passive"))
      (node (ref "R01F") (pin "1") (pinfunction "1_1") (pintype "passive"))
      (node (ref "R02F") (pin "1") (pinfunction "1_1") (pintype "passive"))
      (node (ref "U01") (pin "1") (pinfunction "1.VFB_1") (pintype "passive"))
    )
    (net (code "56") (name "Net-(U01-2.EN)") (class "Default")
      (node (ref "R01E") (pin "1") (pinfunction "1_1") (pintype "passive"))
      (node (ref "R02E") (pin "1") (pinfunction "1_1") (pintype "passive"))
      (node (ref "U01") (pin "2") (pinfunction "2.EN_2") (pintype "passive"))
    )
    (net (code "57") (name "Net-(U01-3.PGOOD)") (class "Default")
      (node (ref "R01R") (pin "1") (pinfunction "1_1") (pintype "passive"))
      (node (ref "U01") (pin "3") (pinfunction "3.PGOOD_3") (pintype "passive"))
    )
    (net (code "58") (name "Net-(U01-4.VBST)") (class "Default")
      (node (ref "R01B") (pin "2") (pinfunction "2_2") (pintype "passive"))
      (node (ref "U01") (pin "4") (pinfunction "4.VBST_4") (pintype "passive"))
    )
    (net (code "59") (name "Net-(U01-10.LL)") (class "Default")
      (node (ref "C01B") (pin "1") (pinfunction "1_1") (pintype "passive"))
      (node (ref "C01S") (pin "1") (pinfunction "1_1") (pintype "passive"))
      (node (ref "L01") (pin "1") (pinfunction "1_1") (pintype "passive"))
      (node (ref "R01L") (pin "1") (pinfunction "1_1") (pintype "passive"))
      (node (ref "U01") (pin "10") (pinfunction "10.LL_10") (pintype "passive"))
      (node (ref "U01") (pin "11") (pinfunction "11.LL_11") (pintype "passive"))
      (node (ref "U01") (pin "6") (pinfunction "6.LL_6") (pintype "passive"))
      (node (ref "U01") (pin "7") (pinfunction "7.LL_7") (pintype "passive"))
      (node (ref "U01") (pin "8") (pinfunction "8.LL_8") (pintype "passive"))
      (node (ref "U01") (pin "9") (pinfunction "9.LL_9") (pintype "passive"))
    )
    (net (code "60") (name "Net-(U01-18.VREG)") (class "Default")
      (node (ref "C01R") (pin "1") (pinfunction "1_1") (pintype "passive"))
      (node (ref "R01R") (pin "2") (pinfunction "2_2") (pintype "passive"))
      (node (ref "U01") (pin "18") (pinfunction "18.VREG_18") (pintype "passive"))
    )
    (net (code "61") (name "Net-(U01-20.MODE)") (class "Default")
      (node (ref "R01M") (pin "1") (pinfunction "1_1") (pintype "passive"))
      (node (ref "U01") (pin "20") (pinfunction "20.MODE_20") (pintype "passive"))
    )
    (net (code "62") (name "Net-(U01-21.TRIP)") (class "Default")
      (node (ref "R01T") (pin "1") (pinfunction "1_1") (pintype "passive"))
      (node (ref "U01") (pin "21") (pinfunction "21.TRIP_21") (pintype "passive"))
    )
    (net (code "63") (name "Net-(U01-22.RF)") (class "Default")
      (node (ref "R01T1") (pin "1") (pinfunction "1_1") (pintype "passive"))
      (node (ref "U01") (pin "22") (pinfunction "22.RF_22") (pintype "passive"))
    )
    (net (code "64") (name "OUTCLK") (class "Default")
      (node (ref "J01") (pin "B5") (pinfunction "15_B5") (pintype "passive"))
      (node (ref "SJ64") (pin "2") (pinfunction "P$2_2") (pintype "passive"))
      (node (ref "U4F") (pin "5") (pinfunction "5.OUTCLK_5") (pintype "passive"))
    )
    (net (code "65") (name "OUTMISO") (class "Default")
      (node (ref "J01") (pin "B8") (pinfunction "18_B8") (pintype "passive"))
      (node (ref "SJ36") (pin "2") (pinfunction "P$2_2") (pintype "passive"))
      (node (ref "U4F") (pin "8") (pinfunction "8.OUTMISO_8") (pintype "passive"))
    )
    (net (code "66") (name "OUTMOSI") (class "Default")
      (node (ref "J01") (pin "B7") (pinfunction "17_B7") (pintype "passive"))
      (node (ref "SJ35") (pin "2") (pinfunction "P$2_2") (pintype "passive"))
      (node (ref "U4F") (pin "7") (pinfunction "7.OUTMOSI_7") (pintype "passive"))
    )
    (net (code "67") (name "OUTSCK") (class "Default")
      (node (ref "J01") (pin "B6") (pinfunction "16_B6") (pintype "passive"))
      (node (ref "SJ34") (pin "2") (pinfunction "P$2_2") (pintype "passive"))
      (node (ref "U4F") (pin "6") (pinfunction "6.OUTSCK_6") (pintype "passive"))
    )
    (net (code "68") (name "SCK0") (class "Default")
      (node (ref "SJ1") (pin "2") (pinfunction "P$2_2") (pintype "passive"))
      (node (ref "SJ4") (pin "1") (pinfunction "P$1_1") (pintype "passive"))
      (node (ref "U40") (pin "6") (pinfunction "6.OUTSCK_6") (pintype "passive"))
      (node (ref "U41") (pin "11") (pinfunction "11.INSCK_11") (pintype "passive"))
    )
    (net (code "69") (name "SCK1") (class "Default")
      (node (ref "SJ4") (pin "2") (pinfunction "P$2_2") (pintype "passive"))
      (node (ref "SJ7") (pin "1") (pinfunction "P$1_1") (pintype "passive"))
      (node (ref "U41") (pin "6") (pinfunction "6.OUTSCK_6") (pintype "passive"))
      (node (ref "U42") (pin "11") (pinfunction "11.INSCK_11") (pintype "passive"))
    )
    (net (code "70") (name "SCK2") (class "Default")
      (node (ref "SJ10") (pin "1") (pinfunction "P$1_1") (pintype "passive"))
      (node (ref "SJ7") (pin "2") (pinfunction "P$2_2") (pintype "passive"))
      (node (ref "U42") (pin "6") (pinfunction "6.OUTSCK_6") (pintype "passive"))
      (node (ref "U43") (pin "11") (pinfunction "11.INSCK_11") (pintype "passive"))
    )
    (net (code "71") (name "SCK3") (class "Default")
      (node (ref "SJ10") (pin "2") (pinfunction "P$2_2") (pintype "passive"))
      (node (ref "SJ13") (pin "1") (pinfunction "P$1_1") (pintype "passive"))
      (node (ref "U43") (pin "6") (pinfunction "6.OUTSCK_6") (pintype "passive"))
      (node (ref "U44") (pin "11") (pinfunction "11.INSCK_11") (pintype "passive"))
    )
    (net (code "72") (name "SCK4") (class "Default")
      (node (ref "SJ13") (pin "2") (pinfunction "P$2_2") (pintype "passive"))
      (node (ref "SJ16") (pin "1") (pinfunction "P$1_1") (pintype "passive"))
      (node (ref "U44") (pin "6") (pinfunction "6.OUTSCK_6") (pintype "passive"))
      (node (ref "U45") (pin "11") (pinfunction "11.INSCK_11") (pintype "passive"))
    )
    (net (code "73") (name "SCK5") (class "Default")
      (node (ref "SJ16") (pin "2") (pinfunction "P$2_2") (pintype "passive"))
      (node (ref "SJ19") (pin "1") (pinfunction "P$1_1") (pintype "passive"))
      (node (ref "U45") (pin "6") (pinfunction "6.OUTSCK_6") (pintype "passive"))
      (node (ref "U46") (pin "11") (pinfunction "11.INSCK_11") (pintype "passive"))
    )
    (net (code "74") (name "SCK6") (class "Default")
      (node (ref "SJ19") (pin "2") (pinfunction "P$2_2") (pintype "passive"))
      (node (ref "SJ22") (pin "1") (pinfunction "P$1_1") (pintype "passive"))
      (node (ref "U46") (pin "6") (pinfunction "6.OUTSCK_6") (pintype "passive"))
      (node (ref "U47") (pin "11") (pinfunction "11.INSCK_11") (pintype "passive"))
    )
    (net (code "75") (name "SCK7") (class "Default")
      (node (ref "SJ22") (pin "2") (pinfunction "P$2_2") (pintype "passive"))
      (node (ref "SJ37") (pin "1") (pinfunction "P$1_1") (pintype "passive"))
      (node (ref "U47") (pin "6") (pinfunction "6.OUTSCK_6") (pintype "passive"))
      (node (ref "U48") (pin "11") (pinfunction "11.INSCK_11") (pintype "passive"))
    )
    (net (code "76") (name "SCK8") (class "Default")
      (node (ref "SJ37") (pin "2") (pinfunction "P$2_2") (pintype "passive"))
      (node (ref "SJ40") (pin "1") (pinfunction "P$1_1") (pintype "passive"))
      (node (ref "U48") (pin "6") (pinfunction "6.OUTSCK_6") (pintype "passive"))
      (node (ref "U49") (pin "11") (pinfunction "11.INSCK_11") (pintype "passive"))
    )
    (net (code "77") (name "SCK9") (class "Default")
      (node (ref "SJ40") (pin "2") (pinfunction "P$2_2") (pintype "passive"))
      (node (ref "SJ43") (pin "1") (pinfunction "P$1_1") (pintype "passive"))
      (node (ref "U49") (pin "6") (pinfunction "6.OUTSCK_6") (pintype "passive"))
      (node (ref "U4A") (pin "11") (pinfunction "11.INSCK_11") (pintype "passive"))
    )
    (net (code "78") (name "SCK10") (class "Default")
      (node (ref "SJ43") (pin "2") (pinfunction "P$2_2") (pintype "passive"))
      (node (ref "SJ46") (pin "1") (pinfunction "P$1_1") (pintype "passive"))
      (node (ref "U4A") (pin "6") (pinfunction "6.OUTSCK_6") (pintype "passive"))
      (node (ref "U4B") (pin "11") (pinfunction "11.INSCK_11") (pintype "passive"))
    )
    (net (code "79") (name "SCK11") (class "Default")
      (node (ref "SJ25") (pin "1") (pinfunction "P$1_1") (pintype "passive"))
      (node (ref "SJ46") (pin "2") (pinfunction "P$2_2") (pintype "passive"))
      (node (ref "U4B") (pin "6") (pinfunction "6.OUTSCK_6") (pintype "passive"))
      (node (ref "U4C") (pin "11") (pinfunction "11.INSCK_11") (pintype "passive"))
    )
    (net (code "80") (name "SCK12") (class "Default")
      (node (ref "SJ25") (pin "2") (pinfunction "P$2_2") (pintype "passive"))
      (node (ref "SJ28") (pin "1") (pinfunction "P$1_1") (pintype "passive"))
      (node (ref "U4C") (pin "6") (pinfunction "6.OUTSCK_6") (pintype "passive"))
      (node (ref "U4D") (pin "11") (pinfunction "11.INSCK_11") (pintype "passive"))
    )
    (net (code "81") (name "SCK13") (class "Default")
      (node (ref "SJ28") (pin "2") (pinfunction "P$2_2") (pintype "passive"))
      (node (ref "SJ31") (pin "1") (pinfunction "P$1_1") (pintype "passive"))
      (node (ref "U4D") (pin "6") (pinfunction "6.OUTSCK_6") (pintype "passive"))
      (node (ref "U4E") (pin "11") (pinfunction "11.INSCK_11") (pintype "passive"))
    )
    (net (code "82") (name "SCK14") (class "Default")
      (node (ref "SJ31") (pin "2") (pinfunction "P$2_2") (pintype "passive"))
      (node (ref "SJ34") (pin "1") (pinfunction "P$1_1") (pintype "passive"))
      (node (ref "U4E") (pin "6") (pinfunction "6.OUTSCK_6") (pintype "passive"))
      (node (ref "U4F") (pin "11") (pinfunction "11.INSCK_11") (pintype "passive"))
    )
    (net (code "83") (name "VDD_0V9") (class "Default")
      (node (ref "C01L") (pin "2") (pinfunction "2_2") (pintype "passive"))
      (node (ref "C12") (pin "1") (pinfunction "1_1") (pintype "passive"))
      (node (ref "C13") (pin "1") (pinfunction "1_1") (pintype "passive"))
      (node (ref "C14") (pin "1") (pinfunction "1_1") (pintype "passive"))
      (node (ref "C15") (pin "1") (pinfunction "1_1") (pintype "passive"))
      (node (ref "C16") (pin "1") (pinfunction "1_1") (pintype "passive"))
      (node (ref "C400") (pin "1") (pinfunction "1_1") (pintype "passive"))
      (node (ref "C401") (pin "1") (pinfunction "1_1") (pintype "passive"))
      (node (ref "C402") (pin "1") (pinfunction "1_1") (pintype "passive"))
      (node (ref "C403") (pin "1") (pinfunction "1_1") (pintype "passive"))
      (node (ref "C404") (pin "1") (pinfunction "1_1") (pintype "passive"))
      (node (ref "C405") (pin "1") (pinfunction "1_1") (pintype "passive"))
      (node (ref "C406") (pin "1") (pinfunction "1_1") (pintype "passive"))
      (node (ref "C407") (pin "1") (pinfunction "1_1") (pintype "passive"))
      (node (ref "C408") (pin "1") (pinfunction "1_1") (pintype "passive"))
      (node (ref "C409") (pin "1") (pinfunction "1_1") (pintype "passive"))
      (node (ref "C40A") (pin "1") (pinfunction "1_1") (pintype "passive"))
      (node (ref "C40B") (pin "1") (pinfunction "1_1") (pintype "passive"))
      (node (ref "C40C") (pin "1") (pinfunction "1_1") (pintype "passive"))
      (node (ref "C40D") (pin "1") (pinfunction "1_1") (pintype "passive"))
      (node (ref "C40E") (pin "1") (pinfunction "1_1") (pintype "passive"))
      (node (ref "C40S") (pin "1") (pinfunction "1_1") (pintype "passive"))
      (node (ref "C410") (pin "1") (pinfunction "1_1") (pintype "passive"))
      (node (ref "C411") (pin "1") (pinfunction "1_1") (pintype "passive"))
      (node (ref "C412") (pin "1") (pinfunction "1_1") (pintype "passive"))
      (node (ref "C413") (pin "1") (pinfunction "1_1") (pintype "passive"))
      (node (ref "C414") (pin "1") (pinfunction "1_1") (pintype "passive"))
      (node (ref "C415") (pin "1") (pinfunction "1_1") (pintype "passive"))
      (node (ref "C416") (pin "1") (pinfunction "1_1") (pintype "passive"))
      (node (ref "C417") (pin "1") (pinfunction "1_1") (pintype "passive"))
      (node (ref "C418") (pin "1") (pinfunction "1_1") (pintype "passive"))
      (node (ref "C419") (pin "1") (pinfunction "1_1") (pintype "passive"))
      (node (ref "C41A") (pin "1") (pinfunction "1_1") (pintype "passive"))
      (node (ref "C41B") (pin "1") (pinfunction "1_1") (pintype "passive"))
      (node (ref "C41C") (pin "1") (pinfunction "1_1") (pintype "passive"))
      (node (ref "C41D") (pin "1") (pinfunction "1_1") (pintype "passive"))
      (node (ref "C41E") (pin "1") (pinfunction "1_1") (pintype "passive"))
      (node (ref "C41S") (pin "1") (pinfunction "1_1") (pintype "passive"))
      (node (ref "C420") (pin "1") (pinfunction "1_1") (pintype "passive"))
      (node (ref "C421") (pin "1") (pinfunction "1_1") (pintype "passive"))
      (node (ref "C422") (pin "1") (pinfunction "1_1") (pintype "passive"))
      (node (ref "C423") (pin "1") (pinfunction "1_1") (pintype "passive"))
      (node (ref "C424") (pin "1") (pinfunction "1_1") (pintype "passive"))
      (node (ref "C425") (pin "1") (pinfunction "1_1") (pintype "passive"))
      (node (ref "C426") (pin "1") (pinfunction "1_1") (pintype "passive"))
      (node (ref "C427") (pin "1") (pinfunction "1_1") (pintype "passive"))
      (node (ref "C428") (pin "1") (pinfunction "1_1") (pintype "passive"))
      (node (ref "C429") (pin "1") (pinfunction "1_1") (pintype "passive"))
      (node (ref "C42A") (pin "1") (pinfunction "1_1") (pintype "passive"))
      (node (ref "C42B") (pin "1") (pinfunction "1_1") (pintype "passive"))
      (node (ref "C42C") (pin "1") (pinfunction "1_1") (pintype "passive"))
      (node (ref "C42D") (pin "1") (pinfunction "1_1") (pintype "passive"))
      (node (ref "C42E") (pin "1") (pinfunction "1_1") (pintype "passive"))
      (node (ref "C42S") (pin "1") (pinfunction "1_1") (pintype "passive"))
      (node (ref "C430") (pin "1") (pinfunction "1_1") (pintype "passive"))
      (node (ref "C431") (pin "1") (pinfunction "1_1") (pintype "passive"))
      (node (ref "C432") (pin "1") (pinfunction "1_1") (pintype "passive"))
      (node (ref "C433") (pin "1") (pinfunction "1_1") (pintype "passive"))
      (node (ref "C434") (pin "1") (pinfunction "1_1") (pintype "passive"))
      (node (ref "C435") (pin "1") (pinfunction "1_1") (pintype "passive"))
      (node (ref "C436") (pin "1") (pinfunction "1_1") (pintype "passive"))
      (node (ref "C437") (pin "1") (pinfunction "1_1") (pintype "passive"))
      (node (ref "C438") (pin "1") (pinfunction "1_1") (pintype "passive"))
      (node (ref "C439") (pin "1") (pinfunction "1_1") (pintype "passive"))
      (node (ref "C43A") (pin "1") (pinfunction "1_1") (pintype "passive"))
      (node (ref "C43B") (pin "1") (pinfunction "1_1") (pintype "passive"))
      (node (ref "C43C") (pin "1") (pinfunction "1_1") (pintype "passive"))
      (node (ref "C43D") (pin "1") (pinfunction "1_1") (pintype "passive"))
      (node (ref "C43E") (pin "1") (pinfunction "1_1") (pintype "passive"))
      (node (ref "C43S") (pin "1") (pinfunction "1_1") (pintype "passive"))
      (node (ref "C440") (pin "1") (pinfunction "1_1") (pintype "passive"))
      (node (ref "C441") (pin "1") (pinfunction "1_1") (pintype "passive"))
      (node (ref "C442") (pin "1") (pinfunction "1_1") (pintype "passive"))
      (node (ref "C443") (pin "1") (pinfunction "1_1") (pintype "passive"))
      (node (ref "C444") (pin "1") (pinfunction "1_1") (pintype "passive"))
      (node (ref "C445") (pin "1") (pinfunction "1_1") (pintype "passive"))
      (node (ref "C446") (pin "1") (pinfunction "1_1") (pintype "passive"))
      (node (ref "C447") (pin "1") (pinfunction "1_1") (pintype "passive"))
      (node (ref "C448") (pin "1") (pinfunction "1_1") (pintype "passive"))
      (node (ref "C449") (pin "1") (pinfunction "1_1") (pintype "passive"))
      (node (ref "C44A") (pin "1") (pinfunction "1_1") (pintype "passive"))
      (node (ref "C44B") (pin "1") (pinfunction "1_1") (pintype "passive"))
      (node (ref "C44C") (pin "1") (pinfunction "1_1") (pintype "passive"))
      (node (ref "C44D") (pin "1") (pinfunction "1_1") (pintype "passive"))
      (node (ref "C44E") (pin "1") (pinfunction "1_1") (pintype "passive"))
      (node (ref "C44S") (pin "1") (pinfunction "1_1") (pintype "passive"))
      (node (ref "C450") (pin "1") (pinfunction "1_1") (pintype "passive"))
      (node (ref "C451") (pin "1") (pinfunction "1_1") (pintype "passive"))
      (node (ref "C452") (pin "1") (pinfunction "1_1") (pintype "passive"))
      (node (ref "C453") (pin "1") (pinfunction "1_1") (pintype "passive"))
      (node (ref "C454") (pin "1") (pinfunction "1_1") (pintype "passive"))
      (node (ref "C455") (pin "1") (pinfunction "1_1") (pintype "passive"))
      (node (ref "C456") (pin "1") (pinfunction "1_1") (pintype "passive"))
      (node (ref "C457") (pin "1") (pinfunction "1_1") (pintype "passive"))
      (node (ref "C458") (pin "1") (pinfunction "1_1") (pintype "passive"))
      (node (ref "C459") (pin "1") (pinfunction "1_1") (pintype "passive"))
      (node (ref "C45A") (pin "1") (pinfunction "1_1") (pintype "passive"))
      (node (ref "C45B") (pin "1") (pinfunction "1_1") (pintype "passive"))
      (node (ref "C45C") (pin "1") (pinfunction "1_1") (pintype "passive"))
      (node (ref "C45D") (pin "1") (pinfunction "1_1") (pintype "passive"))
      (node (ref "C45E") (pin "1") (pinfunction "1_1") (pintype "passive"))
      (node (ref "C45S") (pin "1") (pinfunction "1_1") (pintype "passive"))
      (node (ref "C460") (pin "1") (pinfunction "1_1") (pintype "passive"))
      (node (ref "C461") (pin "1") (pinfunction "1_1") (pintype "passive"))
      (node (ref "C462") (pin "1") (pinfunction "1_1") (pintype "passive"))
      (node (ref "C463") (pin "1") (pinfunction "1_1") (pintype "passive"))
      (node (ref "C464") (pin "1") (pinfunction "1_1") (pintype "passive"))
      (node (ref "C465") (pin "1") (pinfunction "1_1") (pintype "passive"))
      (node (ref "C466") (pin "1") (pinfunction "1_1") (pintype "passive"))
      (node (ref "C467") (pin "1") (pinfunction "1_1") (pintype "passive"))
      (node (ref "C468") (pin "1") (pinfunction "1_1") (pintype "passive"))
      (node (ref "C469") (pin "1") (pinfunction "1_1") (pintype "passive"))
      (node (ref "C46A") (pin "1") (pinfunction "1_1") (pintype "passive"))
      (node (ref "C46B") (pin "1") (pinfunction "1_1") (pintype "passive"))
      (node (ref "C46C") (pin "1") (pinfunction "1_1") (pintype "passive"))
      (node (ref "C46D") (pin "1") (pinfunction "1_1") (pintype "passive"))
      (node (ref "C46E") (pin "1") (pinfunction "1_1") (pintype "passive"))
      (node (ref "C46S") (pin "1") (pinfunction "1_1") (pintype "passive"))
      (node (ref "C470") (pin "1") (pinfunction "1_1") (pintype "passive"))
      (node (ref "C471") (pin "1") (pinfunction "1_1") (pintype "passive"))
      (node (ref "C472") (pin "1") (pinfunction "1_1") (pintype "passive"))
      (node (ref "C473") (pin "1") (pinfunction "1_1") (pintype "passive"))
      (node (ref "C474") (pin "1") (pinfunction "1_1") (pintype "passive"))
      (node (ref "C475") (pin "1") (pinfunction "1_1") (pintype "passive"))
      (node (ref "C476") (pin "1") (pinfunction "1_1") (pintype "passive"))
      (node (ref "C477") (pin "1") (pinfunction "1_1") (pintype "passive"))
      (node (ref "C478") (pin "1") (pinfunction "1_1") (pintype "passive"))
      (node (ref "C479") (pin "1") (pinfunction "1_1") (pintype "passive"))
      (node (ref "C47A") (pin "1") (pinfunction "1_1") (pintype "passive"))
      (node (ref "C47B") (pin "1") (pinfunction "1_1") (pintype "passive"))
      (node (ref "C47C") (pin "1") (pinfunction "1_1") (pintype "passive"))
      (node (ref "C47D") (pin "1") (pinfunction "1_1") (pintype "passive"))
      (node (ref "C47E") (pin "1") (pinfunction "1_1") (pintype "passive"))
      (node (ref "C47S") (pin "1") (pinfunction "1_1") (pintype "passive"))
      (node (ref "C480") (pin "1") (pinfunction "1_1") (pintype "passive"))
      (node (ref "C481") (pin "1") (pinfunction "1_1") (pintype "passive"))
      (node (ref "C482") (pin "1") (pinfunction "1_1") (pintype "passive"))
      (node (ref "C483") (pin "1") (pinfunction "1_1") (pintype "passive"))
      (node (ref "C484") (pin "1") (pinfunction "1_1") (pintype "passive"))
      (node (ref "C485") (pin "1") (pinfunction "1_1") (pintype "passive"))
      (node (ref "C486") (pin "1") (pinfunction "1_1") (pintype "passive"))
      (node (ref "C487") (pin "1") (pinfunction "1_1") (pintype "passive"))
      (node (ref "C488") (pin "1") (pinfunction "1_1") (pintype "passive"))
      (node (ref "C489") (pin "1") (pinfunction "1_1") (pintype "passive"))
      (node (ref "C48A") (pin "1") (pinfunction "1_1") (pintype "passive"))
      (node (ref "C48B") (pin "1") (pinfunction "1_1") (pintype "passive"))
      (node (ref "C48C") (pin "1") (pinfunction "1_1") (pintype "passive"))
      (node (ref "C48D") (pin "1") (pinfunction "1_1") (pintype "passive"))
      (node (ref "C48E") (pin "1") (pinfunction "1_1") (pintype "passive"))
      (node (ref "C48S") (pin "1") (pinfunction "1_1") (pintype "passive"))
      (node (ref "C490") (pin "1") (pinfunction "1_1") (pintype "passive"))
      (node (ref "C491") (pin "1") (pinfunction "1_1") (pintype "passive"))
      (node (ref "C492") (pin "1") (pinfunction "1_1") (pintype "passive"))
      (node (ref "C493") (pin "1") (pinfunction "1_1") (pintype "passive"))
      (node (ref "C494") (pin "1") (pinfunction "1_1") (pintype "passive"))
      (node (ref "C495") (pin "1") (pinfunction "1_1") (pintype "passive"))
      (node (ref "C496") (pin "1") (pinfunction "1_1") (pintype "passive"))
      (node (ref "C497") (pin "1") (pinfunction "1_1") (pintype "passive"))
      (node (ref "C498") (pin "1") (pinfunction "1_1") (pintype "passive"))
      (node (ref "C499") (pin "1") (pinfunction "1_1") (pintype "passive"))
      (node (ref "C49A") (pin "1") (pinfunction "1_1") (pintype "passive"))
      (node (ref "C49B") (pin "1") (pinfunction "1_1") (pintype "passive"))
      (node (ref "C49C") (pin "1") (pinfunction "1_1") (pintype "passive"))
      (node (ref "C49D") (pin "1") (pinfunction "1_1") (pintype "passive"))
      (node (ref "C49E") (pin "1") (pinfunction "1_1") (pintype "passive"))
      (node (ref "C49S") (pin "1") (pinfunction "1_1") (pintype "passive"))
      (node (ref "C4A0") (pin "1") (pinfunction "1_1") (pintype "passive"))
      (node (ref "C4A1") (pin "1") (pinfunction "1_1") (pintype "passive"))
      (node (ref "C4A2") (pin "1") (pinfunction "1_1") (pintype "passive"))
      (node (ref "C4A3") (pin "1") (pinfunction "1_1") (pintype "passive"))
      (node (ref "C4A4") (pin "1") (pinfunction "1_1") (pintype "passive"))
      (node (ref "C4A5") (pin "1") (pinfunction "1_1") (pintype "passive"))
      (node (ref "C4A6") (pin "1") (pinfunction "1_1") (pintype "passive"))
      (node (ref "C4A7") (pin "1") (pinfunction "1_1") (pintype "passive"))
      (node (ref "C4A8") (pin "1") (pinfunction "1_1") (pintype "passive"))
      (node (ref "C4A9") (pin "1") (pinfunction "1_1") (pintype "passive"))
      (node (ref "C4AA") (pin "1") (pinfunction "1_1") (pintype "passive"))
      (node (ref "C4AB") (pin "1") (pinfunction "1_1") (pintype "passive"))
      (node (ref "C4AC") (pin "1") (pinfunction "1_1") (pintype "passive"))
      (node (ref "C4AD") (pin "1") (pinfunction "1_1") (pintype "passive"))
      (node (ref "C4AE") (pin "1") (pinfunction "1_1") (pintype "passive"))
      (node (ref "C4AS") (pin "1") (pinfunction "1_1") (pintype "passive"))
      (node (ref "C4B0") (pin "1") (pinfunction "1_1") (pintype "passive"))
      (node (ref "C4B1") (pin "1") (pinfunction "1_1") (pintype "passive"))
      (node (ref "C4B2") (pin "1") (pinfunction "1_1") (pintype "passive"))
      (node (ref "C4B3") (pin "1") (pinfunction "1_1") (pintype "passive"))
      (node (ref "C4B4") (pin "1") (pinfunction "1_1") (pintype "passive"))
      (node (ref "C4B5") (pin "1") (pinfunction "1_1") (pintype "passive"))
      (node (ref "C4B6") (pin "1") (pinfunction "1_1") (pintype "passive"))
      (node (ref "C4B7") (pin "1") (pinfunction "1_1") (pintype "passive"))
      (node (ref "C4B8") (pin "1") (pinfunction "1_1") (pintype "passive"))
      (node (ref "C4B9") (pin "1") (pinfunction "1_1") (pintype "passive"))
      (node (ref "C4BA") (pin "1") (pinfunction "1_1") (pintype "passive"))
      (node (ref "C4BB") (pin "1") (pinfunction "1_1") (pintype "passive"))
      (node (ref "C4BC") (pin "1") (pinfunction "1_1") (pintype "passive"))
      (node (ref "C4BD") (pin "1") (pinfunction "1_1") (pintype "passive"))
      (node (ref "C4BE") (pin "1") (pinfunction "1_1") (pintype "passive"))
      (node (ref "C4BS") (pin "1") (pinfunction "1_1") (pintype "passive"))
      (node (ref "C4C0") (pin "1") (pinfunction "1_1") (pintype "passive"))
      (node (ref "C4C1") (pin "1") (pinfunction "1_1") (pintype "passive"))
      (node (ref "C4C2") (pin "1") (pinfunction "1_1") (pintype "passive"))
      (node (ref "C4C3") (pin "1") (pinfunction "1_1") (pintype "passive"))
      (node (ref "C4C4") (pin "1") (pinfunction "1_1") (pintype "passive"))
      (node (ref "C4C5") (pin "1") (pinfunction "1_1") (pintype "passive"))
      (node (ref "C4C6") (pin "1") (pinfunction "1_1") (pintype "passive"))
      (node (ref "C4C7") (pin "1") (pinfunction "1_1") (pintype "passive"))
      (node (ref "C4C8") (pin "1") (pinfunction "1_1") (pintype "passive"))
      (node (ref "C4C9") (pin "1") (pinfunction "1_1") (pintype "passive"))
      (node (ref "C4CA") (pin "1") (pinfunction "1_1") (pintype "passive"))
      (node (ref "C4CB") (pin "1") (pinfunction "1_1") (pintype "passive"))
      (node (ref "C4CC") (pin "1") (pinfunction "1_1") (pintype "passive"))
      (node (ref "C4CD") (pin "1") (pinfunction "1_1") (pintype "passive"))
      (node (ref "C4CE") (pin "1") (pinfunction "1_1") (pintype "passive"))
      (node (ref "C4CS") (pin "1") (pinfunction "1_1") (pintype "passive"))
      (node (ref "C4D0") (pin "1") (pinfunction "1_1") (pintype "passive"))
      (node (ref "C4D1") (pin "1") (pinfunction "1_1") (pintype "passive"))
      (node (ref "C4D2") (pin "1") (pinfunction "1_1") (pintype "passive"))
      (node (ref "C4D3") (pin "1") (pinfunction "1_1") (pintype "passive"))
      (node (ref "C4D4") (pin "1") (pinfunction "1_1") (pintype "passive"))
      (node (ref "C4D5") (pin "1") (pinfunction "1_1") (pintype "passive"))
      (node (ref "C4D6") (pin "1") (pinfunction "1_1") (pintype "passive"))
      (node (ref "C4D7") (pin "1") (pinfunction "1_1") (pintype "passive"))
      (node (ref "C4D8") (pin "1") (pinfunction "1_1") (pintype "passive"))
      (node (ref "C4D9") (pin "1") (pinfunction "1_1") (pintype "passive"))
      (node (ref "C4DA") (pin "1") (pinfunction "1_1") (pintype "passive"))
      (node (ref "C4DB") (pin "1") (pinfunction "1_1") (pintype "passive"))
      (node (ref "C4DC") (pin "1") (pinfunction "1_1") (pintype "passive"))
      (node (ref "C4DD") (pin "1") (pinfunction "1_1") (pintype "passive"))
      (node (ref "C4DE") (pin "1") (pinfunction "1_1") (pintype "passive"))
      (node (ref "C4DS") (pin "1") (pinfunction "1_1") (pintype "passive"))
      (node (ref "C4E0") (pin "1") (pinfunction "1_1") (pintype "passive"))
      (node (ref "C4E1") (pin "1") (pinfunction "1_1") (pintype "passive"))
      (node (ref "C4E2") (pin "1") (pinfunction "1_1") (pintype "passive"))
      (node (ref "C4E3") (pin "1") (pinfunction "1_1") (pintype "passive"))
      (node (ref "C4E4") (pin "1") (pinfunction "1_1") (pintype "passive"))
      (node (ref "C4E5") (pin "1") (pinfunction "1_1") (pintype "passive"))
      (node (ref "C4E6") (pin "1") (pinfunction "1_1") (pintype "passive"))
      (node (ref "C4E7") (pin "1") (pinfunction "1_1") (pintype "passive"))
      (node (ref "C4E8") (pin "1") (pinfunction "1_1") (pintype "passive"))
      (node (ref "C4E9") (pin "1") (pinfunction "1_1") (pintype "passive"))
      (node (ref "C4EA") (pin "1") (pinfunction "1_1") (pintype "passive"))
      (node (ref "C4EB") (pin "1") (pinfunction "1_1") (pintype "passive"))
      (node (ref "C4EC") (pin "1") (pinfunction "1_1") (pintype "passive"))
      (node (ref "C4ED") (pin "1") (pinfunction "1_1") (pintype "passive"))
      (node (ref "C4EE") (pin "1") (pinfunction "1_1") (pintype "passive"))
      (node (ref "C4ES") (pin "1") (pinfunction "1_1") (pintype "passive"))
      (node (ref "C4F0") (pin "1") (pinfunction "1_1") (pintype "passive"))
      (node (ref "C4F1") (pin "1") (pinfunction "1_1") (pintype "passive"))
      (node (ref "C4F2") (pin "1") (pinfunction "1_1") (pintype "passive"))
      (node (ref "C4F3") (pin "1") (pinfunction "1_1") (pintype "passive"))
      (node (ref "C4F4") (pin "1") (pinfunction "1_1") (pintype "passive"))
      (node (ref "C4F5") (pin "1") (pinfunction "1_1") (pintype "passive"))
      (node (ref "C4F6") (pin "1") (pinfunction "1_1") (pintype "passive"))
      (node (ref "C4F7") (pin "1") (pinfunction "1_1") (pintype "passive"))
      (node (ref "C4F8") (pin "1") (pinfunction "1_1") (pintype "passive"))
      (node (ref "C4F9") (pin "1") (pinfunction "1_1") (pintype "passive"))
      (node (ref "C4FA") (pin "1") (pinfunction "1_1") (pintype "passive"))
      (node (ref "C4FB") (pin "1") (pinfunction "1_1") (pintype "passive"))
      (node (ref "C4FC") (pin "1") (pinfunction "1_1") (pintype "passive"))
      (node (ref "C4FD") (pin "1") (pinfunction "1_1") (pintype "passive"))
      (node (ref "C4FE") (pin "1") (pinfunction "1_1") (pintype "passive"))
      (node (ref "C4FS") (pin "1") (pinfunction "1_1") (pintype "passive"))
      (node (ref "C4GS") (pin "1") (pinfunction "1_1") (pintype "passive"))
      (node (ref "C4HS") (pin "1") (pinfunction "1_1") (pintype "passive"))
      (node (ref "C4IS") (pin "1") (pinfunction "1_1") (pintype "passive"))
      (node (ref "C4JS") (pin "1") (pinfunction "1_1") (pintype "passive"))
      (node (ref "C4KS") (pin "1") (pinfunction "1_1") (pintype "passive"))
      (node (ref "C4LS") (pin "1") (pinfunction "1_1") (pintype "passive"))
      (node (ref "C4MS") (pin "1") (pinfunction "1_1") (pintype "passive"))
      (node (ref "C4NS") (pin "1") (pinfunction "1_1") (pintype "passive"))
      (node (ref "C4OS") (pin "1") (pinfunction "1_1") (pintype "passive"))
      (node (ref "C4PS") (pin "1") (pinfunction "1_1") (pintype "passive"))
      (node (ref "C4QS") (pin "1") (pinfunction "1_1") (pintype "passive"))
      (node (ref "C4RS") (pin "1") (pinfunction "1_1") (pintype "passive"))
      (node (ref "C4SS") (pin "1") (pinfunction "1_1") (pintype "passive"))
      (node (ref "C4TS") (pin "1") (pinfunction "1_1") (pintype "passive"))
      (node (ref "C4US") (pin "1") (pinfunction "1_1") (pintype "passive"))
      (node (ref "C4VS") (pin "1") (pinfunction "1_1") (pintype "passive"))
      (node (ref "L01") (pin "2") (pinfunction "2_2") (pintype "passive"))
      (node (ref "R01F") (pin "2") (pinfunction "2_2") (pintype "passive"))
      (node (ref "U40") (pin "13") (pinfunction "13.IOREF_13") (pintype "passive"))
      (node (ref "U40") (pin "14") (pinfunction "14.VDD_14") (pintype "passive"))
      (node (ref "U40") (pin "15") (pinfunction "15.VDD_15") (pintype "passive"))
      (node (ref "U40") (pin "16") (pinfunction "16.VDD_16") (pintype "passive"))
      (node (ref "U40") (pin "17") (pinfunction "17.VDD_17") (pintype "passive"))
      (node (ref "U40") (pin "18") (pinfunction "18.VDD_18") (pintype "passive"))
      (node (ref "U40") (pin "19") (pinfunction "19.VDD_19") (pintype "passive"))
      (node (ref "U40") (pin "20") (pinfunction "20.VDD_20") (pintype "passive"))
      (node (ref "U40") (pin "21") (pinfunction "21.VDD_21") (pintype "passive"))
      (node (ref "U40") (pin "22") (pinfunction "22.VDD_22") (pintype "passive"))
      (node (ref "U40") (pin "23") (pinfunction "23.VDD_23") (pintype "passive"))
      (node (ref "U40") (pin "24") (pinfunction "24.VDD_24") (pintype "passive"))
      (node (ref "U40") (pin "25") (pinfunction "25.VDD_25") (pintype "passive"))
      (node (ref "U40") (pin "26") (pinfunction "26.VDD_26") (pintype "passive"))
      (node (ref "U40") (pin "27") (pinfunction "27.VDD_27") (pintype "passive"))
      (node (ref "U40") (pin "28") (pinfunction "28.VDD_28") (pintype "passive"))
      (node (ref "U40") (pin "29") (pinfunction "29.VDD_29") (pintype "passive"))
      (node (ref "U40") (pin "30") (pinfunction "30.VDD_30") (pintype "passive"))
      (node (ref "U40") (pin "31") (pinfunction "31.VDD_31") (pintype "passive"))
      (node (ref "U40") (pin "32") (pinfunction "32.VDD_32") (pintype "passive"))
      (node (ref "U40") (pin "33") (pinfunction "33.VDD_33") (pintype "passive"))
      (node (ref "U40") (pin "34") (pinfunction "34.VDD_34") (pintype "passive"))
      (node (ref "U40") (pin "35") (pinfunction "35.VDD_35") (pintype "passive"))
      (node (ref "U40") (pin "36") (pinfunction "36.VDD_36") (pintype "passive"))
      (node (ref "U40") (pin "37") (pinfunction "37.VDD_37") (pintype "passive"))
      (node (ref "U40") (pin "38") (pinfunction "38.VDD_38") (pintype "passive"))
      (node (ref "U40") (pin "39") (pinfunction "39.VDD_39") (pintype "passive"))
      (node (ref "U40") (pin "40") (pinfunction "40.VDD_40") (pintype "passive"))
      (node (ref "U40") (pin "41") (pinfunction "41.VDD_41") (pintype "passive"))
      (node (ref "U40") (pin "42") (pinfunction "42.VDD_42") (pintype "passive"))
      (node (ref "U40") (pin "43") (pinfunction "43.VDD_43") (pintype "passive"))
      (node (ref "U40") (pin "44") (pinfunction "44.VDD_44") (pintype "passive"))
      (node (ref "U40") (pin "45") (pinfunction "45.VDD_45") (pintype "passive"))
      (node (ref "U40") (pin "46") (pinfunction "46.VDD_46") (pintype "passive"))
      (node (ref "U40") (pin "47") (pinfunction "47.VDD_47") (pintype "passive"))
      (node (ref "U40") (pin "48") (pinfunction "48.VDD_48") (pintype "passive"))
      (node (ref "U41") (pin "13") (pinfunction "13.IOREF_13") (pintype "passive"))
      (node (ref "U41") (pin "14") (pinfunction "14.VDD_14") (pintype "passive"))
      (node (ref "U41") (pin "15") (pinfunction "15.VDD_15") (pintype "passive"))
      (node (ref "U41") (pin "16") (pinfunction "16.VDD_16") (pintype "passive"))
      (node (ref "U41") (pin "17") (pinfunction "17.VDD_17") (pintype "passive"))
      (node (ref "U41") (pin "18") (pinfunction "18.VDD_18") (pintype "passive"))
      (node (ref "U41") (pin "19") (pinfunction "19.VDD_19") (pintype "passive"))
      (node (ref "U41") (pin "20") (pinfunction "20.VDD_20") (pintype "passive"))
      (node (ref "U41") (pin "21") (pinfunction "21.VDD_21") (pintype "passive"))
      (node (ref "U41") (pin "22") (pinfunction "22.VDD_22") (pintype "passive"))
      (node (ref "U41") (pin "23") (pinfunction "23.VDD_23") (pintype "passive"))
      (node (ref "U41") (pin "24") (pinfunction "24.VDD_24") (pintype "passive"))
      (node (ref "U41") (pin "25") (pinfunction "25.VDD_25") (pintype "passive"))
      (node (ref "U41") (pin "26") (pinfunction "26.VDD_26") (pintype "passive"))
      (node (ref "U41") (pin "27") (pinfunction "27.VDD_27") (pintype "passive"))
      (node (ref "U41") (pin "28") (pinfunction "28.VDD_28") (pintype "passive"))
      (node (ref "U41") (pin "29") (pinfunction "29.VDD_29") (pintype "passive"))
      (node (ref "U41") (pin "30") (pinfunction "30.VDD_30") (pintype "passive"))
      (node (ref "U41") (pin "31") (pinfunction "31.VDD_31") (pintype "passive"))
      (node (ref "U41") (pin "32") (pinfunction "32.VDD_32") (pintype "passive"))
      (node (ref "U41") (pin "33") (pinfunction "33.VDD_33") (pintype "passive"))
      (node (ref "U41") (pin "34") (pinfunction "34.VDD_34") (pintype "passive"))
      (node (ref "U41") (pin "35") (pinfunction "35.VDD_35") (pintype "passive"))
      (node (ref "U41") (pin "36") (pinfunction "36.VDD_36") (pintype "passive"))
      (node (ref "U41") (pin "37") (pinfunction "37.VDD_37") (pintype "passive"))
      (node (ref "U41") (pin "38") (pinfunction "38.VDD_38") (pintype "passive"))
      (node (ref "U41") (pin "39") (pinfunction "39.VDD_39") (pintype "passive"))
      (node (ref "U41") (pin "40") (pinfunction "40.VDD_40") (pintype "passive"))
      (node (ref "U41") (pin "41") (pinfunction "41.VDD_41") (pintype "passive"))
      (node (ref "U41") (pin "42") (pinfunction "42.VDD_42") (pintype "passive"))
      (node (ref "U41") (pin "43") (pinfunction "43.VDD_43") (pintype "passive"))
      (node (ref "U41") (pin "44") (pinfunction "44.VDD_44") (pintype "passive"))
      (node (ref "U41") (pin "45") (pinfunction "45.VDD_45") (pintype "passive"))
      (node (ref "U41") (pin "46") (pinfunction "46.VDD_46") (pintype "passive"))
      (node (ref "U41") (pin "47") (pinfunction "47.VDD_47") (pintype "passive"))
      (node (ref "U41") (pin "48") (pinfunction "48.VDD_48") (pintype "passive"))
      (node (ref "U42") (pin "13") (pinfunction "13.IOREF_13") (pintype "passive"))
      (node (ref "U42") (pin "14") (pinfunction "14.VDD_14") (pintype "passive"))
      (node (ref "U42") (pin "15") (pinfunction "15.VDD_15") (pintype "passive"))
      (node (ref "U42") (pin "16") (pinfunction "16.VDD_16") (pintype "passive"))
      (node (ref "U42") (pin "17") (pinfunction "17.VDD_17") (pintype "passive"))
      (node (ref "U42") (pin "18") (pinfunction "18.VDD_18") (pintype "passive"))
      (node (ref "U42") (pin "19") (pinfunction "19.VDD_19") (pintype "passive"))
      (node (ref "U42") (pin "20") (pinfunction "20.VDD_20") (pintype "passive"))
      (node (ref "U42") (pin "21") (pinfunction "21.VDD_21") (pintype "passive"))
      (node (ref "U42") (pin "22") (pinfunction "22.VDD_22") (pintype "passive"))
      (node (ref "U42") (pin "23") (pinfunction "23.VDD_23") (pintype "passive"))
      (node (ref "U42") (pin "24") (pinfunction "24.VDD_24") (pintype "passive"))
      (node (ref "U42") (pin "25") (pinfunction "25.VDD_25") (pintype "passive"))
      (node (ref "U42") (pin "26") (pinfunction "26.VDD_26") (pintype "passive"))
      (node (ref "U42") (pin "27") (pinfunction "27.VDD_27") (pintype "passive"))
      (node (ref "U42") (pin "28") (pinfunction "28.VDD_28") (pintype "passive"))
      (node (ref "U42") (pin "29") (pinfunction "29.VDD_29") (pintype "passive"))
      (node (ref "U42") (pin "30") (pinfunction "30.VDD_30") (pintype "passive"))
      (node (ref "U42") (pin "31") (pinfunction "31.VDD_31") (pintype "passive"))
      (node (ref "U42") (pin "32") (pinfunction "32.VDD_32") (pintype "passive"))
      (node (ref "U42") (pin "33") (pinfunction "33.VDD_33") (pintype "passive"))
      (node (ref "U42") (pin "34") (pinfunction "34.VDD_34") (pintype "passive"))
      (node (ref "U42") (pin "35") (pinfunction "35.VDD_35") (pintype "passive"))
      (node (ref "U42") (pin "36") (pinfunction "36.VDD_36") (pintype "passive"))
      (node (ref "U42") (pin "37") (pinfunction "37.VDD_37") (pintype "passive"))
      (node (ref "U42") (pin "38") (pinfunction "38.VDD_38") (pintype "passive"))
      (node (ref "U42") (pin "39") (pinfunction "39.VDD_39") (pintype "passive"))
      (node (ref "U42") (pin "40") (pinfunction "40.VDD_40") (pintype "passive"))
      (node (ref "U42") (pin "41") (pinfunction "41.VDD_41") (pintype "passive"))
      (node (ref "U42") (pin "42") (pinfunction "42.VDD_42") (pintype "passive"))
      (node (ref "U42") (pin "43") (pinfunction "43.VDD_43") (pintype "passive"))
      (node (ref "U42") (pin "44") (pinfunction "44.VDD_44") (pintype "passive"))
      (node (ref "U42") (pin "45") (pinfunction "45.VDD_45") (pintype "passive"))
      (node (ref "U42") (pin "46") (pinfunction "46.VDD_46") (pintype "passive"))
      (node (ref "U42") (pin "47") (pinfunction "47.VDD_47") (pintype "passive"))
      (node (ref "U42") (pin "48") (pinfunction "48.VDD_48") (pintype "passive"))
      (node (ref "U43") (pin "13") (pinfunction "13.IOREF_13") (pintype "passive"))
      (node (ref "U43") (pin "14") (pinfunction "14.VDD_14") (pintype "passive"))
      (node (ref "U43") (pin "15") (pinfunction "15.VDD_15") (pintype "passive"))
      (node (ref "U43") (pin "16") (pinfunction "16.VDD_16") (pintype "passive"))
      (node (ref "U43") (pin "17") (pinfunction "17.VDD_17") (pintype "passive"))
      (node (ref "U43") (pin "18") (pinfunction "18.VDD_18") (pintype "passive"))
      (node (ref "U43") (pin "19") (pinfunction "19.VDD_19") (pintype "passive"))
      (node (ref "U43") (pin "20") (pinfunction "20.VDD_20") (pintype "passive"))
      (node (ref "U43") (pin "21") (pinfunction "21.VDD_21") (pintype "passive"))
      (node (ref "U43") (pin "22") (pinfunction "22.VDD_22") (pintype "passive"))
      (node (ref "U43") (pin "23") (pinfunction "23.VDD_23") (pintype "passive"))
      (node (ref "U43") (pin "24") (pinfunction "24.VDD_24") (pintype "passive"))
      (node (ref "U43") (pin "25") (pinfunction "25.VDD_25") (pintype "passive"))
      (node (ref "U43") (pin "26") (pinfunction "26.VDD_26") (pintype "passive"))
      (node (ref "U43") (pin "27") (pinfunction "27.VDD_27") (pintype "passive"))
      (node (ref "U43") (pin "28") (pinfunction "28.VDD_28") (pintype "passive"))
      (node (ref "U43") (pin "29") (pinfunction "29.VDD_29") (pintype "passive"))
      (node (ref "U43") (pin "30") (pinfunction "30.VDD_30") (pintype "passive"))
      (node (ref "U43") (pin "31") (pinfunction "31.VDD_31") (pintype "passive"))
      (node (ref "U43") (pin "32") (pinfunction "32.VDD_32") (pintype "passive"))
      (node (ref "U43") (pin "33") (pinfunction "33.VDD_33") (pintype "passive"))
      (node (ref "U43") (pin "34") (pinfunction "34.VDD_34") (pintype "passive"))
      (node (ref "U43") (pin "35") (pinfunction "35.VDD_35") (pintype "passive"))
      (node (ref "U43") (pin "36") (pinfunction "36.VDD_36") (pintype "passive"))
      (node (ref "U43") (pin "37") (pinfunction "37.VDD_37") (pintype "passive"))
      (node (ref "U43") (pin "38") (pinfunction "38.VDD_38") (pintype "passive"))
      (node (ref "U43") (pin "39") (pinfunction "39.VDD_39") (pintype "passive"))
      (node (ref "U43") (pin "40") (pinfunction "40.VDD_40") (pintype "passive"))
      (node (ref "U43") (pin "41") (pinfunction "41.VDD_41") (pintype "passive"))
      (node (ref "U43") (pin "42") (pinfunction "42.VDD_42") (pintype "passive"))
      (node (ref "U43") (pin "43") (pinfunction "43.VDD_43") (pintype "passive"))
      (node (ref "U43") (pin "44") (pinfunction "44.VDD_44") (pintype "passive"))
      (node (ref "U43") (pin "45") (pinfunction "45.VDD_45") (pintype "passive"))
      (node (ref "U43") (pin "46") (pinfunction "46.VDD_46") (pintype "passive"))
      (node (ref "U43") (pin "47") (pinfunction "47.VDD_47") (pintype "passive"))
      (node (ref "U43") (pin "48") (pinfunction "48.VDD_48") (pintype "passive"))
      (node (ref "U44") (pin "13") (pinfunction "13.IOREF_13") (pintype "passive"))
      (node (ref "U44") (pin "14") (pinfunction "14.VDD_14") (pintype "passive"))
      (node (ref "U44") (pin "15") (pinfunction "15.VDD_15") (pintype "passive"))
      (node (ref "U44") (pin "16") (pinfunction "16.VDD_16") (pintype "passive"))
      (node (ref "U44") (pin "17") (pinfunction "17.VDD_17") (pintype "passive"))
      (node (ref "U44") (pin "18") (pinfunction "18.VDD_18") (pintype "passive"))
      (node (ref "U44") (pin "19") (pinfunction "19.VDD_19") (pintype "passive"))
      (node (ref "U44") (pin "20") (pinfunction "20.VDD_20") (pintype "passive"))
      (node (ref "U44") (pin "21") (pinfunction "21.VDD_21") (pintype "passive"))
      (node (ref "U44") (pin "22") (pinfunction "22.VDD_22") (pintype "passive"))
      (node (ref "U44") (pin "23") (pinfunction "23.VDD_23") (pintype "passive"))
      (node (ref "U44") (pin "24") (pinfunction "24.VDD_24") (pintype "passive"))
      (node (ref "U44") (pin "25") (pinfunction "25.VDD_25") (pintype "passive"))
      (node (ref "U44") (pin "26") (pinfunction "26.VDD_26") (pintype "passive"))
      (node (ref "U44") (pin "27") (pinfunction "27.VDD_27") (pintype "passive"))
      (node (ref "U44") (pin "28") (pinfunction "28.VDD_28") (pintype "passive"))
      (node (ref "U44") (pin "29") (pinfunction "29.VDD_29") (pintype "passive"))
      (node (ref "U44") (pin "30") (pinfunction "30.VDD_30") (pintype "passive"))
      (node (ref "U44") (pin "31") (pinfunction "31.VDD_31") (pintype "passive"))
      (node (ref "U44") (pin "32") (pinfunction "32.VDD_32") (pintype "passive"))
      (node (ref "U44") (pin "33") (pinfunction "33.VDD_33") (pintype "passive"))
      (node (ref "U44") (pin "34") (pinfunction "34.VDD_34") (pintype "passive"))
      (node (ref "U44") (pin "35") (pinfunction "35.VDD_35") (pintype "passive"))
      (node (ref "U44") (pin "36") (pinfunction "36.VDD_36") (pintype "passive"))
      (node (ref "U44") (pin "37") (pinfunction "37.VDD_37") (pintype "passive"))
      (node (ref "U44") (pin "38") (pinfunction "38.VDD_38") (pintype "passive"))
      (node (ref "U44") (pin "39") (pinfunction "39.VDD_39") (pintype "passive"))
      (node (ref "U44") (pin "40") (pinfunction "40.VDD_40") (pintype "passive"))
      (node (ref "U44") (pin "41") (pinfunction "41.VDD_41") (pintype "passive"))
      (node (ref "U44") (pin "42") (pinfunction "42.VDD_42") (pintype "passive"))
      (node (ref "U44") (pin "43") (pinfunction "43.VDD_43") (pintype "passive"))
      (node (ref "U44") (pin "44") (pinfunction "44.VDD_44") (pintype "passive"))
      (node (ref "U44") (pin "45") (pinfunction "45.VDD_45") (pintype "passive"))
      (node (ref "U44") (pin "46") (pinfunction "46.VDD_46") (pintype "passive"))
      (node (ref "U44") (pin "47") (pinfunction "47.VDD_47") (pintype "passive"))
      (node (ref "U44") (pin "48") (pinfunction "48.VDD_48") (pintype "passive"))
      (node (ref "U45") (pin "13") (pinfunction "13.IOREF_13") (pintype "passive"))
      (node (ref "U45") (pin "14") (pinfunction "14.VDD_14") (pintype "passive"))
      (node (ref "U45") (pin "15") (pinfunction "15.VDD_15") (pintype "passive"))
      (node (ref "U45") (pin "16") (pinfunction "16.VDD_16") (pintype "passive"))
      (node (ref "U45") (pin "17") (pinfunction "17.VDD_17") (pintype "passive"))
      (node (ref "U45") (pin "18") (pinfunction "18.VDD_18") (pintype "passive"))
      (node (ref "U45") (pin "19") (pinfunction "19.VDD_19") (pintype "passive"))
      (node (ref "U45") (pin "20") (pinfunction "20.VDD_20") (pintype "passive"))
      (node (ref "U45") (pin "21") (pinfunction "21.VDD_21") (pintype "passive"))
      (node (ref "U45") (pin "22") (pinfunction "22.VDD_22") (pintype "passive"))
      (node (ref "U45") (pin "23") (pinfunction "23.VDD_23") (pintype "passive"))
      (node (ref "U45") (pin "24") (pinfunction "24.VDD_24") (pintype "passive"))
      (node (ref "U45") (pin "25") (pinfunction "25.VDD_25") (pintype "passive"))
      (node (ref "U45") (pin "26") (pinfunction "26.VDD_26") (pintype "passive"))
      (node (ref "U45") (pin "27") (pinfunction "27.VDD_27") (pintype "passive"))
      (node (ref "U45") (pin "28") (pinfunction "28.VDD_28") (pintype "passive"))
      (node (ref "U45") (pin "29") (pinfunction "29.VDD_29") (pintype "passive"))
      (node (ref "U45") (pin "30") (pinfunction "30.VDD_30") (pintype "passive"))
      (node (ref "U45") (pin "31") (pinfunction "31.VDD_31") (pintype "passive"))
      (node (ref "U45") (pin "32") (pinfunction "32.VDD_32") (pintype "passive"))
      (node (ref "U45") (pin "33") (pinfunction "33.VDD_33") (pintype "passive"))
      (node (ref "U45") (pin "34") (pinfunction "34.VDD_34") (pintype "passive"))
      (node (ref "U45") (pin "35") (pinfunction "35.VDD_35") (pintype "passive"))
      (node (ref "U45") (pin "36") (pinfunction "36.VDD_36") (pintype "passive"))
      (node (ref "U45") (pin "37") (pinfunction "37.VDD_37") (pintype "passive"))
      (node (ref "U45") (pin "38") (pinfunction "38.VDD_38") (pintype "passive"))
      (node (ref "U45") (pin "39") (pinfunction "39.VDD_39") (pintype "passive"))
      (node (ref "U45") (pin "40") (pinfunction "40.VDD_40") (pintype "passive"))
      (node (ref "U45") (pin "41") (pinfunction "41.VDD_41") (pintype "passive"))
      (node (ref "U45") (pin "42") (pinfunction "42.VDD_42") (pintype "passive"))
      (node (ref "U45") (pin "43") (pinfunction "43.VDD_43") (pintype "passive"))
      (node (ref "U45") (pin "44") (pinfunction "44.VDD_44") (pintype "passive"))
      (node (ref "U45") (pin "45") (pinfunction "45.VDD_45") (pintype "passive"))
      (node (ref "U45") (pin "46") (pinfunction "46.VDD_46") (pintype "passive"))
      (node (ref "U45") (pin "47") (pinfunction "47.VDD_47") (pintype "passive"))
      (node (ref "U45") (pin "48") (pinfunction "48.VDD_48") (pintype "passive"))
      (node (ref "U46") (pin "13") (pinfunction "13.IOREF_13") (pintype "passive"))
      (node (ref "U46") (pin "14") (pinfunction "14.VDD_14") (pintype "passive"))
      (node (ref "U46") (pin "15") (pinfunction "15.VDD_15") (pintype "passive"))
      (node (ref "U46") (pin "16") (pinfunction "16.VDD_16") (pintype "passive"))
      (node (ref "U46") (pin "17") (pinfunction "17.VDD_17") (pintype "passive"))
      (node (ref "U46") (pin "18") (pinfunction "18.VDD_18") (pintype "passive"))
      (node (ref "U46") (pin "19") (pinfunction "19.VDD_19") (pintype "passive"))
      (node (ref "U46") (pin "20") (pinfunction "20.VDD_20") (pintype "passive"))
      (node (ref "U46") (pin "21") (pinfunction "21.VDD_21") (pintype "passive"))
      (node (ref "U46") (pin "22") (pinfunction "22.VDD_22") (pintype "passive"))
      (node (ref "U46") (pin "23") (pinfunction "23.VDD_23") (pintype "passive"))
      (node (ref "U46") (pin "24") (pinfunction "24.VDD_24") (pintype "passive"))
      (node (ref "U46") (pin "25") (pinfunction "25.VDD_25") (pintype "passive"))
      (node (ref "U46") (pin "26") (pinfunction "26.VDD_26") (pintype "passive"))
      (node (ref "U46") (pin "27") (pinfunction "27.VDD_27") (pintype "passive"))
      (node (ref "U46") (pin "28") (pinfunction "28.VDD_28") (pintype "passive"))
      (node (ref "U46") (pin "29") (pinfunction "29.VDD_29") (pintype "passive"))
      (node (ref "U46") (pin "30") (pinfunction "30.VDD_30") (pintype "passive"))
      (node (ref "U46") (pin "31") (pinfunction "31.VDD_31") (pintype "passive"))
      (node (ref "U46") (pin "32") (pinfunction "32.VDD_32") (pintype "passive"))
      (node (ref "U46") (pin "33") (pinfunction "33.VDD_33") (pintype "passive"))
      (node (ref "U46") (pin "34") (pinfunction "34.VDD_34") (pintype "passive"))
      (node (ref "U46") (pin "35") (pinfunction "35.VDD_35") (pintype "passive"))
      (node (ref "U46") (pin "36") (pinfunction "36.VDD_36") (pintype "passive"))
      (node (ref "U46") (pin "37") (pinfunction "37.VDD_37") (pintype "passive"))
      (node (ref "U46") (pin "38") (pinfunction "38.VDD_38") (pintype "passive"))
      (node (ref "U46") (pin "39") (pinfunction "39.VDD_39") (pintype "passive"))
      (node (ref "U46") (pin "40") (pinfunction "40.VDD_40") (pintype "passive"))
      (node (ref "U46") (pin "41") (pinfunction "41.VDD_41") (pintype "passive"))
      (node (ref "U46") (pin "42") (pinfunction "42.VDD_42") (pintype "passive"))
      (node (ref "U46") (pin "43") (pinfunction "43.VDD_43") (pintype "passive"))
      (node (ref "U46") (pin "44") (pinfunction "44.VDD_44") (pintype "passive"))
      (node (ref "U46") (pin "45") (pinfunction "45.VDD_45") (pintype "passive"))
      (node (ref "U46") (pin "46") (pinfunction "46.VDD_46") (pintype "passive"))
      (node (ref "U46") (pin "47") (pinfunction "47.VDD_47") (pintype "passive"))
      (node (ref "U46") (pin "48") (pinfunction "48.VDD_48") (pintype "passive"))
      (node (ref "U47") (pin "13") (pinfunction "13.IOREF_13") (pintype "passive"))
      (node (ref "U47") (pin "14") (pinfunction "14.VDD_14") (pintype "passive"))
      (node (ref "U47") (pin "15") (pinfunction "15.VDD_15") (pintype "passive"))
      (node (ref "U47") (pin "16") (pinfunction "16.VDD_16") (pintype "passive"))
      (node (ref "U47") (pin "17") (pinfunction "17.VDD_17") (pintype "passive"))
      (node (ref "U47") (pin "18") (pinfunction "18.VDD_18") (pintype "passive"))
      (node (ref "U47") (pin "19") (pinfunction "19.VDD_19") (pintype "passive"))
      (node (ref "U47") (pin "20") (pinfunction "20.VDD_20") (pintype "passive"))
      (node (ref "U47") (pin "21") (pinfunction "21.VDD_21") (pintype "passive"))
      (node (ref "U47") (pin "22") (pinfunction "22.VDD_22") (pintype "passive"))
      (node (ref "U47") (pin "23") (pinfunction "23.VDD_23") (pintype "passive"))
      (node (ref "U47") (pin "24") (pinfunction "24.VDD_24") (pintype "passive"))
      (node (ref "U47") (pin "25") (pinfunction "25.VDD_25") (pintype "passive"))
      (node (ref "U47") (pin "26") (pinfunction "26.VDD_26") (pintype "passive"))
      (node (ref "U47") (pin "27") (pinfunction "27.VDD_27") (pintype "passive"))
      (node (ref "U47") (pin "28") (pinfunction "28.VDD_28") (pintype "passive"))
      (node (ref "U47") (pin "29") (pinfunction "29.VDD_29") (pintype "passive"))
      (node (ref "U47") (pin "30") (pinfunction "30.VDD_30") (pintype "passive"))
      (node (ref "U47") (pin "31") (pinfunction "31.VDD_31") (pintype "passive"))
      (node (ref "U47") (pin "32") (pinfunction "32.VDD_32") (pintype "passive"))
      (node (ref "U47") (pin "33") (pinfunction "33.VDD_33") (pintype "passive"))
      (node (ref "U47") (pin "34") (pinfunction "34.VDD_34") (pintype "passive"))
      (node (ref "U47") (pin "35") (pinfunction "35.VDD_35") (pintype "passive"))
      (node (ref "U47") (pin "36") (pinfunction "36.VDD_36") (pintype "passive"))
      (node (ref "U47") (pin "37") (pinfunction "37.VDD_37") (pintype "passive"))
      (node (ref "U47") (pin "38") (pinfunction "38.VDD_38") (pintype "passive"))
      (node (ref "U47") (pin "39") (pinfunction "39.VDD_39") (pintype "passive"))
      (node (ref "U47") (pin "40") (pinfunction "40.VDD_40") (pintype "passive"))
      (node (ref "U47") (pin "41") (pinfunction "41.VDD_41") (pintype "passive"))
      (node (ref "U47") (pin "42") (pinfunction "42.VDD_42") (pintype "passive"))
      (node (ref "U47") (pin "43") (pinfunction "43.VDD_43") (pintype "passive"))
      (node (ref "U47") (pin "44") (pinfunction "44.VDD_44") (pintype "passive"))
      (node (ref "U47") (pin "45") (pinfunction "45.VDD_45") (pintype "passive"))
      (node (ref "U47") (pin "46") (pinfunction "46.VDD_46") (pintype "passive"))
      (node (ref "U47") (pin "47") (pinfunction "47.VDD_47") (pintype "passive"))
      (node (ref "U47") (pin "48") (pinfunction "48.VDD_48") (pintype "passive"))
      (node (ref "U48") (pin "13") (pinfunction "13.IOREF_13") (pintype "passive"))
      (node (ref "U48") (pin "14") (pinfunction "14.VDD_14") (pintype "passive"))
      (node (ref "U48") (pin "15") (pinfunction "15.VDD_15") (pintype "passive"))
      (node (ref "U48") (pin "16") (pinfunction "16.VDD_16") (pintype "passive"))
      (node (ref "U48") (pin "17") (pinfunction "17.VDD_17") (pintype "passive"))
      (node (ref "U48") (pin "18") (pinfunction "18.VDD_18") (pintype "passive"))
      (node (ref "U48") (pin "19") (pinfunction "19.VDD_19") (pintype "passive"))
      (node (ref "U48") (pin "20") (pinfunction "20.VDD_20") (pintype "passive"))
      (node (ref "U48") (pin "21") (pinfunction "21.VDD_21") (pintype "passive"))
      (node (ref "U48") (pin "22") (pinfunction "22.VDD_22") (pintype "passive"))
      (node (ref "U48") (pin "23") (pinfunction "23.VDD_23") (pintype "passive"))
      (node (ref "U48") (pin "24") (pinfunction "24.VDD_24") (pintype "passive"))
      (node (ref "U48") (pin "25") (pinfunction "25.VDD_25") (pintype "passive"))
      (node (ref "U48") (pin "26") (pinfunction "26.VDD_26") (pintype "passive"))
      (node (ref "U48") (pin "27") (pinfunction "27.VDD_27") (pintype "passive"))
      (node (ref "U48") (pin "28") (pinfunction "28.VDD_28") (pintype "passive"))
      (node (ref "U48") (pin "29") (pinfunction "29.VDD_29") (pintype "passive"))
      (node (ref "U48") (pin "30") (pinfunction "30.VDD_30") (pintype "passive"))
      (node (ref "U48") (pin "31") (pinfunction "31.VDD_31") (pintype "passive"))
      (node (ref "U48") (pin "32") (pinfunction "32.VDD_32") (pintype "passive"))
      (node (ref "U48") (pin "33") (pinfunction "33.VDD_33") (pintype "passive"))
      (node (ref "U48") (pin "34") (pinfunction "34.VDD_34") (pintype "passive"))
      (node (ref "U48") (pin "35") (pinfunction "35.VDD_35") (pintype "passive"))
      (node (ref "U48") (pin "36") (pinfunction "36.VDD_36") (pintype "passive"))
      (node (ref "U48") (pin "37") (pinfunction "37.VDD_37") (pintype "passive"))
      (node (ref "U48") (pin "38") (pinfunction "38.VDD_38") (pintype "passive"))
      (node (ref "U48") (pin "39") (pinfunction "39.VDD_39") (pintype "passive"))
      (node (ref "U48") (pin "40") (pinfunction "40.VDD_40") (pintype "passive"))
      (node (ref "U48") (pin "41") (pinfunction "41.VDD_41") (pintype "passive"))
      (node (ref "U48") (pin "42") (pinfunction "42.VDD_42") (pintype "passive"))
      (node (ref "U48") (pin "43") (pinfunction "43.VDD_43") (pintype "passive"))
      (node (ref "U48") (pin "44") (pinfunction "44.VDD_44") (pintype "passive"))
      (node (ref "U48") (pin "45") (pinfunction "45.VDD_45") (pintype "passive"))
      (node (ref "U48") (pin "46") (pinfunction "46.VDD_46") (pintype "passive"))
      (node (ref "U48") (pin "47") (pinfunction "47.VDD_47") (pintype "passive"))
      (node (ref "U48") (pin "48") (pinfunction "48.VDD_48") (pintype "passive"))
      (node (ref "U49") (pin "13") (pinfunction "13.IOREF_13") (pintype "passive"))
      (node (ref "U49") (pin "14") (pinfunction "14.VDD_14") (pintype "passive"))
      (node (ref "U49") (pin "15") (pinfunction "15.VDD_15") (pintype "passive"))
      (node (ref "U49") (pin "16") (pinfunction "16.VDD_16") (pintype "passive"))
      (node (ref "U49") (pin "17") (pinfunction "17.VDD_17") (pintype "passive"))
      (node (ref "U49") (pin "18") (pinfunction "18.VDD_18") (pintype "passive"))
      (node (ref "U49") (pin "19") (pinfunction "19.VDD_19") (pintype "passive"))
      (node (ref "U49") (pin "20") (pinfunction "20.VDD_20") (pintype "passive"))
      (node (ref "U49") (pin "21") (pinfunction "21.VDD_21") (pintype "passive"))
      (node (ref "U49") (pin "22") (pinfunction "22.VDD_22") (pintype "passive"))
      (node (ref "U49") (pin "23") (pinfunction "23.VDD_23") (pintype "passive"))
      (node (ref "U49") (pin "24") (pinfunction "24.VDD_24") (pintype "passive"))
      (node (ref "U49") (pin "25") (pinfunction "25.VDD_25") (pintype "passive"))
      (node (ref "U49") (pin "26") (pinfunction "26.VDD_26") (pintype "passive"))
      (node (ref "U49") (pin "27") (pinfunction "27.VDD_27") (pintype "passive"))
      (node (ref "U49") (pin "28") (pinfunction "28.VDD_28") (pintype "passive"))
      (node (ref "U49") (pin "29") (pinfunction "29.VDD_29") (pintype "passive"))
      (node (ref "U49") (pin "30") (pinfunction "30.VDD_30") (pintype "passive"))
      (node (ref "U49") (pin "31") (pinfunction "31.VDD_31") (pintype "passive"))
      (node (ref "U49") (pin "32") (pinfunction "32.VDD_32") (pintype "passive"))
      (node (ref "U49") (pin "33") (pinfunction "33.VDD_33") (pintype "passive"))
      (node (ref "U49") (pin "34") (pinfunction "34.VDD_34") (pintype "passive"))
      (node (ref "U49") (pin "35") (pinfunction "35.VDD_35") (pintype "passive"))
      (node (ref "U49") (pin "36") (pinfunction "36.VDD_36") (pintype "passive"))
      (node (ref "U49") (pin "37") (pinfunction "37.VDD_37") (pintype "passive"))
      (node (ref "U49") (pin "38") (pinfunction "38.VDD_38") (pintype "passive"))
      (node (ref "U49") (pin "39") (pinfunction "39.VDD_39") (pintype "passive"))
      (node (ref "U49") (pin "40") (pinfunction "40.VDD_40") (pintype "passive"))
      (node (ref "U49") (pin "41") (pinfunction "41.VDD_41") (pintype "passive"))
      (node (ref "U49") (pin "42") (pinfunction "42.VDD_42") (pintype "passive"))
      (node (ref "U49") (pin "43") (pinfunction "43.VDD_43") (pintype "passive"))
      (node (ref "U49") (pin "44") (pinfunction "44.VDD_44") (pintype "passive"))
      (node (ref "U49") (pin "45") (pinfunction "45.VDD_45") (pintype "passive"))
      (node (ref "U49") (pin "46") (pinfunction "46.VDD_46") (pintype "passive"))
      (node (ref "U49") (pin "47") (pinfunction "47.VDD_47") (pintype "passive"))
      (node (ref "U49") (pin "48") (pinfunction "48.VDD_48") (pintype "passive"))
      (node (ref "U4A") (pin "13") (pinfunction "13.IOREF_13") (pintype "passive"))
      (node (ref "U4A") (pin "14") (pinfunction "14.VDD_14") (pintype "passive"))
      (node (ref "U4A") (pin "15") (pinfunction "15.VDD_15") (pintype "passive"))
      (node (ref "U4A") (pin "16") (pinfunction "16.VDD_16") (pintype "passive"))
      (node (ref "U4A") (pin "17") (pinfunction "17.VDD_17") (pintype "passive"))
      (node (ref "U4A") (pin "18") (pinfunction "18.VDD_18") (pintype "passive"))
      (node (ref "U4A") (pin "19") (pinfunction "19.VDD_19") (pintype "passive"))
      (node (ref "U4A") (pin "20") (pinfunction "20.VDD_20") (pintype "passive"))
      (node (ref "U4A") (pin "21") (pinfunction "21.VDD_21") (pintype "passive"))
      (node (ref "U4A") (pin "22") (pinfunction "22.VDD_22") (pintype "passive"))
      (node (ref "U4A") (pin "23") (pinfunction "23.VDD_23") (pintype "passive"))
      (node (ref "U4A") (pin "24") (pinfunction "24.VDD_24") (pintype "passive"))
      (node (ref "U4A") (pin "25") (pinfunction "25.VDD_25") (pintype "passive"))
      (node (ref "U4A") (pin "26") (pinfunction "26.VDD_26") (pintype "passive"))
      (node (ref "U4A") (pin "27") (pinfunction "27.VDD_27") (pintype "passive"))
      (node (ref "U4A") (pin "28") (pinfunction "28.VDD_28") (pintype "passive"))
      (node (ref "U4A") (pin "29") (pinfunction "29.VDD_29") (pintype "passive"))
      (node (ref "U4A") (pin "30") (pinfunction "30.VDD_30") (pintype "passive"))
      (node (ref "U4A") (pin "31") (pinfunction "31.VDD_31") (pintype "passive"))
      (node (ref "U4A") (pin "32") (pinfunction "32.VDD_32") (pintype "passive"))
      (node (ref "U4A") (pin "33") (pinfunction "33.VDD_33") (pintype "passive"))
      (node (ref "U4A") (pin "34") (pinfunction "34.VDD_34") (pintype "passive"))
      (node (ref "U4A") (pin "35") (pinfunction "35.VDD_35") (pintype "passive"))
      (node (ref "U4A") (pin "36") (pinfunction "36.VDD_36") (pintype "passive"))
      (node (ref "U4A") (pin "37") (pinfunction "37.VDD_37") (pintype "passive"))
      (node (ref "U4A") (pin "38") (pinfunction "38.VDD_38") (pintype "passive"))
      (node (ref "U4A") (pin "39") (pinfunction "39.VDD_39") (pintype "passive"))
      (node (ref "U4A") (pin "40") (pinfunction "40.VDD_40") (pintype "passive"))
      (node (ref "U4A") (pin "41") (pinfunction "41.VDD_41") (pintype "passive"))
      (node (ref "U4A") (pin "42") (pinfunction "42.VDD_42") (pintype "passive"))
      (node (ref "U4A") (pin "43") (pinfunction "43.VDD_43") (pintype "passive"))
      (node (ref "U4A") (pin "44") (pinfunction "44.VDD_44") (pintype "passive"))
      (node (ref "U4A") (pin "45") (pinfunction "45.VDD_45") (pintype "passive"))
      (node (ref "U4A") (pin "46") (pinfunction "46.VDD_46") (pintype "passive"))
      (node (ref "U4A") (pin "47") (pinfunction "47.VDD_47") (pintype "passive"))
      (node (ref "U4A") (pin "48") (pinfunction "48.VDD_48") (pintype "passive"))
      (node (ref "U4B") (pin "13") (pinfunction "13.IOREF_13") (pintype "passive"))
      (node (ref "U4B") (pin "14") (pinfunction "14.VDD_14") (pintype "passive"))
      (node (ref "U4B") (pin "15") (pinfunction "15.VDD_15") (pintype "passive"))
      (node (ref "U4B") (pin "16") (pinfunction "16.VDD_16") (pintype "passive"))
      (node (ref "U4B") (pin "17") (pinfunction "17.VDD_17") (pintype "passive"))
      (node (ref "U4B") (pin "18") (pinfunction "18.VDD_18") (pintype "passive"))
      (node (ref "U4B") (pin "19") (pinfunction "19.VDD_19") (pintype "passive"))
      (node (ref "U4B") (pin "20") (pinfunction "20.VDD_20") (pintype "passive"))
      (node (ref "U4B") (pin "21") (pinfunction "21.VDD_21") (pintype "passive"))
      (node (ref "U4B") (pin "22") (pinfunction "22.VDD_22") (pintype "passive"))
      (node (ref "U4B") (pin "23") (pinfunction "23.VDD_23") (pintype "passive"))
      (node (ref "U4B") (pin "24") (pinfunction "24.VDD_24") (pintype "passive"))
      (node (ref "U4B") (pin "25") (pinfunction "25.VDD_25") (pintype "passive"))
      (node (ref "U4B") (pin "26") (pinfunction "26.VDD_26") (pintype "passive"))
      (node (ref "U4B") (pin "27") (pinfunction "27.VDD_27") (pintype "passive"))
      (node (ref "U4B") (pin "28") (pinfunction "28.VDD_28") (pintype "passive"))
      (node (ref "U4B") (pin "29") (pinfunction "29.VDD_29") (pintype "passive"))
      (node (ref "U4B") (pin "30") (pinfunction "30.VDD_30") (pintype "passive"))
      (node (ref "U4B") (pin "31") (pinfunction "31.VDD_31") (pintype "passive"))
      (node (ref "U4B") (pin "32") (pinfunction "32.VDD_32") (pintype "passive"))
      (node (ref "U4B") (pin "33") (pinfunction "33.VDD_33") (pintype "passive"))
      (node (ref "U4B") (pin "34") (pinfunction "34.VDD_34") (pintype "passive"))
      (node (ref "U4B") (pin "35") (pinfunction "35.VDD_35") (pintype "passive"))
      (node (ref "U4B") (pin "36") (pinfunction "36.VDD_36") (pintype "passive"))
      (node (ref "U4B") (pin "37") (pinfunction "37.VDD_37") (pintype "passive"))
      (node (ref "U4B") (pin "38") (pinfunction "38.VDD_38") (pintype "passive"))
      (node (ref "U4B") (pin "39") (pinfunction "39.VDD_39") (pintype "passive"))
      (node (ref "U4B") (pin "40") (pinfunction "40.VDD_40") (pintype "passive"))
      (node (ref "U4B") (pin "41") (pinfunction "41.VDD_41") (pintype "passive"))
      (node (ref "U4B") (pin "42") (pinfunction "42.VDD_42") (pintype "passive"))
      (node (ref "U4B") (pin "43") (pinfunction "43.VDD_43") (pintype "passive"))
      (node (ref "U4B") (pin "44") (pinfunction "44.VDD_44") (pintype "passive"))
      (node (ref "U4B") (pin "45") (pinfunction "45.VDD_45") (pintype "passive"))
      (node (ref "U4B") (pin "46") (pinfunction "46.VDD_46") (pintype "passive"))
      (node (ref "U4B") (pin "47") (pinfunction "47.VDD_47") (pintype "passive"))
      (node (ref "U4B") (pin "48") (pinfunction "48.VDD_48") (pintype "passive"))
      (node (ref "U4C") (pin "13") (pinfunction "13.IOREF_13") (pintype "passive"))
      (node (ref "U4C") (pin "14") (pinfunction "14.VDD_14") (pintype "passive"))
      (node (ref "U4C") (pin "15") (pinfunction "15.VDD_15") (pintype "passive"))
      (node (ref "U4C") (pin "16") (pinfunction "16.VDD_16") (pintype "passive"))
      (node (ref "U4C") (pin "17") (pinfunction "17.VDD_17") (pintype "passive"))
      (node (ref "U4C") (pin "18") (pinfunction "18.VDD_18") (pintype "passive"))
      (node (ref "U4C") (pin "19") (pinfunction "19.VDD_19") (pintype "passive"))
      (node (ref "U4C") (pin "20") (pinfunction "20.VDD_20") (pintype "passive"))
      (node (ref "U4C") (pin "21") (pinfunction "21.VDD_21") (pintype "passive"))
      (node (ref "U4C") (pin "22") (pinfunction "22.VDD_22") (pintype "passive"))
      (node (ref "U4C") (pin "23") (pinfunction "23.VDD_23") (pintype "passive"))
      (node (ref "U4C") (pin "24") (pinfunction "24.VDD_24") (pintype "passive"))
      (node (ref "U4C") (pin "25") (pinfunction "25.VDD_25") (pintype "passive"))
      (node (ref "U4C") (pin "26") (pinfunction "26.VDD_26") (pintype "passive"))
      (node (ref "U4C") (pin "27") (pinfunction "27.VDD_27") (pintype "passive"))
      (node (ref "U4C") (pin "28") (pinfunction "28.VDD_28") (pintype "passive"))
      (node (ref "U4C") (pin "29") (pinfunction "29.VDD_29") (pintype "passive"))
      (node (ref "U4C") (pin "30") (pinfunction "30.VDD_30") (pintype "passive"))
      (node (ref "U4C") (pin "31") (pinfunction "31.VDD_31") (pintype "passive"))
      (node (ref "U4C") (pin "32") (pinfunction "32.VDD_32") (pintype "passive"))
      (node (ref "U4C") (pin "33") (pinfunction "33.VDD_33") (pintype "passive"))
      (node (ref "U4C") (pin "34") (pinfunction "34.VDD_34") (pintype "passive"))
      (node (ref "U4C") (pin "35") (pinfunction "35.VDD_35") (pintype "passive"))
      (node (ref "U4C") (pin "36") (pinfunction "36.VDD_36") (pintype "passive"))
      (node (ref "U4C") (pin "37") (pinfunction "37.VDD_37") (pintype "passive"))
      (node (ref "U4C") (pin "38") (pinfunction "38.VDD_38") (pintype "passive"))
      (node (ref "U4C") (pin "39") (pinfunction "39.VDD_39") (pintype "passive"))
      (node (ref "U4C") (pin "40") (pinfunction "40.VDD_40") (pintype "passive"))
      (node (ref "U4C") (pin "41") (pinfunction "41.VDD_41") (pintype "passive"))
      (node (ref "U4C") (pin "42") (pinfunction "42.VDD_42") (pintype "passive"))
      (node (ref "U4C") (pin "43") (pinfunction "43.VDD_43") (pintype "passive"))
      (node (ref "U4C") (pin "44") (pinfunction "44.VDD_44") (pintype "passive"))
      (node (ref "U4C") (pin "45") (pinfunction "45.VDD_45") (pintype "passive"))
      (node (ref "U4C") (pin "46") (pinfunction "46.VDD_46") (pintype "passive"))
      (node (ref "U4C") (pin "47") (pinfunction "47.VDD_47") (pintype "passive"))
      (node (ref "U4C") (pin "48") (pinfunction "48.VDD_48") (pintype "passive"))
      (node (ref "U4D") (pin "13") (pinfunction "13.IOREF_13") (pintype "passive"))
      (node (ref "U4D") (pin "14") (pinfunction "14.VDD_14") (pintype "passive"))
      (node (ref "U4D") (pin "15") (pinfunction "15.VDD_15") (pintype "passive"))
      (node (ref "U4D") (pin "16") (pinfunction "16.VDD_16") (pintype "passive"))
      (node (ref "U4D") (pin "17") (pinfunction "17.VDD_17") (pintype "passive"))
      (node (ref "U4D") (pin "18") (pinfunction "18.VDD_18") (pintype "passive"))
      (node (ref "U4D") (pin "19") (pinfunction "19.VDD_19") (pintype "passive"))
      (node (ref "U4D") (pin "20") (pinfunction "20.VDD_20") (pintype "passive"))
      (node (ref "U4D") (pin "21") (pinfunction "21.VDD_21") (pintype "passive"))
      (node (ref "U4D") (pin "22") (pinfunction "22.VDD_22") (pintype "passive"))
      (node (ref "U4D") (pin "23") (pinfunction "23.VDD_23") (pintype "passive"))
      (node (ref "U4D") (pin "24") (pinfunction "24.VDD_24") (pintype "passive"))
      (node (ref "U4D") (pin "25") (pinfunction "25.VDD_25") (pintype "passive"))
      (node (ref "U4D") (pin "26") (pinfunction "26.VDD_26") (pintype "passive"))
      (node (ref "U4D") (pin "27") (pinfunction "27.VDD_27") (pintype "passive"))
      (node (ref "U4D") (pin "28") (pinfunction "28.VDD_28") (pintype "passive"))
      (node (ref "U4D") (pin "29") (pinfunction "29.VDD_29") (pintype "passive"))
      (node (ref "U4D") (pin "30") (pinfunction "30.VDD_30") (pintype "passive"))
      (node (ref "U4D") (pin "31") (pinfunction "31.VDD_31") (pintype "passive"))
      (node (ref "U4D") (pin "32") (pinfunction "32.VDD_32") (pintype "passive"))
      (node (ref "U4D") (pin "33") (pinfunction "33.VDD_33") (pintype "passive"))
      (node (ref "U4D") (pin "34") (pinfunction "34.VDD_34") (pintype "passive"))
      (node (ref "U4D") (pin "35") (pinfunction "35.VDD_35") (pintype "passive"))
      (node (ref "U4D") (pin "36") (pinfunction "36.VDD_36") (pintype "passive"))
      (node (ref "U4D") (pin "37") (pinfunction "37.VDD_37") (pintype "passive"))
      (node (ref "U4D") (pin "38") (pinfunction "38.VDD_38") (pintype "passive"))
      (node (ref "U4D") (pin "39") (pinfunction "39.VDD_39") (pintype "passive"))
      (node (ref "U4D") (pin "40") (pinfunction "40.VDD_40") (pintype "passive"))
      (node (ref "U4D") (pin "41") (pinfunction "41.VDD_41") (pintype "passive"))
      (node (ref "U4D") (pin "42") (pinfunction "42.VDD_42") (pintype "passive"))
      (node (ref "U4D") (pin "43") (pinfunction "43.VDD_43") (pintype "passive"))
      (node (ref "U4D") (pin "44") (pinfunction "44.VDD_44") (pintype "passive"))
      (node (ref "U4D") (pin "45") (pinfunction "45.VDD_45") (pintype "passive"))
      (node (ref "U4D") (pin "46") (pinfunction "46.VDD_46") (pintype "passive"))
      (node (ref "U4D") (pin "47") (pinfunction "47.VDD_47") (pintype "passive"))
      (node (ref "U4D") (pin "48") (pinfunction "48.VDD_48") (pintype "passive"))
      (node (ref "U4E") (pin "13") (pinfunction "13.IOREF_13") (pintype "passive"))
      (node (ref "U4E") (pin "14") (pinfunction "14.VDD_14") (pintype "passive"))
      (node (ref "U4E") (pin "15") (pinfunction "15.VDD_15") (pintype "passive"))
      (node (ref "U4E") (pin "16") (pinfunction "16.VDD_16") (pintype "passive"))
      (node (ref "U4E") (pin "17") (pinfunction "17.VDD_17") (pintype "passive"))
      (node (ref "U4E") (pin "18") (pinfunction "18.VDD_18") (pintype "passive"))
      (node (ref "U4E") (pin "19") (pinfunction "19.VDD_19") (pintype "passive"))
      (node (ref "U4E") (pin "20") (pinfunction "20.VDD_20") (pintype "passive"))
      (node (ref "U4E") (pin "21") (pinfunction "21.VDD_21") (pintype "passive"))
      (node (ref "U4E") (pin "22") (pinfunction "22.VDD_22") (pintype "passive"))
      (node (ref "U4E") (pin "23") (pinfunction "23.VDD_23") (pintype "passive"))
      (node (ref "U4E") (pin "24") (pinfunction "24.VDD_24") (pintype "passive"))
      (node (ref "U4E") (pin "25") (pinfunction "25.VDD_25") (pintype "passive"))
      (node (ref "U4E") (pin "26") (pinfunction "26.VDD_26") (pintype "passive"))
      (node (ref "U4E") (pin "27") (pinfunction "27.VDD_27") (pintype "passive"))
      (node (ref "U4E") (pin "28") (pinfunction "28.VDD_28") (pintype "passive"))
      (node (ref "U4E") (pin "29") (pinfunction "29.VDD_29") (pintype "passive"))
      (node (ref "U4E") (pin "30") (pinfunction "30.VDD_30") (pintype "passive"))
      (node (ref "U4E") (pin "31") (pinfunction "31.VDD_31") (pintype "passive"))
      (node (ref "U4E") (pin "32") (pinfunction "32.VDD_32") (pintype "passive"))
      (node (ref "U4E") (pin "33") (pinfunction "33.VDD_33") (pintype "passive"))
      (node (ref "U4E") (pin "34") (pinfunction "34.VDD_34") (pintype "passive"))
      (node (ref "U4E") (pin "35") (pinfunction "35.VDD_35") (pintype "passive"))
      (node (ref "U4E") (pin "36") (pinfunction "36.VDD_36") (pintype "passive"))
      (node (ref "U4E") (pin "37") (pinfunction "37.VDD_37") (pintype "passive"))
      (node (ref "U4E") (pin "38") (pinfunction "38.VDD_38") (pintype "passive"))
      (node (ref "U4E") (pin "39") (pinfunction "39.VDD_39") (pintype "passive"))
      (node (ref "U4E") (pin "40") (pinfunction "40.VDD_40") (pintype "passive"))
      (node (ref "U4E") (pin "41") (pinfunction "41.VDD_41") (pintype "passive"))
      (node (ref "U4E") (pin "42") (pinfunction "42.VDD_42") (pintype "passive"))
      (node (ref "U4E") (pin "43") (pinfunction "43.VDD_43") (pintype "passive"))
      (node (ref "U4E") (pin "44") (pinfunction "44.VDD_44") (pintype "passive"))
      (node (ref "U4E") (pin "45") (pinfunction "45.VDD_45") (pintype "passive"))
      (node (ref "U4E") (pin "46") (pinfunction "46.VDD_46") (pintype "passive"))
      (node (ref "U4E") (pin "47") (pinfunction "47.VDD_47") (pintype "passive"))
      (node (ref "U4E") (pin "48") (pinfunction "48.VDD_48") (pintype "passive"))
      (node (ref "U4F") (pin "13") (pinfunction "13.IOREF_13") (pintype "passive"))
      (node (ref "U4F") (pin "14") (pinfunction "14.VDD_14") (pintype "passive"))
      (node (ref "U4F") (pin "15") (pinfunction "15.VDD_15") (pintype "passive"))
      (node (ref "U4F") (pin "16") (pinfunction "16.VDD_16") (pintype "passive"))
      (node (ref "U4F") (pin "17") (pinfunction "17.VDD_17") (pintype "passive"))
      (node (ref "U4F") (pin "18") (pinfunction "18.VDD_18") (pintype "passive"))
      (node (ref "U4F") (pin "19") (pinfunction "19.VDD_19") (pintype "passive"))
      (node (ref "U4F") (pin "20") (pinfunction "20.VDD_20") (pintype "passive"))
      (node (ref "U4F") (pin "21") (pinfunction "21.VDD_21") (pintype "passive"))
      (node (ref "U4F") (pin "22") (pinfunction "22.VDD_22") (pintype "passive"))
      (node (ref "U4F") (pin "23") (pinfunction "23.VDD_23") (pintype "passive"))
      (node (ref "U4F") (pin "24") (pinfunction "24.VDD_24") (pintype "passive"))
      (node (ref "U4F") (pin "25") (pinfunction "25.VDD_25") (pintype "passive"))
      (node (ref "U4F") (pin "26") (pinfunction "26.VDD_26") (pintype "passive"))
      (node (ref "U4F") (pin "27") (pinfunction "27.VDD_27") (pintype "passive"))
      (node (ref "U4F") (pin "28") (pinfunction "28.VDD_28") (pintype "passive"))
      (node (ref "U4F") (pin "29") (pinfunction "29.VDD_29") (pintype "passive"))
      (node (ref "U4F") (pin "30") (pinfunction "30.VDD_30") (pintype "passive"))
      (node (ref "U4F") (pin "31") (pinfunction "31.VDD_31") (pintype "passive"))
      (node (ref "U4F") (pin "32") (pinfunction "32.VDD_32") (pintype "passive"))
      (node (ref "U4F") (pin "33") (pinfunction "33.VDD_33") (pintype "passive"))
      (node (ref "U4F") (pin "34") (pinfunction "34.VDD_34") (pintype "passive"))
      (node (ref "U4F") (pin "35") (pinfunction "35.VDD_35") (pintype "passive"))
      (node (ref "U4F") (pin "36") (pinfunction "36.VDD_36") (pintype "passive"))
      (node (ref "U4F") (pin "37") (pinfunction "37.VDD_37") (pintype "passive"))
      (node (ref "U4F") (pin "38") (pinfunction "38.VDD_38") (pintype "passive"))
      (node (ref "U4F") (pin "39") (pinfunction "39.VDD_39") (pintype "passive"))
      (node (ref "U4F") (pin "40") (pinfunction "40.VDD_40") (pintype "passive"))
      (node (ref "U4F") (pin "41") (pinfunction "41.VDD_41") (pintype "passive"))
      (node (ref "U4F") (pin "42") (pinfunction "42.VDD_42") (pintype "passive"))
      (node (ref "U4F") (pin "43") (pinfunction "43.VDD_43") (pintype "passive"))
      (node (ref "U4F") (pin "44") (pinfunction "44.VDD_44") (pintype "passive"))
      (node (ref "U4F") (pin "45") (pinfunction "45.VDD_45") (pintype "passive"))
      (node (ref "U4F") (pin "46") (pinfunction "46.VDD_46") (pintype "passive"))
      (node (ref "U4F") (pin "47") (pinfunction "47.VDD_47") (pintype "passive"))
      (node (ref "U4F") (pin "48") (pinfunction "48.VDD_48") (pintype "passive"))
    )
    (net (code "84") (name "VDD_1V8") (class "Default")
      (node (ref "J01") (pin "A10") (pinfunction "10_A10") (pintype "passive"))
      (node (ref "U40") (pin "4") (pinfunction "4.VDD_IO_4") (pintype "passive"))
      (node (ref "U41") (pin "4") (pinfunction "4.VDD_IO_4") (pintype "passive"))
      (node (ref "U42") (pin "4") (pinfunction "4.VDD_IO_4") (pintype "passive"))
      (node (ref "U43") (pin "4") (pinfunction "4.VDD_IO_4") (pintype "passive"))
      (node (ref "U44") (pin "4") (pinfunction "4.VDD_IO_4") (pintype "passive"))
      (node (ref "U45") (pin "4") (pinfunction "4.VDD_IO_4") (pintype "passive"))
      (node (ref "U46") (pin "4") (pinfunction "4.VDD_IO_4") (pintype "passive"))
      (node (ref "U47") (pin "4") (pinfunction "4.VDD_IO_4") (pintype "passive"))
      (node (ref "U48") (pin "4") (pinfunction "4.VDD_IO_4") (pintype "passive"))
      (node (ref "U49") (pin "4") (pinfunction "4.VDD_IO_4") (pintype "passive"))
      (node (ref "U4A") (pin "4") (pinfunction "4.VDD_IO_4") (pintype "passive"))
      (node (ref "U4B") (pin "4") (pinfunction "4.VDD_IO_4") (pintype "passive"))
      (node (ref "U4C") (pin "4") (pinfunction "4.VDD_IO_4") (pintype "passive"))
      (node (ref "U4D") (pin "4") (pinfunction "4.VDD_IO_4") (pintype "passive"))
      (node (ref "U4E") (pin "4") (pinfunction "4.VDD_IO_4") (pintype "passive"))
      (node (ref "U4F") (pin "4") (pinfunction "4.VDD_IO_4") (pintype "passive"))
    )
    (net (code "85") (name "VDD_POWER-IN") (class "Default")
      (node (ref "F01I") (pin "1") (pinfunction "P$1_1") (pintype "passive"))
      (node (ref "J01") (pin "A1") (pinfunction "1_A1") (pintype "passive"))
      (node (ref "J01") (pin "A2") (pinfunction "2_A2") (pintype "passive"))
      (node (ref "J01") (pin "A3") (pinfunction "3_A3") (pintype "passive"))
      (node (ref "J01") (pin "A4") (pinfunction "4_A4") (pintype "passive"))
    )
    (net (code "86") (name "VDD_POWER-IN_FUSED") (class "Default")
      (node (ref "C01") (pin "1") (pinfunction "1_1") (pintype "passive"))
      (node (ref "C01P") (pin "1") (pinfunction "1_1") (pintype "passive"))
      (node (ref "C02") (pin "1") (pinfunction "1_1") (pintype "passive"))
      (node (ref "C03") (pin "1") (pinfunction "1_1") (pintype "passive"))
      (node (ref "C04") (pin "1") (pinfunction "1_1") (pintype "passive"))
      (node (ref "C05") (pin "1") (pinfunction "1_1") (pintype "passive"))
      (node (ref "C06") (pin "+") (pinfunction "+_+") (pintype "passive"))
      (node (ref "L01I") (pin "2") (pinfunction "2_2") (pintype "passive"))
      (node (ref "R01E") (pin "2") (pinfunction "2_2") (pintype "passive"))
      (node (ref "U01") (pin "12") (pinfunction "12.VIN_12") (pintype "passive"))
      (node (ref "U01") (pin "13") (pinfunction "13.VIN_13") (pintype "passive"))
      (node (ref "U01") (pin "14") (pinfunction "14.VIN_14") (pintype "passive"))
      (node (ref "U01") (pin "15") (pinfunction "15.VIN_15") (pintype "passive"))
      (node (ref "U01") (pin "16") (pinfunction "16.VIN_16") (pintype "passive"))
      (node (ref "U01") (pin "17") (pinfunction "17.VIN_17") (pintype "passive"))
      (node (ref "U01") (pin "19") (pinfunction "19.VDD_19") (pintype "passive"))
    )
    (net (code "87") (name "unconnected-(J01-19-PadB9)") (class "Default")
      (node (ref "J01") (pin "B9") (pinfunction "19_B9") (pintype "passive"))
    )
    (net (code "88") (name "unconnected-(J01-20-PadB10)") (class "Default")
      (node (ref "J01") (pin "B10") (pinfunction "20_B10") (pintype "passive"))
    )
    (net (code "89") (name "unconnected-(U01-5.NC-Pad5)") (class "Default")
      (node (ref "U01") (pin "5") (pinfunction "5.NC_5") (pintype "passive"))
    )
  )
)
